# 001000-005.net
KiCad netlist of a schematic drawn in EAGLE
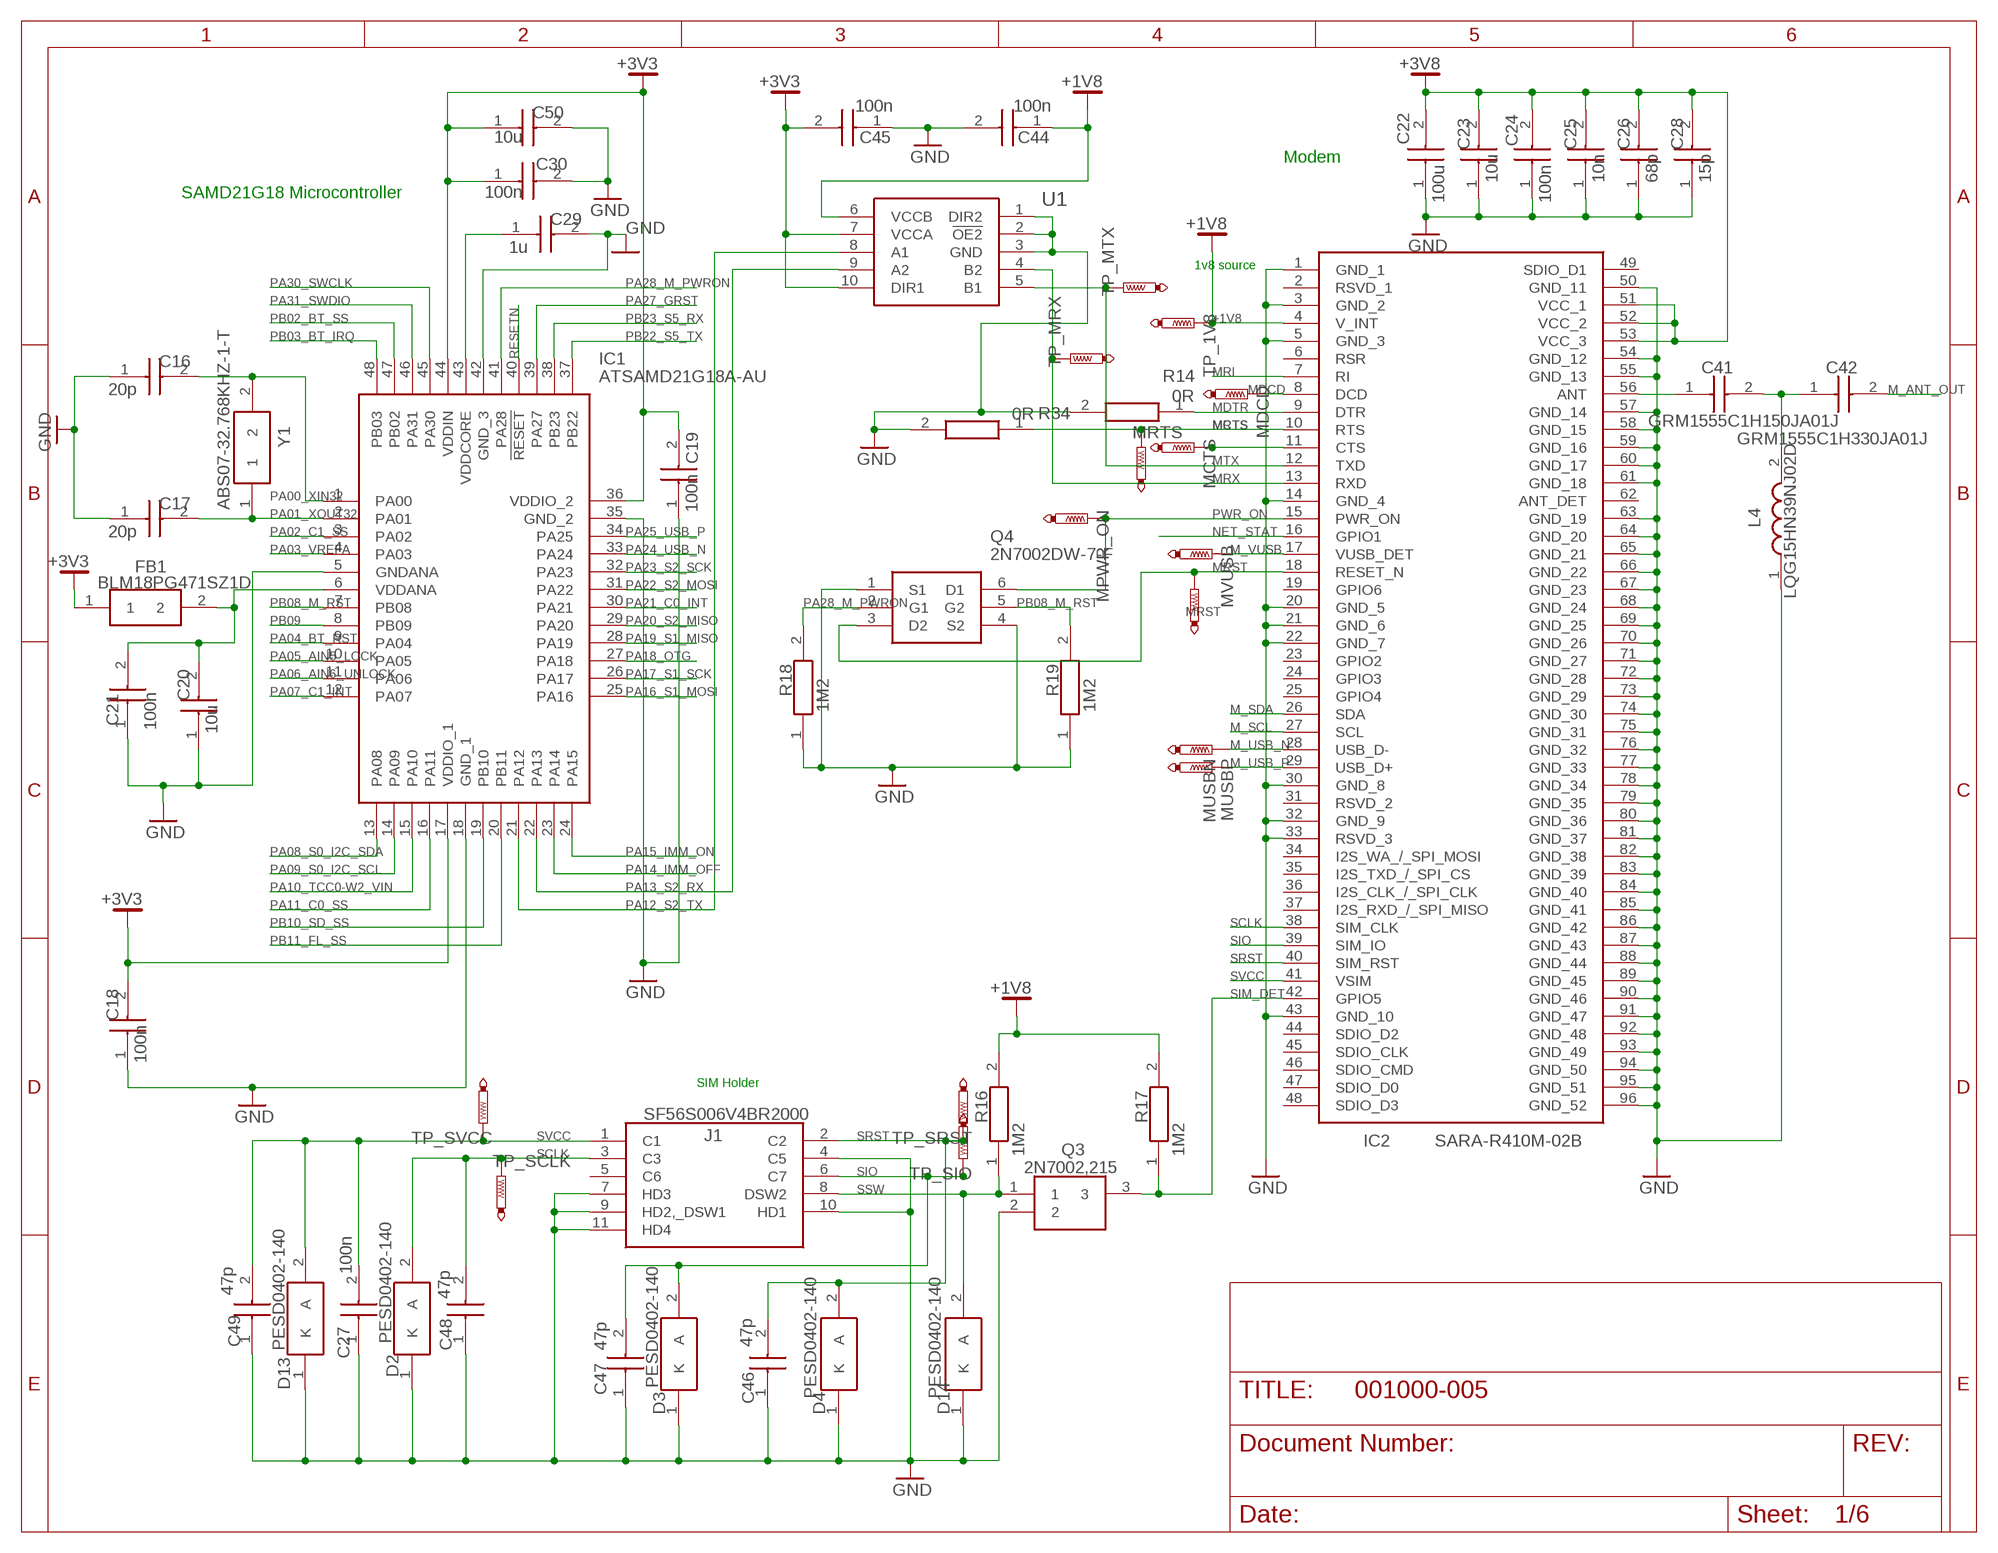
[diagram p0: schematic, sheet 1]
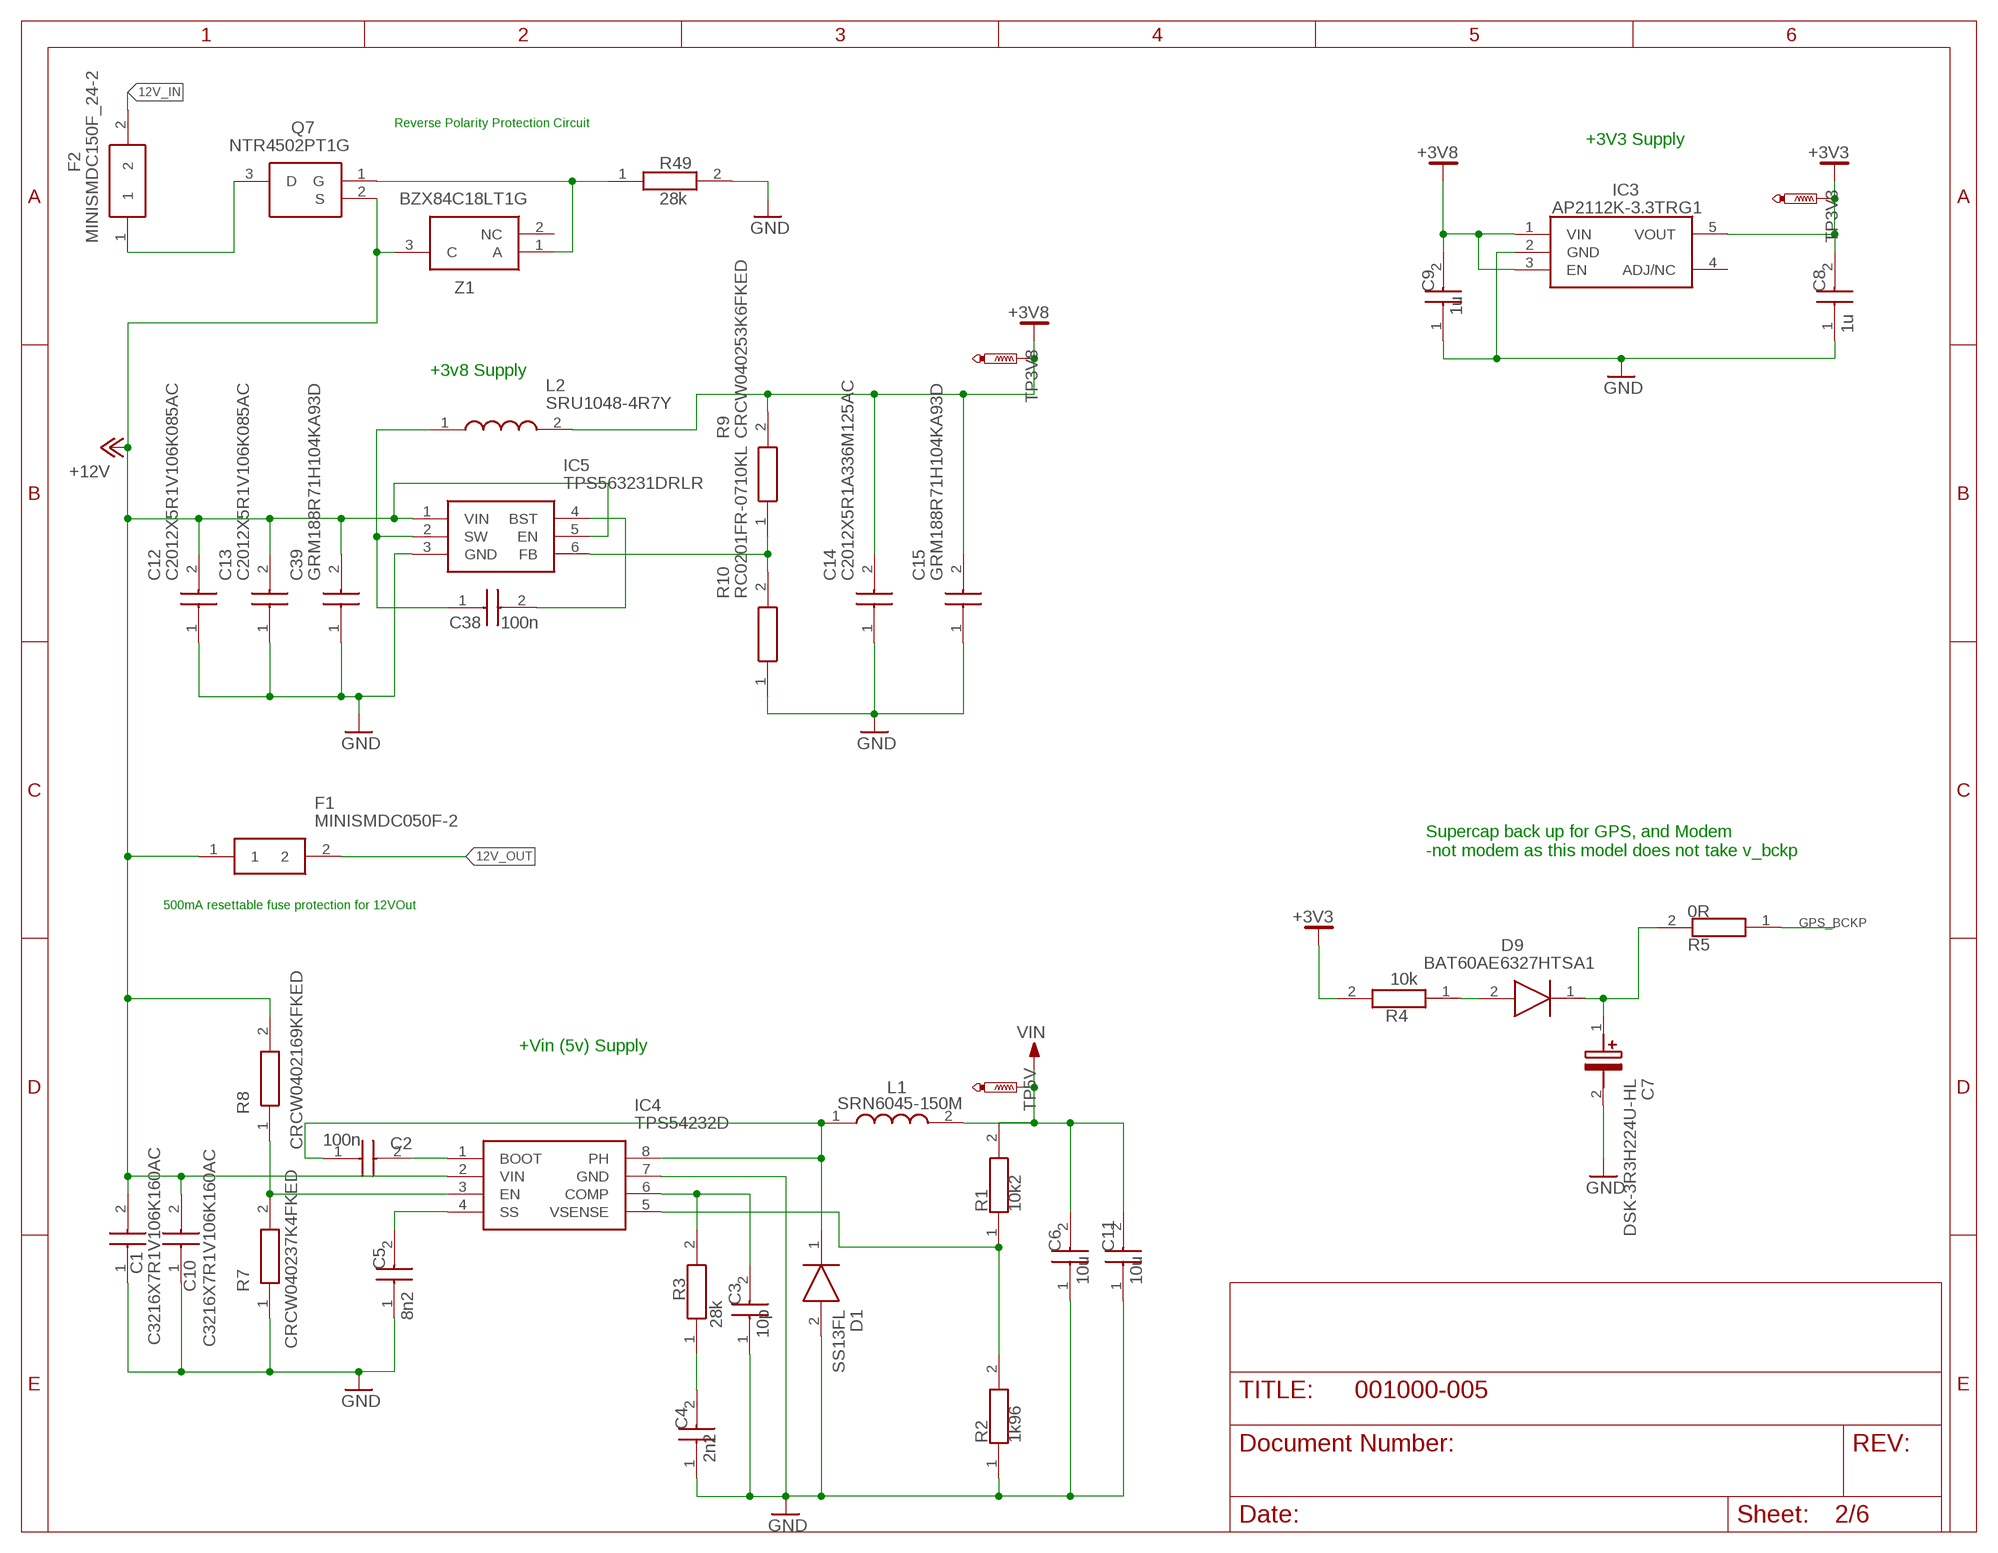
[diagram p1: schematic, sheet 2]
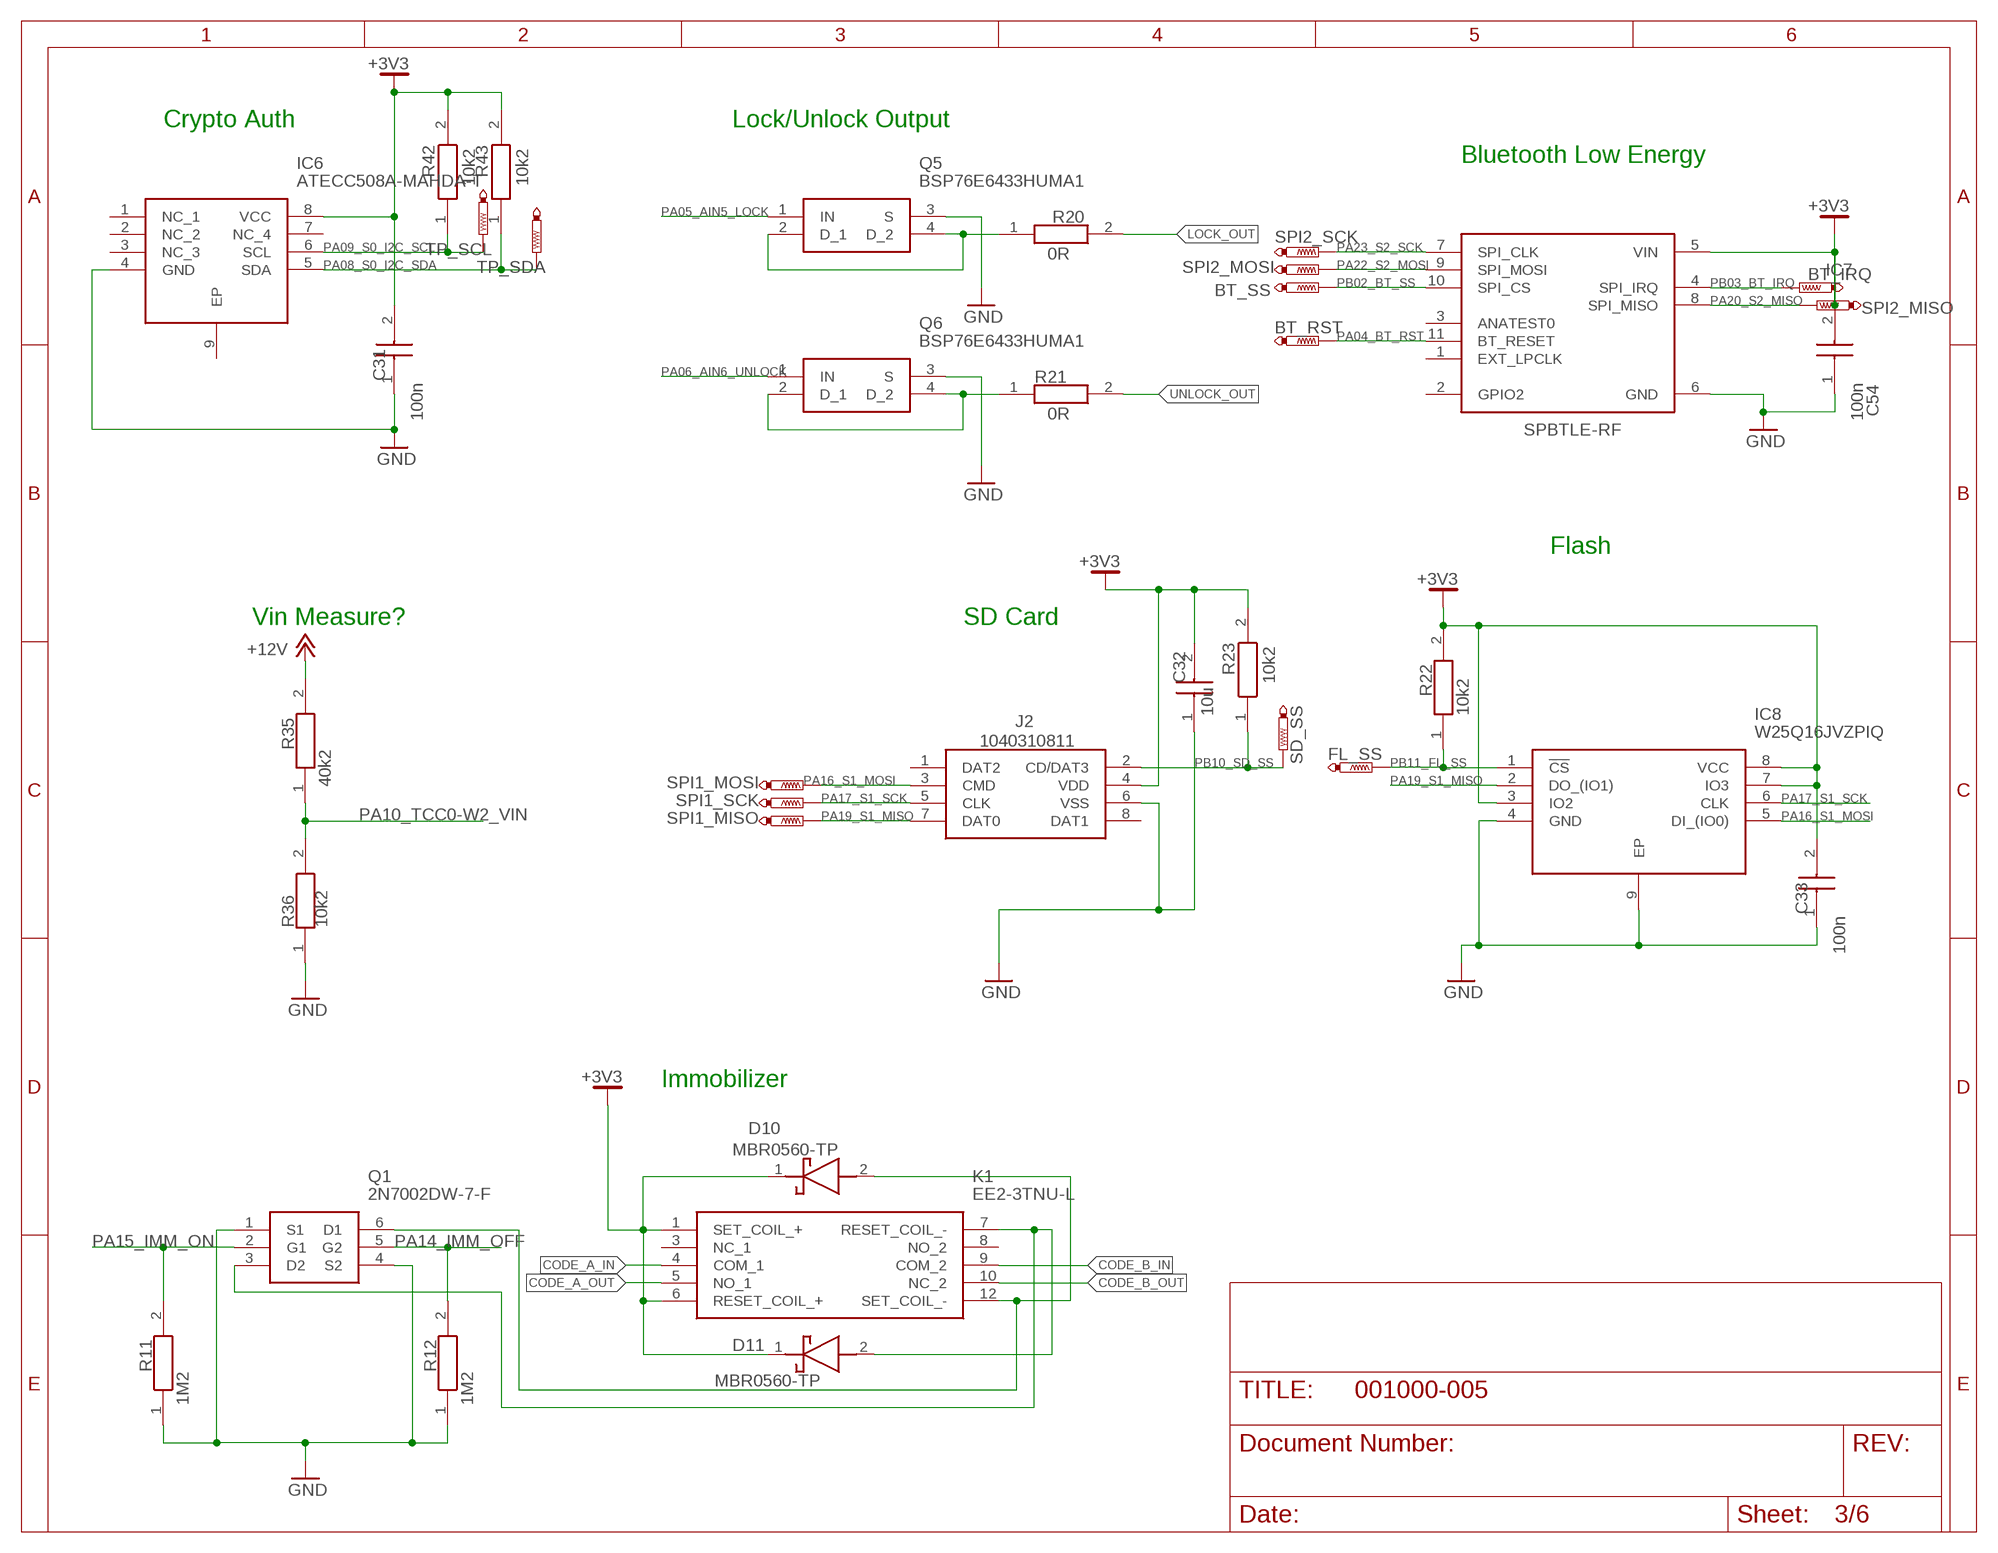
[diagram p2: schematic, sheet 3]
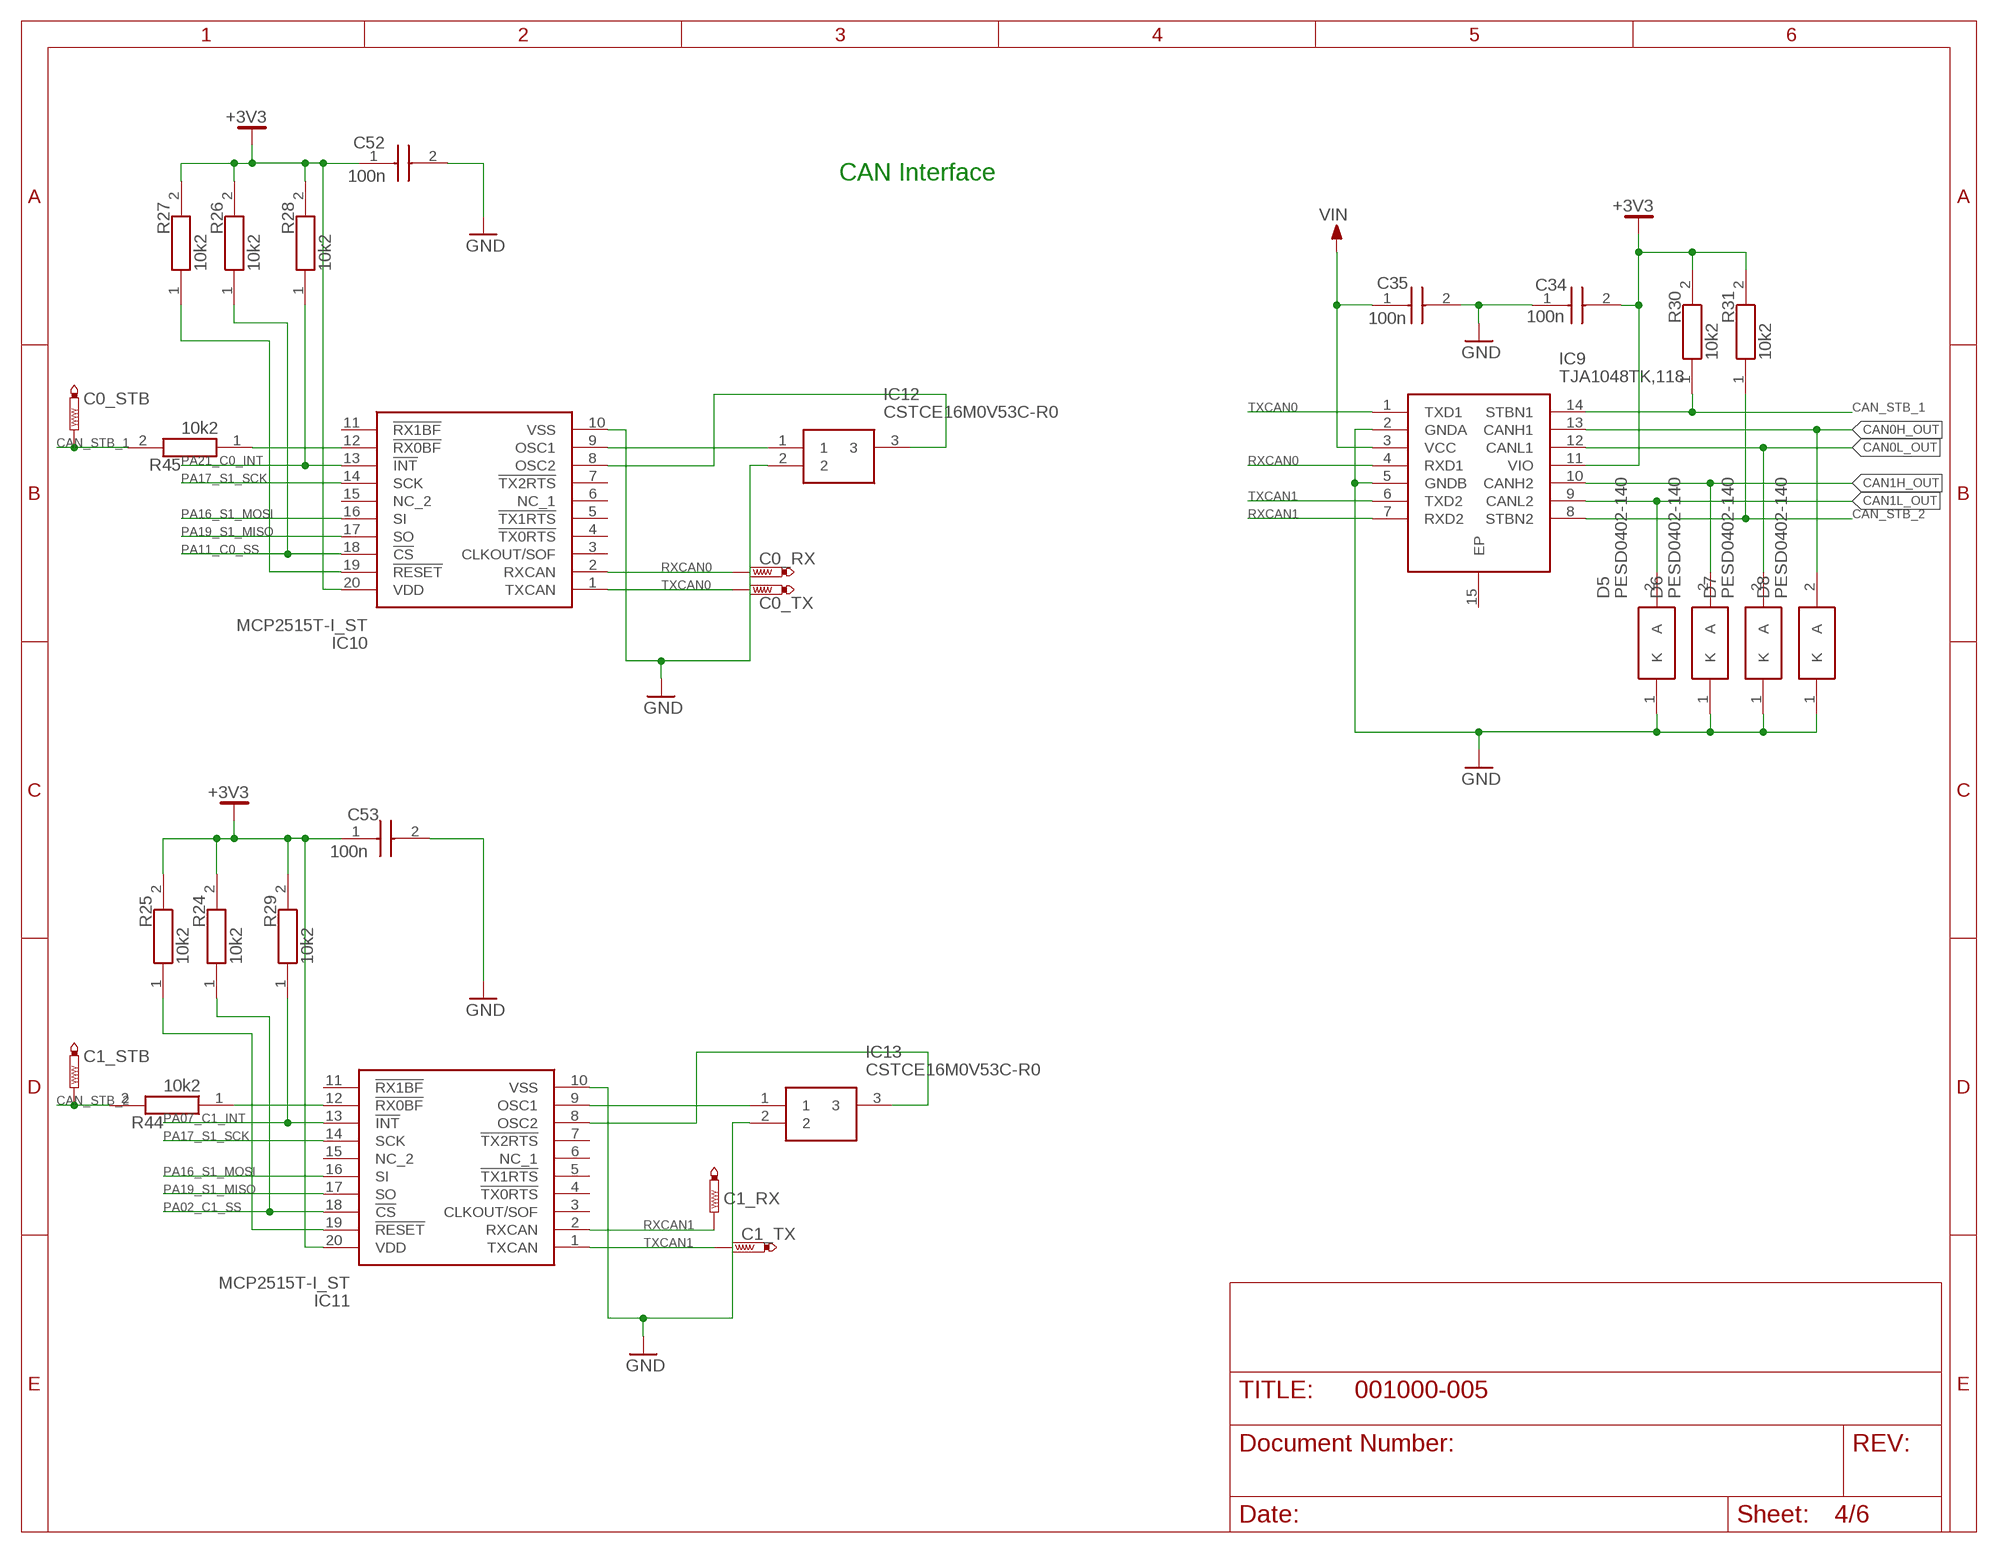
[diagram p3: schematic, sheet 4]
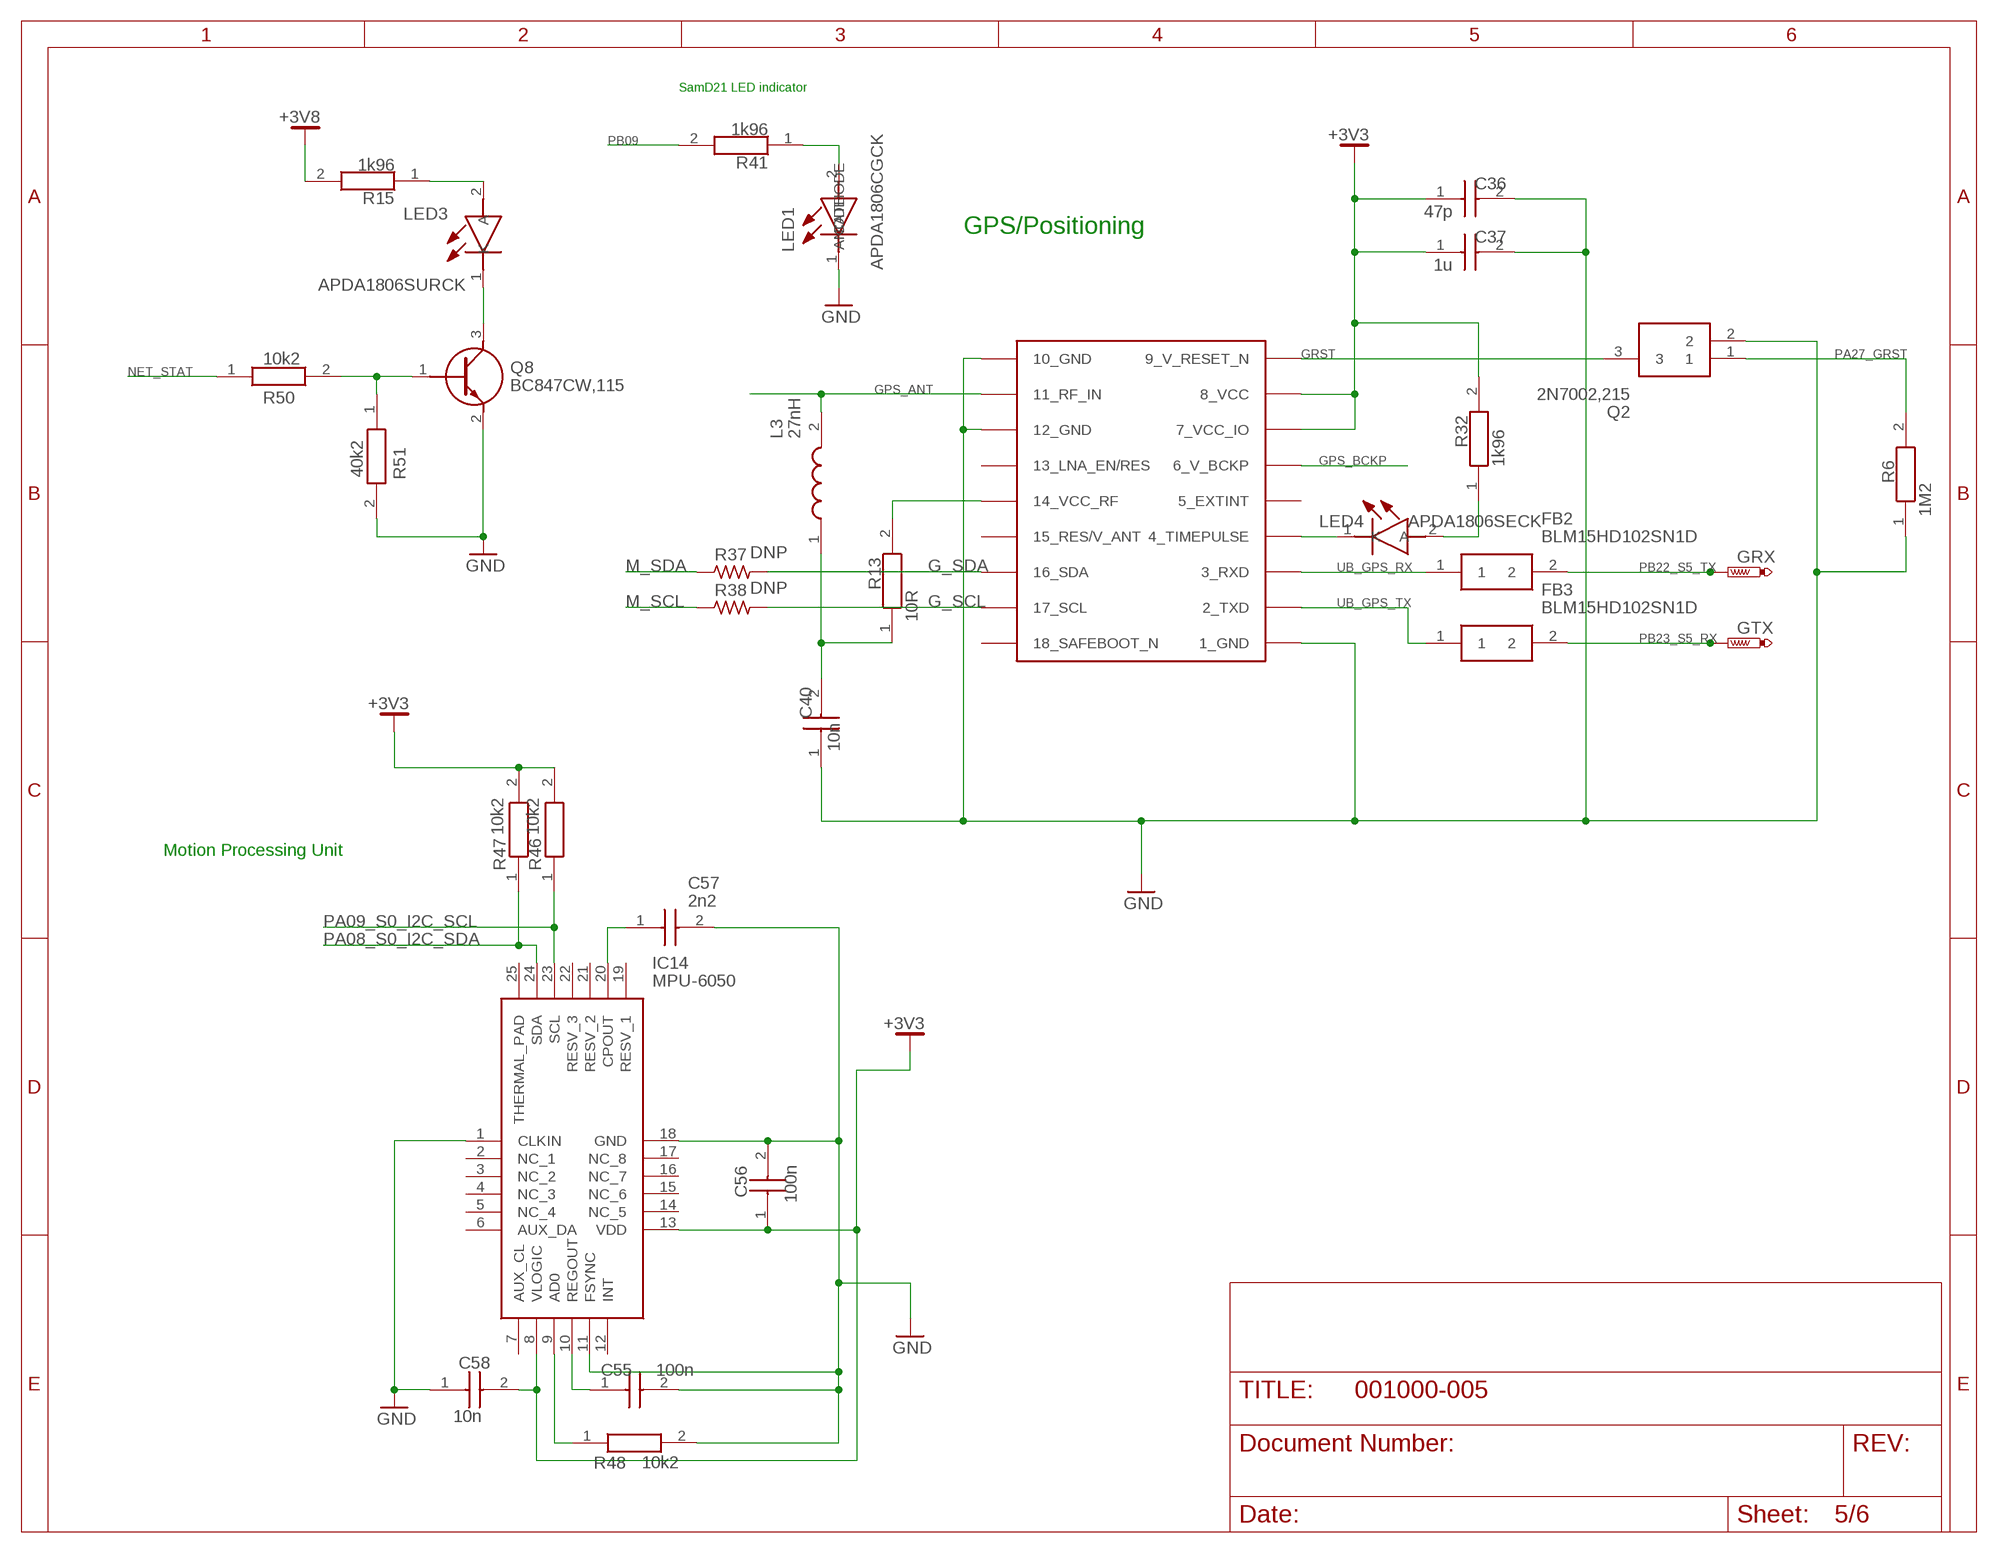
[diagram p4: schematic, sheet 5]
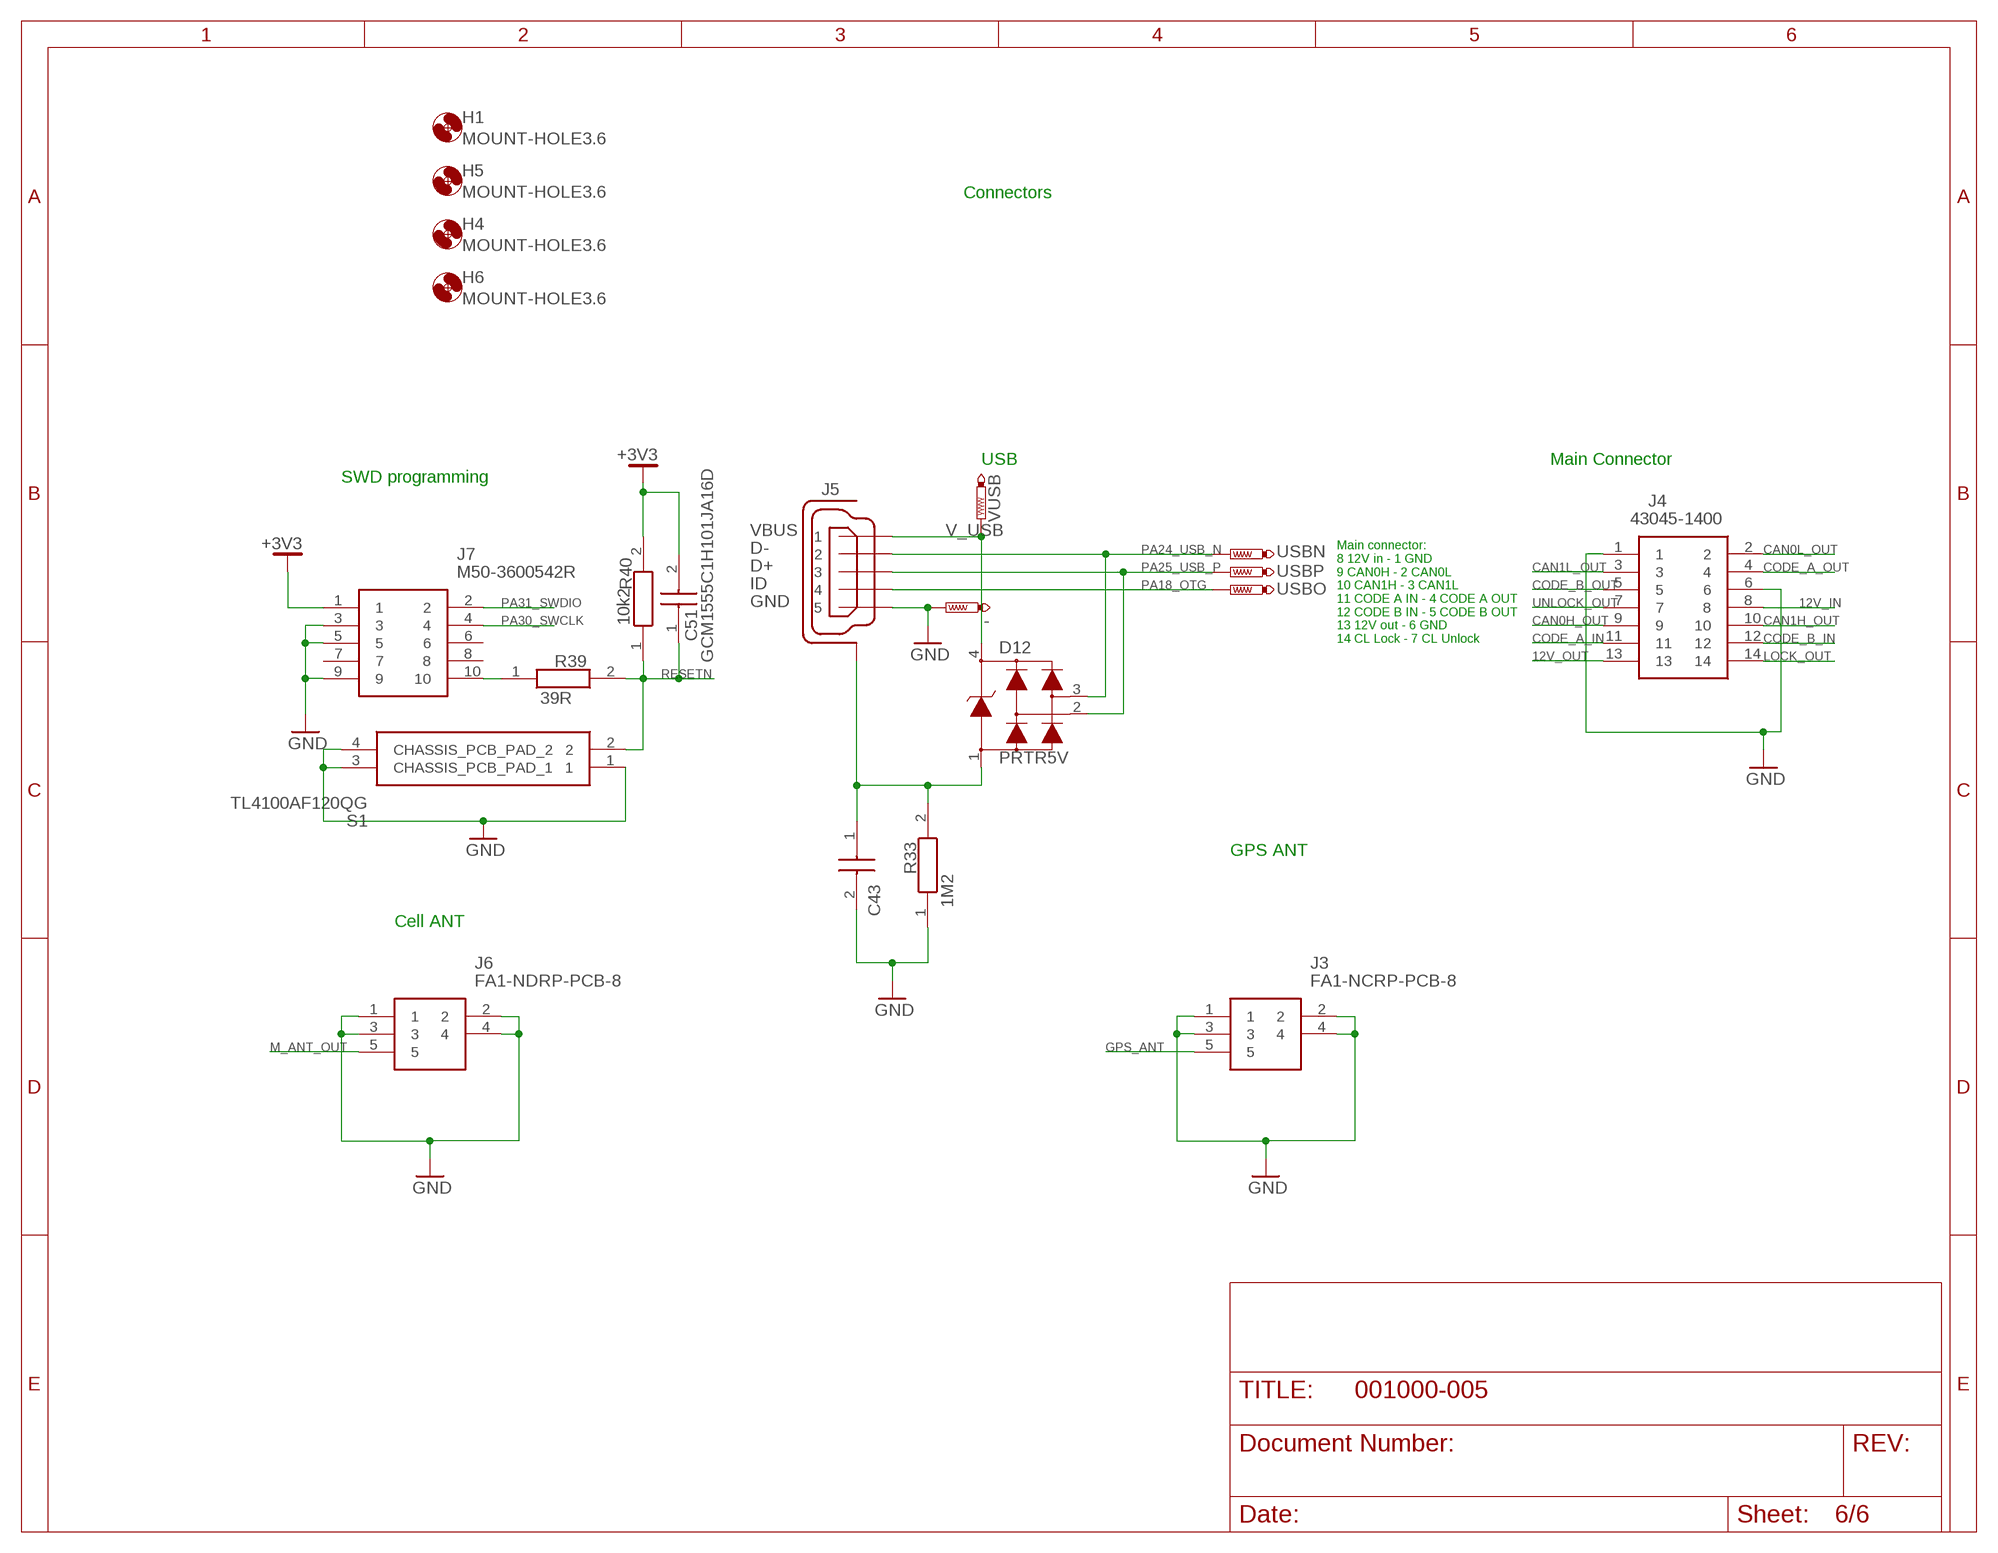
[diagram p5: schematic, sheet 6]

(export (version "E")
  (design (tool "Eeschema 10.0.6"))
  (components
    (comp (ref "-")
      (value "PTR1TP06R")
      (footprint "eagle-import:TP06R")
      (libsource (lib "eagle-import") (part "PTR1TP06R"))
    )
    (comp (ref "C43")
      (value "4n7")
      (footprint "eagle-import:CAPC1005X55N")
      (fields
        (field (name "MANUFACTURER_PART_NUMBER") "GRM155R71H472KA01J")
        (field (name "MOUSER_PART_NUMBER") "81-GRM155R71H472KA1J")
      )
      (libsource (lib "eagle-import") (part "GRM155R71H472KA01J"))
    )
    (comp (ref "C51")
      (value "GCM1555C1H101JA16D")
      (footprint "eagle-import:CAPC1005X55N")
      (libsource (lib "eagle-import") (part "GCM1555C1H101JA16D"))
    )
    (comp (ref "D12")
      (value "PRTR5V")
      (footprint "eagle-import:SOT190P230X110-4N")
      (fields (field (name "MANUFACTURER") "NXP"))
      (libsource (lib "eagle-import") (part "PRTR5V0U2X,215"))
    )
    (comp (ref "H1")
      (value "MOUNT-HOLE3.6")
      (footprint "eagle-import:3,6")
      (libsource (lib "eagle-import") (part "MOUNT-HOLE3.6"))
    )
    (comp (ref "H4")
      (value "MOUNT-HOLE3.6")
      (footprint "eagle-import:3,6")
      (libsource (lib "eagle-import") (part "MOUNT-HOLE3.6"))
    )
    (comp (ref "H5")
      (value "MOUNT-HOLE3.6")
      (footprint "eagle-import:3,6")
      (libsource (lib "eagle-import") (part "MOUNT-HOLE3.6"))
    )
    (comp (ref "H6")
      (value "MOUNT-HOLE3.6")
      (footprint "eagle-import:3,6")
      (libsource (lib "eagle-import") (part "MOUNT-HOLE3.6"))
    )
    (comp (ref "J3")
      (value "FA1-NCRP-PCB-8")
      (footprint "eagle-import:FA1NCRPPCB8")
      (fields (field (name "MOUSER_PART_NUMBER") "523-FA1-NCRP-PCB-8"))
      (libsource (lib "eagle-import") (part "FA1-NCRP-PCB-8"))
    )
    (comp (ref "J4")
      (value "43045-1400")
      (footprint "eagle-import:43045-1400")
      (fields (field (name "MOUSER_PART_NUMBER") "538-43045-1400"))
      (libsource (lib "eagle-import") (part "43045-1400"))
    )
    (comp (ref "J5")
      (value "-")
      (footprint "eagle-import:ZX62-AB-5PA")
      (fields (field (name "MANUFACTURER") "Hirose"))
      (libsource (lib "eagle-import") (part "USB-MICRO"))
    )
    (comp (ref "J6")
      (value "FA1-NDRP-PCB-8")
      (footprint "eagle-import:FA1NDRPPCB8")
      (fields (field (name "MOUSER_PART_NUMBER") "523-FA1-NDRP-PCB-8"))
      (libsource (lib "eagle-import") (part "FA1-NDRP-PCB-8"))
    )
    (comp (ref "J7")
      (value "M50-3600542R")
      (footprint "eagle-import:M503600542R")
      (fields (field (name "MOUSER_PART_NUMBER") "855-M50-3600542R"))
      (libsource (lib "eagle-import") (part "M50-3600542R"))
    )
    (comp (ref "R33")
      (value "1M2")
      (footprint "eagle-import:RESC1005X40N")
      (fields
        (field (name "MANUFACTURER_PART_NUMBER") "CRCW04021M20FKED")
        (field (name "MOUSER_PART_NUMBER") "71-CRCW04021M20FKED")
      )
      (libsource (lib "eagle-import") (part "CRCW04021M20FKED"))
    )
    (comp (ref "R39")
      (value "39R")
      (footprint "eagle-import:RESC1005X40N")
      (fields
        (field (name "MANUFACTURER_PART_NUMBER") "CRCW040239R0FKEDHP")
        (field (name "MOUSER_PART_NUMBER") "71-CRCW040239R0FKEDH")
      )
      (libsource (lib "eagle-import") (part "CRCW040239R0FKEDHP"))
    )
    (comp (ref "R40")
      (value "10k2")
      (footprint "eagle-import:RESC1005X40N")
      (fields
        (field (name "MANUFACTURER_PART_NUMBER") "CRCW040210K2FKED")
        (field (name "MOUSER_PART_NUMBER") "71-CRCW0402-10.2K-E3")
      )
      (libsource (lib "eagle-import") (part "CRCW040210K2FKED"))
    )
    (comp (ref "S1")
      (value "TL4100AF120QG")
      (footprint "eagle-import:TL4100AF120QG")
      (fields (field (name "MOUSER_PART_NUMBER") "612-TL4100AF120QG"))
      (libsource (lib "eagle-import") (part "TL4100AF120QG"))
    )
    (comp (ref "USBN")
      (value "PTR1TP06R")
      (footprint "eagle-import:TP06R")
      (libsource (lib "eagle-import") (part "PTR1TP06R"))
    )
    (comp (ref "USBO")
      (value "PTR1TP06R")
      (footprint "eagle-import:TP06R")
      (libsource (lib "eagle-import") (part "PTR1TP06R"))
    )
    (comp (ref "USBP")
      (value "PTR1TP06R")
      (footprint "eagle-import:TP06R")
      (libsource (lib "eagle-import") (part "PTR1TP06R"))
    )
    (comp (ref "VUSB")
      (value "PTR1TP06R")
      (footprint "eagle-import:TP06R")
      (libsource (lib "eagle-import") (part "PTR1TP06R"))
    )
    (comp (ref "C16")
      (value "20p")
      (footprint "eagle-import:CAPC1005X55N")
      (fields (field (name "MANUFACTURER_PART_NUMBER") "GJM1555C1H200GB01D"))
      (libsource (lib "eagle-import") (part "GJM1555C1H200GB01D"))
    )
    (comp (ref "C17")
      (value "20p")
      (footprint "eagle-import:CAPC1005X55N")
      (fields (field (name "MANUFACTURER_PART_NUMBER") "GJM1555C1H200GB01D"))
      (libsource (lib "eagle-import") (part "GJM1555C1H200GB01D"))
    )
    (comp (ref "C18")
      (value "100n")
      (footprint "eagle-import:CAPC1005X55N")
      (fields (field (name "MANUFACTURER_PART_NUMBER") "GCM155R71C104KA55J"))
      (libsource (lib "eagle-import") (part "GCM155R71C104KA55J"))
    )
    (comp (ref "C19")
      (value "100n")
      (footprint "eagle-import:CAPC1005X55N")
      (fields (field (name "MANUFACTURER_PART_NUMBER") "GCM155R71C104KA55J"))
      (libsource (lib "eagle-import") (part "GCM155R71C104KA55J"))
    )
    (comp (ref "C20")
      (value "10u")
      (footprint "eagle-import:CAPC1608X90N")
      (fields
        (field (name "MANUFACTURER_PART_NUMBER") "GRM188R60J106KE47D")
        (field (name "MOUSER_PART_NUMBER") "81-GRM188R60J106KE7D")
      )
      (libsource (lib "eagle-import") (part "GRM188R60J106KE47D"))
    )
    (comp (ref "C21")
      (value "100n")
      (footprint "eagle-import:CAPC1005X55N")
      (fields (field (name "MANUFACTURER_PART_NUMBER") "GCM155R71C104KA55J"))
      (libsource (lib "eagle-import") (part "GCM155R71C104KA55J"))
    )
    (comp (ref "C22")
      (value "100u")
      (footprint "eagle-import:CAPC3216X180N")
      (fields
        (field (name "MANUFACTURER_PART_NUMBER") "GRM31CD80J107ME39K")
        (field (name "MOUSER_PART_NUMBER") "81-GRM31CD80J107ME9K")
      )
      (libsource (lib "eagle-import") (part "GRM31CD80J107ME39K"))
    )
    (comp (ref "C23")
      (value "10u")
      (footprint "eagle-import:CAPC1608X90N")
      (fields
        (field (name "MANUFACTURER_PART_NUMBER") "GRM188R60J106KE47D")
        (field (name "MOUSER_PART_NUMBER") "81-GRM188R60J106KE7D")
      )
      (libsource (lib "eagle-import") (part "GRM188R60J106KE47D"))
    )
    (comp (ref "C24")
      (value "100n")
      (footprint "eagle-import:CAPC1005X55N")
      (fields (field (name "MANUFACTURER_PART_NUMBER") "GCM155R71C104KA55J"))
      (libsource (lib "eagle-import") (part "GCM155R71C104KA55J"))
    )
    (comp (ref "C25")
      (value "10n")
      (footprint "eagle-import:CAPC1005X55N")
      (fields
        (field (name "MANUFACTURER_PART_NUMBER") "GCM155R71H103KA55D")
        (field (name "MOUSER_PART_NUMBER") "81-GCM155R71H103KA5D")
      )
      (libsource (lib "eagle-import") (part "GCM155R71H103KA55D"))
    )
    (comp (ref "C26")
      (value "68p")
      (footprint "eagle-import:CAPC1005X55N")
      (fields (field (name "MANUFACTURER_PART_NUMBER") "GCM1555C1H680JA16D"))
      (libsource (lib "eagle-import") (part "GCM1555C1H680JA16D"))
    )
    (comp (ref "C27")
      (value "100n")
      (footprint "eagle-import:CAPC1005X55N")
      (fields (field (name "MANUFACTURER_PART_NUMBER") "GCM155R71C104KA55J"))
      (libsource (lib "eagle-import") (part "GCM155R71C104KA55J"))
    )
    (comp (ref "C28")
      (value "15p")
      (footprint "eagle-import:CAPC1005X55N")
      (fields (field (name "MANUFACTURER_PART_NUMBER") "GCM1555C1H150JA16D"))
      (libsource (lib "eagle-import") (part "GCM1555C1H150JA16D"))
    )
    (comp (ref "C29")
      (value "1u")
      (footprint "eagle-import:CAPC1005X55N")
      (fields
        (field (name "MANUFACTURER_PART_NUMBER") "GRM155R61C105MA12D")
        (field (name "MOUSER_PART_NUMBER") "81-GRM155R61C105MA2D")
      )
      (libsource (lib "eagle-import") (part "GRM155R61C105MA12D"))
    )
    (comp (ref "C30")
      (value "100n")
      (footprint "eagle-import:CAPC1005X55N")
      (fields (field (name "MANUFACTURER_PART_NUMBER") "GCM155R71C104KA55J"))
      (libsource (lib "eagle-import") (part "GCM155R71C104KA55J"))
    )
    (comp (ref "C41")
      (value "GRM1555C1H150JA01J")
      (footprint "eagle-import:CAPC1005X55N")
      (fields (field (name "MOUSER_PART_NUMBER") "81-GRM1555C1H150JA1J"))
      (libsource (lib "eagle-import") (part "GRM1555C1H150JA01J"))
    )
    (comp (ref "C42")
      (value "GRM1555C1H330JA01J")
      (footprint "eagle-import:CAPC1005X55N")
      (fields (field (name "MOUSER_PART_NUMBER") "81-GRM1555C1H330JA1J"))
      (libsource (lib "eagle-import") (part "GRM1555C1H330JA01J"))
    )
    (comp (ref "C44")
      (value "100n")
      (footprint "eagle-import:CAPC1005X55N")
      (fields (field (name "MANUFACTURER_PART_NUMBER") "GCM155R71C104KA55J"))
      (libsource (lib "eagle-import") (part "GCM155R71C104KA55J"))
    )
    (comp (ref "C45")
      (value "100n")
      (footprint "eagle-import:CAPC1005X55N")
      (fields (field (name "MANUFACTURER_PART_NUMBER") "GCM155R71C104KA55J"))
      (libsource (lib "eagle-import") (part "GCM155R71C104KA55J"))
    )
    (comp (ref "C46")
      (value "47p")
      (footprint "eagle-import:CAPC1005X55N")
      (fields
        (field (name "MANUFACTURER_PART_NUMBER") "GRM1555C1H470JA01D")
        (field (name "MOUSER_PART_NUMBER") "81-GRM1555C1H470JA1D")
      )
      (libsource (lib "eagle-import") (part "GRM1555C1H470JA01D"))
    )
    (comp (ref "C47")
      (value "47p")
      (footprint "eagle-import:CAPC1005X55N")
      (fields
        (field (name "MANUFACTURER_PART_NUMBER") "GRM1555C1H470JA01D")
        (field (name "MOUSER_PART_NUMBER") "81-GRM1555C1H470JA1D")
      )
      (libsource (lib "eagle-import") (part "GRM1555C1H470JA01D"))
    )
    (comp (ref "C48")
      (value "47p")
      (footprint "eagle-import:CAPC1005X55N")
      (fields
        (field (name "MANUFACTURER_PART_NUMBER") "GRM1555C1H470JA01D")
        (field (name "MOUSER_PART_NUMBER") "81-GRM1555C1H470JA1D")
      )
      (libsource (lib "eagle-import") (part "GRM1555C1H470JA01D"))
    )
    (comp (ref "C49")
      (value "47p")
      (footprint "eagle-import:CAPC1005X55N")
      (fields
        (field (name "MANUFACTURER_PART_NUMBER") "GRM1555C1H470JA01D")
        (field (name "MOUSER_PART_NUMBER") "81-GRM1555C1H470JA1D")
      )
      (libsource (lib "eagle-import") (part "GRM1555C1H470JA01D"))
    )
    (comp (ref "C50")
      (value "10u")
      (footprint "eagle-import:CAPC1608X90N")
      (fields
        (field (name "MANUFACTURER_PART_NUMBER") "GRM188R60J106KE47D")
        (field (name "MOUSER_PART_NUMBER") "81-GRM188R60J106KE7D")
      )
      (libsource (lib "eagle-import") (part "GRM188R60J106KE47D"))
    )
    (comp (ref "D2")
      (value "PESD0402-140")
      (footprint "eagle-import:DIONC1005X43N")
      (libsource (lib "eagle-import") (part "PESD0402-140"))
    )
    (comp (ref "D3")
      (value "PESD0402-140")
      (footprint "eagle-import:DIONC1005X43N")
      (libsource (lib "eagle-import") (part "PESD0402-140"))
    )
    (comp (ref "D4")
      (value "PESD0402-140")
      (footprint "eagle-import:DIONC1005X43N")
      (libsource (lib "eagle-import") (part "PESD0402-140"))
    )
    (comp (ref "D13")
      (value "PESD0402-140")
      (footprint "eagle-import:DIONC1005X43N")
      (libsource (lib "eagle-import") (part "PESD0402-140"))
    )
    (comp (ref "D14")
      (value "PESD0402-140")
      (footprint "eagle-import:DIONC1005X43N")
      (libsource (lib "eagle-import") (part "PESD0402-140"))
    )
    (comp (ref "FB1")
      (value "BLM18PG471SZ1D")
      (footprint "eagle-import:BEADC1608X95N")
      (fields (field (name "MOUSER_PART_NUMBER") "81-BLM18PG471SZ1D"))
      (libsource (lib "eagle-import") (part "BLM18PG471SZ1D"))
    )
    (comp (ref "IC1")
      (value "ATSAMD21G18A-AU")
      (footprint "eagle-import:QFP50P900X900X120-48N")
      (fields (field (name "MOUSER_PART_NUMBER") "556-ATSAMD21G18A-AU"))
      (libsource (lib "eagle-import") (part "ATSAMD21G18A-AU"))
    )
    (comp (ref "IC2")
      (value "SARA-R410M-02B")
      (footprint "eagle-import:SARA-U201-03B")
      (libsource (lib "eagle-import") (part "SARA-R410M-02B"))
    )
    (comp (ref "J1")
      (value "SF56S006V4BR2000")
      (footprint "eagle-import:SF56S006V4BR2000")
      (fields (field (name "MOUSER_PART_NUMBER") "656-SF56S006V4BR2000"))
      (libsource (lib "eagle-import") (part "SF56S006V4BR2000"))
    )
    (comp (ref "L4")
      (value "LQG15HN39NJ02D")
      (footprint "eagle-import:INDC1005X55N")
      (libsource (lib "eagle-import") (part "LQG15HN39NJ02D"))
    )
    (comp (ref "MCTS")
      (value "PTR1TP06R")
      (footprint "eagle-import:TP06R")
      (libsource (lib "eagle-import") (part "PTR1TP06R"))
    )
    (comp (ref "MDCD")
      (value "PTR1TP06R")
      (footprint "eagle-import:TP06R")
      (libsource (lib "eagle-import") (part "PTR1TP06R"))
    )
    (comp (ref "MPWR_ON")
      (value "PTR1TP06R")
      (footprint "eagle-import:TP06R")
      (libsource (lib "eagle-import") (part "PTR1TP06R"))
    )
    (comp (ref "MRST")
      (value "PTR1TP06R")
      (footprint "eagle-import:TP06R")
      (libsource (lib "eagle-import") (part "PTR1TP06R"))
    )
    (comp (ref "MRTS")
      (value "PTR1TP06R")
      (footprint "eagle-import:TP06R")
      (libsource (lib "eagle-import") (part "PTR1TP06R"))
    )
    (comp (ref "MUSBN")
      (value "PTR1TP06R")
      (footprint "eagle-import:TP06R")
      (libsource (lib "eagle-import") (part "PTR1TP06R"))
    )
    (comp (ref "MUSBP")
      (value "PTR1TP06R")
      (footprint "eagle-import:TP06R")
      (libsource (lib "eagle-import") (part "PTR1TP06R"))
    )
    (comp (ref "MVUSB")
      (value "PTR1TP06R")
      (footprint "eagle-import:TP06R")
      (libsource (lib "eagle-import") (part "PTR1TP06R"))
    )
    (comp (ref "Q3")
      (value "2N7002,215")
      (footprint "eagle-import:SOT95P230X110-3N")
      (fields (field (name "MOUSER_PART_NUMBER") "771-2N7002-T/R"))
      (libsource (lib "eagle-import") (part "2N7002,215"))
    )
    (comp (ref "Q4")
      (value "2N7002DW-7-F")
      (footprint "eagle-import:SOT65P210X100-6N")
      (fields (field (name "MOUSER_PART_NUMBER") "621-2N7002DW-F"))
      (libsource (lib "eagle-import") (part "2N7002DW-7-F"))
    )
    (comp (ref "R14")
      (value "0R")
      (footprint "eagle-import:RESC1005X40N")
      (fields (field (name "MANUFACTURER_PART_NUMBER") "RMCF0402ZT0R00"))
      (libsource (lib "eagle-import") (part "RMCF0402ZT0R00"))
    )
    (comp (ref "R16")
      (value "1M2")
      (footprint "eagle-import:RESC1005X40N")
      (fields
        (field (name "MANUFACTURER_PART_NUMBER") "CRCW04021M20FKED")
        (field (name "MOUSER_PART_NUMBER") "71-CRCW04021M20FKED")
      )
      (libsource (lib "eagle-import") (part "CRCW04021M20FKED"))
    )
    (comp (ref "R17")
      (value "1M2")
      (footprint "eagle-import:RESC1005X40N")
      (fields
        (field (name "MANUFACTURER_PART_NUMBER") "CRCW04021M20FKED")
        (field (name "MOUSER_PART_NUMBER") "71-CRCW04021M20FKED")
      )
      (libsource (lib "eagle-import") (part "CRCW04021M20FKED"))
    )
    (comp (ref "R18")
      (value "1M2")
      (footprint "eagle-import:RESC1005X40N")
      (fields
        (field (name "MANUFACTURER_PART_NUMBER") "CRCW04021M20FKED")
        (field (name "MOUSER_PART_NUMBER") "71-CRCW04021M20FKED")
      )
      (libsource (lib "eagle-import") (part "CRCW04021M20FKED"))
    )
    (comp (ref "R19")
      (value "1M2")
      (footprint "eagle-import:RESC1005X40N")
      (fields
        (field (name "MANUFACTURER_PART_NUMBER") "CRCW04021M20FKED")
        (field (name "MOUSER_PART_NUMBER") "71-CRCW04021M20FKED")
      )
      (libsource (lib "eagle-import") (part "CRCW04021M20FKED"))
    )
    (comp (ref "R34")
      (value "0R")
      (footprint "eagle-import:RESC1005X40N")
      (fields (field (name "MANUFACTURER_PART_NUMBER") "RMCF0402ZT0R00"))
      (libsource (lib "eagle-import") (part "RMCF0402ZT0R00"))
    )
    (comp (ref "TP_1V8")
      (value "PTR1TP06R")
      (footprint "eagle-import:TP06R")
      (libsource (lib "eagle-import") (part "PTR1TP06R"))
    )
    (comp (ref "TP_MRX")
      (value "PTR1TP06R")
      (footprint "eagle-import:TP06R")
      (libsource (lib "eagle-import") (part "PTR1TP06R"))
    )
    (comp (ref "TP_MTX")
      (value "PTR1TP06R")
      (footprint "eagle-import:TP06R")
      (libsource (lib "eagle-import") (part "PTR1TP06R"))
    )
    (comp (ref "TP_SCLK")
      (value "PTR1TP06R")
      (footprint "eagle-import:TP06R")
      (libsource (lib "eagle-import") (part "PTR1TP06R"))
    )
    (comp (ref "TP_SIO")
      (value "PTR1TP06R")
      (footprint "eagle-import:TP06R")
      (libsource (lib "eagle-import") (part "PTR1TP06R"))
    )
    (comp (ref "TP_SRST")
      (value "PTR1TP06R")
      (footprint "eagle-import:TP06R")
      (libsource (lib "eagle-import") (part "PTR1TP06R"))
    )
    (comp (ref "TP_SVCC")
      (value "PTR1TP06R")
      (footprint "eagle-import:TP06R")
      (libsource (lib "eagle-import") (part "PTR1TP06R"))
    )
    (comp (ref "U1")
      (value "SN74AVC2T245RSWR")
      (footprint "eagle-import:RSW(RPUQFNN10)")
      (fields (field (name "MOUSER_PART_NUMBER") "595-SN74AVC2T245RSWR"))
      (libsource (lib "eagle-import") (part "SN74AVC2T245RSWR"))
    )
    (comp (ref "Y1")
      (value "ABS07-32.768KHZ-1-T")
      (footprint "eagle-import:ABS0716632768KHZT")
      (fields
        (field (name "MANUFACTURER_PART_NUMBER") "ABS07-32.768KHz-1-T")
        (field (name "MOUSER_PART_NUMBER") "815-ABS07-32.7K-1-T")
      )
      (libsource (lib "eagle-import") (part "ABS07-32.768KHZ-1-T"))
    )
    (comp (ref "C36")
      (value "47p")
      (footprint "eagle-import:CAPC1005X55N")
      (fields
        (field (name "MANUFACTURER_PART_NUMBER") "GRM1555C1H470JA01D")
        (field (name "MOUSER_PART_NUMBER") "81-GRM1555C1H470JA1D")
      )
      (libsource (lib "eagle-import") (part "GRM1555C1H470JA01D"))
    )
    (comp (ref "C37")
      (value "1u")
      (footprint "eagle-import:CAPC1608X90N")
      (fields
        (field (name "MANUFACTURER_PART_NUMBER") "GRT188C8YA105KE13D")
        (field (name "MOUSER_PART_NUMBER") "81-GRT188C8YA105KE3D")
      )
      (libsource (lib "eagle-import") (part "GRT188C8YA105KE13D"))
    )
    (comp (ref "C40")
      (value "10n")
      (footprint "eagle-import:CAPC1005X55N")
      (fields
        (field (name "MANUFACTURER_PART_NUMBER") "GCM155R71H103KA55D")
        (field (name "MOUSER_PART_NUMBER") "81-GCM155R71H103KA5D")
      )
      (libsource (lib "eagle-import") (part "GCM155R71H103KA55D"))
    )
    (comp (ref "C55")
      (value "100n")
      (footprint "eagle-import:CAPC1005X55N")
      (fields (field (name "MANUFACTURER_PART_NUMBER") "GCM155R71C104KA55J"))
      (libsource (lib "eagle-import") (part "GCM155R71C104KA55J"))
    )
    (comp (ref "C56")
      (value "100n")
      (footprint "eagle-import:CAPC1005X55N")
      (fields (field (name "MANUFACTURER_PART_NUMBER") "GCM155R71C104KA55J"))
      (libsource (lib "eagle-import") (part "GCM155R71C104KA55J"))
    )
    (comp (ref "C57")
      (value "2n2")
      (footprint "eagle-import:CAPC1005X55N")
      (fields
        (field (name "MANUFACTURER_PART_NUMBER") "GRM155R71H222KA01D")
        (field (name "MOUSER_PART_NUMBER") "81-GRM36X222K50")
      )
      (libsource (lib "eagle-import") (part "GRM155R71H222KA01D"))
    )
    (comp (ref "C58")
      (value "10n")
      (footprint "eagle-import:CAPC1005X55N")
      (fields
        (field (name "MANUFACTURER_PART_NUMBER") "GCM155R71H103KA55D")
        (field (name "MOUSER_PART_NUMBER") "81-GCM155R71H103KA5D")
      )
      (libsource (lib "eagle-import") (part "GCM155R71H103KA55D"))
    )
    (comp (ref "FB2")
      (value "BLM15HD102SN1D")
      (footprint "eagle-import:BEADC1005X55N")
      (fields (field (name "MOUSER_PART_NUMBER") "81-BLM15HD102SN1D"))
      (libsource (lib "eagle-import") (part "BLM15HD102SN1D"))
    )
    (comp (ref "FB3")
      (value "BLM15HD102SN1D")
      (footprint "eagle-import:BEADC1005X55N")
      (fields (field (name "MOUSER_PART_NUMBER") "81-BLM15HD102SN1D"))
      (libsource (lib "eagle-import") (part "BLM15HD102SN1D"))
    )
    (comp (ref "GRX")
      (value "PTR1TP06R")
      (footprint "eagle-import:TP06R")
      (libsource (lib "eagle-import") (part "PTR1TP06R"))
    )
    (comp (ref "GTX")
      (value "PTR1TP06R")
      (footprint "eagle-import:TP06R")
      (libsource (lib "eagle-import") (part "PTR1TP06R"))
    )
    (comp (ref "IC14")
      (value "MPU-6050")
      (footprint "eagle-import:QFN50P400X400X95-25N")
      (libsource (lib "eagle-import") (part "MPU-6050"))
    )
    (comp (ref "L3")
      (value "27nH")
      (footprint "eagle-import:INDC1608X95N")
      (fields (field (name "MANUFACTURER_PART_NUMBER") "L-14C27NJV4T"))
      (libsource (lib "eagle-import") (part "L-14C27NJV4T"))
    )
    (comp (ref "LED1")
      (value "APDA1806CGCK")
      (footprint "eagle-import:APDA1806CGCK")
      (fields (field (name "MOUSER_PART_NUMBER") "604-APDA1806CGCK"))
      (libsource (lib "eagle-import") (part "APDA1806CGCK"))
    )
    (comp (ref "LED3")
      (value "APDA1806SURCK")
      (footprint "eagle-import:APDA1806SURCK")
      (fields (field (name "MOUSER_PART_NUMBER") "604-APDA1806SURCK"))
      (libsource (lib "eagle-import") (part "APDA1806SURCK"))
    )
    (comp (ref "LED4")
      (value "APDA1806SECK")
      (footprint "eagle-import:APDA1806SECK")
      (fields (field (name "MOUSER_PART_NUMBER") "604-APDA1806SECK"))
      (libsource (lib "eagle-import") (part "APDA1806SECK"))
    )
    (comp (ref "Q2")
      (value "2N7002,215")
      (footprint "eagle-import:SOT95P230X110-3N")
      (fields (field (name "MOUSER_PART_NUMBER") "771-2N7002-T/R"))
      (libsource (lib "eagle-import") (part "2N7002,215"))
    )
    (comp (ref "Q8")
      (value "BC847CW,115")
      (footprint "eagle-import:SOT65P210X110-3N")
      (fields (field (name "MOUSER_PART_NUMBER") "771-BC847CW-T/R"))
      (libsource (lib "eagle-import") (part "BC847CW,115"))
    )
    (comp (ref "R6")
      (value "1M2")
      (footprint "eagle-import:RESC1005X40N")
      (fields
        (field (name "MANUFACTURER_PART_NUMBER") "CRCW04021M20FKED")
        (field (name "MOUSER_PART_NUMBER") "71-CRCW04021M20FKED")
      )
      (libsource (lib "eagle-import") (part "CRCW04021M20FKED"))
    )
    (comp (ref "R13")
      (value "10R")
      (footprint "eagle-import:RESC1005X35N")
      (fields (field (name "MANUFACTURER_PART_NUMBER") "CRGCQ0402F10R"))
      (libsource (lib "eagle-import") (part "CRGCQ0402F10R"))
    )
    (comp (ref "R15")
      (value "1k96")
      (footprint "eagle-import:RESC1005X40N")
      (fields
        (field (name "MANUFACTURER_PART_NUMBER") "CRCW04021K96FKED")
        (field (name "MOUSER_PART_NUMBER") "71-CRCW0402-1.96K-E3")
      )
      (libsource (lib "eagle-import") (part "CRCW04021K96FKED"))
    )
    (comp (ref "R32")
      (value "1k96")
      (footprint "eagle-import:RESC1005X40N")
      (fields
        (field (name "MANUFACTURER_PART_NUMBER") "CRCW04021K96FKED")
        (field (name "MOUSER_PART_NUMBER") "71-CRCW0402-1.96K-E3")
      )
      (libsource (lib "eagle-import") (part "CRCW04021K96FKED"))
    )
    (comp (ref "R37")
      (value "DNP")
      (footprint "eagle-import:R0402")
      (libsource (lib "eagle-import") (part "R_0402"))
    )
    (comp (ref "R38")
      (value "DNP")
      (footprint "eagle-import:R0402")
      (libsource (lib "eagle-import") (part "R_0402"))
    )
    (comp (ref "R41")
      (value "1k96")
      (footprint "eagle-import:RESC1005X40N")
      (fields
        (field (name "MANUFACTURER_PART_NUMBER") "CRCW04021K96FKED")
        (field (name "MOUSER_PART_NUMBER") "71-CRCW0402-1.96K-E3")
      )
      (libsource (lib "eagle-import") (part "CRCW04021K96FKED"))
    )
    (comp (ref "R46")
      (value "10k2")
      (footprint "eagle-import:RESC1005X40N")
      (fields
        (field (name "MANUFACTURER_PART_NUMBER") "CRCW040210K2FKED")
        (field (name "MOUSER_PART_NUMBER") "71-CRCW0402-10.2K-E3")
      )
      (libsource (lib "eagle-import") (part "CRCW040210K2FKED"))
    )
    (comp (ref "R47")
      (value "10k2")
      (footprint "eagle-import:RESC1005X40N")
      (fields
        (field (name "MANUFACTURER_PART_NUMBER") "CRCW040210K2FKED")
        (field (name "MOUSER_PART_NUMBER") "71-CRCW0402-10.2K-E3")
      )
      (libsource (lib "eagle-import") (part "CRCW040210K2FKED"))
    )
    (comp (ref "R48")
      (value "10k2")
      (footprint "eagle-import:RESC1005X40N")
      (fields
        (field (name "MANUFACTURER_PART_NUMBER") "CRCW040210K2FKED")
        (field (name "MOUSER_PART_NUMBER") "71-CRCW0402-10.2K-E3")
      )
      (libsource (lib "eagle-import") (part "CRCW040210K2FKED"))
    )
    (comp (ref "R50")
      (value "10k2")
      (footprint "eagle-import:RESC1005X40N")
      (fields
        (field (name "MANUFACTURER_PART_NUMBER") "CRCW040210K2FKED")
        (field (name "MOUSER_PART_NUMBER") "71-CRCW0402-10.2K-E3")
      )
      (libsource (lib "eagle-import") (part "CRCW040210K2FKED"))
    )
    (comp (ref "R51")
      (value "40k2")
      (footprint "eagle-import:RESC1005X40N")
      (fields
        (field (name "MANUFACTURER_PART_NUMBER") "CRCW040240K2FKED")
        (field (name "MOUSER_PART_NUMBER") "71-CRCW0402-40.2K-E3")
      )
      (libsource (lib "eagle-import") (part "CRCW040240K2FKED"))
    )
    (comp (ref "U$1")
      (value "MAX-M8")
      (footprint "eagle-import:MAX-M8")
      (libsource (lib "eagle-import") (part "MAX-M8"))
    )
    (comp (ref "C1")
      (value "C3216X7R1V106K160AC")
      (footprint "eagle-import:CAPC3216X180N")
      (fields (field (name "MOUSER_PART_NUMBER") "810-C3216X7R1V106KAC"))
      (libsource (lib "eagle-import") (part "C3216X7R1V106K160AC"))
    )
    (comp (ref "C2")
      (value "100n")
      (footprint "eagle-import:CAPC1005X55N")
      (fields (field (name "MANUFACTURER_PART_NUMBER") "GCM155R71C104KA55J"))
      (libsource (lib "eagle-import") (part "GCM155R71C104KA55J"))
    )
    (comp (ref "C3")
      (value "10p")
      (footprint "eagle-import:CAPC1005X55N")
      (fields (field (name "MANUFACTURER_PART_NUMBER") "GCM1555C1H100JA16D"))
      (libsource (lib "eagle-import") (part "GCM1555C1H100JA16D"))
    )
    (comp (ref "C4")
      (value "2n2")
      (footprint "eagle-import:CAPC1005X55N")
      (fields
        (field (name "MANUFACTURER_PART_NUMBER") "GRM155R71H222KA01D")
        (field (name "MOUSER_PART_NUMBER") "81-GRM36X222K50")
      )
      (libsource (lib "eagle-import") (part "GRM155R71H222KA01D"))
    )
    (comp (ref "C5")
      (value "8n2")
      (footprint "eagle-import:CAPC1005X55N")
      (fields
        (field (name "MANUFACTURER_PART_NUMBER") "GRM155R71C822KA01D")
        (field (name "MOUSER_PART_NUMBER") "81-GRM155R71C822KA1D")
      )
      (libsource (lib "eagle-import") (part "GRM155R71C822KA01D"))
    )
    (comp (ref "C6")
      (value "10u")
      (footprint "eagle-import:CAPC2012X145N")
      (fields
        (field (name "MANUFACTURER_PART_NUMBER") "GRM21BC81C106KE15L")
        (field (name "MOUSER_PART_NUMBER") "81-GRM21BC81C106KE5L")
      )
      (libsource (lib "eagle-import") (part "GRM21BC81C106KE15L"))
    )
    (comp (ref "C7")
      (value "DSK-3R3H224U-HL")
      (footprint "eagle-import:DSK-414_HL")
      (fields (field (name "MOUSER_PART_NUMBER") "555-DSK3R3H224U-HL"))
      (libsource (lib "eagle-import") (part "DSK-3R3H224U-HL"))
    )
    (comp (ref "C8")
      (value "1u")
      (footprint "eagle-import:CAPC1005X55N")
      (fields
        (field (name "MANUFACTURER_PART_NUMBER") "GRM155R61C105MA12D")
        (field (name "MOUSER_PART_NUMBER") "81-GRM155R61C105MA2D")
      )
      (libsource (lib "eagle-import") (part "GRM155R61C105MA12D"))
    )
    (comp (ref "C9")
      (value "1u")
      (footprint "eagle-import:CAPC1005X55N")
      (fields
        (field (name "MANUFACTURER_PART_NUMBER") "GRM155R61C105MA12D")
        (field (name "MOUSER_PART_NUMBER") "81-GRM155R61C105MA2D")
      )
      (libsource (lib "eagle-import") (part "GRM155R61C105MA12D"))
    )
    (comp (ref "C10")
      (value "C3216X7R1V106K160AC")
      (footprint "eagle-import:CAPC3216X180N")
      (fields (field (name "MOUSER_PART_NUMBER") "810-C3216X7R1V106KAC"))
      (libsource (lib "eagle-import") (part "C3216X7R1V106K160AC"))
    )
    (comp (ref "C11")
      (value "10u")
      (footprint "eagle-import:CAPC2012X145N")
      (fields
        (field (name "MANUFACTURER_PART_NUMBER") "GRM21BC81C106KE15L")
        (field (name "MOUSER_PART_NUMBER") "81-GRM21BC81C106KE5L")
      )
      (libsource (lib "eagle-import") (part "GRM21BC81C106KE15L"))
    )
    (comp (ref "C12")
      (value "C2012X5R1V106K085AC")
      (footprint "eagle-import:CAPC2012X100N")
      (fields (field (name "MOUSER_PART_NUMBER") "810-C2012X5R1V106K0C"))
      (libsource (lib "eagle-import") (part "C2012X5R1V106K085AC"))
    )
    (comp (ref "C13")
      (value "C2012X5R1V106K085AC")
      (footprint "eagle-import:CAPC2012X100N")
      (fields (field (name "MOUSER_PART_NUMBER") "810-C2012X5R1V106K0C"))
      (libsource (lib "eagle-import") (part "C2012X5R1V106K085AC"))
    )
    (comp (ref "C14")
      (value "C2012X5R1A336M125AC")
      (footprint "eagle-import:CAPC2012X145N")
      (fields (field (name "MOUSER_PART_NUMBER") "810-C2012X5R1A336M"))
      (libsource (lib "eagle-import") (part "C2012X5R1A336M125AC"))
    )
    (comp (ref "C15")
      (value "GRM188R71H104KA93D")
      (footprint "eagle-import:CAPC1608X90N")
      (fields (field (name "MOUSER_PART_NUMBER") "81-GRM39X104K50D"))
      (libsource (lib "eagle-import") (part "GRM188R71H104KA93D"))
    )
    (comp (ref "C38")
      (value "100n")
      (footprint "eagle-import:CAPC1005X55N")
      (fields (field (name "MANUFACTURER_PART_NUMBER") "GCM155R71C104KA55J"))
      (libsource (lib "eagle-import") (part "GCM155R71C104KA55J"))
    )
    (comp (ref "C39")
      (value "GRM188R71H104KA93D")
      (footprint "eagle-import:CAPC1608X90N")
      (fields (field (name "MOUSER_PART_NUMBER") "81-GRM39X104K50D"))
      (libsource (lib "eagle-import") (part "GRM188R71H104KA93D"))
    )
    (comp (ref "D1")
      (value "SS13FL")
      (footprint "eagle-import:SODFL3617X108N")
      (fields (field (name "MOUSER_PART_NUMBER") "512-SS13FL"))
      (libsource (lib "eagle-import") (part "SS13FL"))
    )
    (comp (ref "D9")
      (value "BAT60AE6327HTSA1")
      (footprint "eagle-import:SOD2513X110N")
      (fields (field (name "MOUSER_PART_NUMBER") "726-BAT60AE6327HTSA1"))
      (libsource (lib "eagle-import") (part "BAT60AE6327HTSA1"))
    )
    (comp (ref "F1")
      (value "MINISMDC050F-2")
      (footprint "eagle-import:FUSC4632X62N")
      (fields (field (name "MOUSER_PART_NUMBER") "650-MINISMDC050F-2"))
      (libsource (lib "eagle-import") (part "MINISMDC050F-2"))
    )
    (comp (ref "F2")
      (value "MINISMDC150F_24-2")
      (footprint "eagle-import:FUSC4632X194N")
      (fields
        (field (name "MANUFACTURER_PART_NUMBER") "MINISMDC150F/24-2")
        (field (name "MOUSER_PART_NUMBER") "650-MINISMDC150F/24")
      )
      (libsource (lib "eagle-import") (part "MINISMDC150F_24-2"))
    )
    (comp (ref "IC3")
      (value "AP2112K-3.3TRG1")
      (footprint "eagle-import:SOT95P282X130-5N")
      (fields (field (name "MOUSER_PART_NUMBER") "621-AP2112K-3.3TRG1"))
      (libsource (lib "eagle-import") (part "AP2112K-3.3TRG1"))
    )
    (comp (ref "IC4")
      (value "TPS54232D")
      (footprint "eagle-import:SOIC127P600X175-8N")
      (fields (field (name "MOUSER_PART_NUMBER") "595-TPS54232D"))
      (libsource (lib "eagle-import") (part "TPS54232D"))
    )
    (comp (ref "IC5")
      (value "TPS563231DRLR")
      (footprint "eagle-import:SOTFL50P160X60-6N")
      (fields (field (name "MOUSER_PART_NUMBER") "595-TPS563231DRLR"))
      (libsource (lib "eagle-import") (part "TPS563231DRLR"))
    )
    (comp (ref "L1")
      (value "SRN6045-150M")
      (footprint "eagle-import:SRN6045_1")
      (fields (field (name "MOUSER_PART_NUMBER") "652-SRN6045-150M"))
      (libsource (lib "eagle-import") (part "SRN6045-150M"))
    )
    (comp (ref "L2")
      (value "SRU1048-4R7Y")
      (footprint "eagle-import:SRU10484R7Y")
      (fields (field (name "MOUSER_PART_NUMBER") "652-SRU1048-4R7Y"))
      (libsource (lib "eagle-import") (part "SRU1048-4R7Y"))
    )
    (comp (ref "Q7")
      (value "NTR4502PT1G")
      (footprint "eagle-import:SOT96P237X111-3N")
      (fields (field (name "MOUSER_PART_NUMBER") "863-NTR4502PT1G"))
      (libsource (lib "eagle-import") (part "NTR4502PT1G"))
    )
    (comp (ref "R1")
      (value "10k2")
      (footprint "eagle-import:RESC1005X40N")
      (fields
        (field (name "MANUFACTURER_PART_NUMBER") "CRCW040210K2FKED")
        (field (name "MOUSER_PART_NUMBER") "71-CRCW0402-10.2K-E3")
      )
      (libsource (lib "eagle-import") (part "CRCW040210K2FKED"))
    )
    (comp (ref "R2")
      (value "1k96")
      (footprint "eagle-import:RESC1005X40N")
      (fields
        (field (name "MANUFACTURER_PART_NUMBER") "CRCW04021K96FKED")
        (field (name "MOUSER_PART_NUMBER") "71-CRCW0402-1.96K-E3")
      )
      (libsource (lib "eagle-import") (part "CRCW04021K96FKED"))
    )
    (comp (ref "R3")
      (value "28k")
      (footprint "eagle-import:RESC1005X40N")
      (fields
        (field (name "MANUFACTURER_PART_NUMBER") "CRCW040228K0FKED")
        (field (name "MOUSER_PART_NUMBER") "71-CRCW0402-28K-E3")
      )
      (libsource (lib "eagle-import") (part "CRCW040228K0FKED"))
    )
    (comp (ref "R4")
      (value "10k")
      (footprint "eagle-import:RESC1508X50N")
      (fields (field (name "MANUFACTURER_PART_NUMBER") "RNCP0603FTD10K0"))
      (libsource (lib "eagle-import") (part "RNCP0603FTD10K0"))
    )
    (comp (ref "R5")
      (value "0R")
      (footprint "eagle-import:RESC1005X40N")
      (fields (field (name "MANUFACTURER_PART_NUMBER") "RMCF0402ZT0R00"))
      (libsource (lib "eagle-import") (part "RMCF0402ZT0R00"))
    )
    (comp (ref "R7")
      (value "CRCW040237K4FKED")
      (footprint "eagle-import:RESC1005X40N")
      (fields (field (name "MOUSER_PART_NUMBER") "71-CRCW0402-37.4K-E3"))
      (libsource (lib "eagle-import") (part "CRCW040237K4FKED"))
    )
    (comp (ref "R8")
      (value "CRCW0402169KFKED")
      (footprint "eagle-import:RESC1005X40N")
      (fields (field (name "MOUSER_PART_NUMBER") "71-CRCW0402-169K-E3"))
      (libsource (lib "eagle-import") (part "CRCW0402169KFKED"))
    )
    (comp (ref "R9")
      (value "CRCW040253K6FKED")
      (footprint "eagle-import:RESC1005X40N")
      (fields (field (name "MOUSER_PART_NUMBER") "71-CRCW0402-53.6K-E3"))
      (libsource (lib "eagle-import") (part "CRCW040253K6FKED"))
    )
    (comp (ref "R10")
      (value "RC0201FR-0710KL")
      (footprint "eagle-import:RESC0603X26N")
      (fields (field (name "MOUSER_PART_NUMBER") "603-RC0201FR-0710KL"))
      (libsource (lib "eagle-import") (part "RC0201FR-0710KL"))
    )
    (comp (ref "R49")
      (value "28k")
      (footprint "eagle-import:RESC1005X40N")
      (fields
        (field (name "MANUFACTURER_PART_NUMBER") "CRCW040228K0FKED")
        (field (name "MOUSER_PART_NUMBER") "71-CRCW0402-28K-E3")
      )
      (libsource (lib "eagle-import") (part "CRCW040228K0FKED"))
    )
    (comp (ref "TP3V3")
      (value "PTR1TP06R")
      (footprint "eagle-import:TP06R")
      (libsource (lib "eagle-import") (part "PTR1TP06R"))
    )
    (comp (ref "TP3V8")
      (value "PTR1TP06R")
      (footprint "eagle-import:TP06R")
      (libsource (lib "eagle-import") (part "PTR1TP06R"))
    )
    (comp (ref "TP5V")
      (value "PTR1TP06R")
      (footprint "eagle-import:TP06R")
      (libsource (lib "eagle-import") (part "PTR1TP06R"))
    )
    (comp (ref "Z1")
      (value "BZX84C18LT1G")
      (footprint "eagle-import:SOT95P237X111-3N")
      (fields (field (name "MOUSER_PART_NUMBER") "863-BZX84C18LT1G"))
      (libsource (lib "eagle-import") (part "BZX84C18LT1G"))
    )
    (comp (ref "BT_IRQ")
      (value "PTR1TP06R")
      (footprint "eagle-import:TP06R")
      (libsource (lib "eagle-import") (part "PTR1TP06R"))
    )
    (comp (ref "BT_RST")
      (value "PTR1TP06R")
      (footprint "eagle-import:TP06R")
      (libsource (lib "eagle-import") (part "PTR1TP06R"))
    )
    (comp (ref "BT_SS")
      (value "PTR1TP06R")
      (footprint "eagle-import:TP06R")
      (libsource (lib "eagle-import") (part "PTR1TP06R"))
    )
    (comp (ref "C31")
      (value "100n")
      (footprint "eagle-import:CAPC1005X55N")
      (fields (field (name "MANUFACTURER_PART_NUMBER") "GCM155R71C104KA55J"))
      (libsource (lib "eagle-import") (part "GCM155R71C104KA55J"))
    )
    (comp (ref "C32")
      (value "10u")
      (footprint "eagle-import:CAPC1005X55N")
      (fields
        (field (name "MANUFACTURER_PART_NUMBER") "GRM155C80J106ME11D")
        (field (name "MOUSER_PART_NUMBER") "81-GRM155C80J106ME1D")
      )
      (libsource (lib "eagle-import") (part "GRM155C80J106ME11D"))
    )
    (comp (ref "C33")
      (value "100n")
      (footprint "eagle-import:CAPC1005X55N")
      (fields (field (name "MANUFACTURER_PART_NUMBER") "GCM155R71C104KA55J"))
      (libsource (lib "eagle-import") (part "GCM155R71C104KA55J"))
    )
    (comp (ref "C54")
      (value "100n")
      (footprint "eagle-import:CAPC1005X55N")
      (fields (field (name "MANUFACTURER_PART_NUMBER") "GCM155R71C104KA55J"))
      (libsource (lib "eagle-import") (part "GCM155R71C104KA55J"))
    )
    (comp (ref "D10")
      (value "MBR0560-TP")
      (footprint "eagle-import:SOD3716X135N")
      (fields (field (name "MOUSER_PART_NUMBER") "833-MBR0560-TP"))
      (libsource (lib "eagle-import") (part "MBR0560-TP"))
    )
    (comp (ref "D11")
      (value "MBR0560-TP")
      (footprint "eagle-import:SOD3716X135N")
      (fields (field (name "MOUSER_PART_NUMBER") "833-MBR0560-TP"))
      (libsource (lib "eagle-import") (part "MBR0560-TP"))
    )
    (comp (ref "FL_SS")
      (value "PTR1TP06R")
      (footprint "eagle-import:TP06R")
      (libsource (lib "eagle-import") (part "PTR1TP06R"))
    )
    (comp (ref "IC6")
      (value "ATECC508A-MAHDA-T")
      (footprint "eagle-import:SON50P300X200X60-9N")
      (fields (field (name "MOUSER_PART_NUMBER") "556-ATECC508A-MAHDAT"))
      (libsource (lib "eagle-import") (part "ATECC508A-MAHDA-T"))
    )
    (comp (ref "IC7")
      (value "SPBTLE-RF")
      (footprint "eagle-import:XCVR_SPBTLE-RF")
      (fields (field (name "MF") "STMicroelectronics"))
      (libsource (lib "eagle-import") (part "SPBTLE-RF"))
    )
    (comp (ref "IC8")
      (value "W25Q16JVZPIQ")
      (footprint "eagle-import:SON127P600X500X80-9N")
      (fields (field (name "MOUSER_PART_NUMBER") "454-W25Q16JVZPIQ"))
      (libsource (lib "eagle-import") (part "W25Q16JVZPIQ"))
    )
    (comp (ref "J2")
      (value "1040310811")
      (footprint "eagle-import:1040310811")
      (libsource (lib "eagle-import") (part "1040310811"))
    )
    (comp (ref "K1")
      (value "EE2-3TNU-L")
      (footprint "eagle-import:EE25TNU")
      (fields (field (name "MOUSER_PART_NUMBER") "80-EE2-3TNU-L"))
      (libsource (lib "eagle-import") (part "EE2-3TNU-L"))
    )
    (comp (ref "Q1")
      (value "2N7002DW-7-F")
      (footprint "eagle-import:SOT65P210X100-6N")
      (fields (field (name "MOUSER_PART_NUMBER") "621-2N7002DW-F"))
      (libsource (lib "eagle-import") (part "2N7002DW-7-F"))
    )
    (comp (ref "Q5")
      (value "BSP76E6433HUMA1")
      (footprint "eagle-import:SOT230P700X170-4N")
      (libsource (lib "eagle-import") (part "BSP76E6433HUMA1"))
    )
    (comp (ref "Q6")
      (value "BSP76E6433HUMA1")
      (footprint "eagle-import:SOT230P700X170-4N")
      (libsource (lib "eagle-import") (part "BSP76E6433HUMA1"))
    )
    (comp (ref "R11")
      (value "1M2")
      (footprint "eagle-import:RESC1005X40N")
      (fields
        (field (name "MANUFACTURER_PART_NUMBER") "CRCW04021M20FKED")
        (field (name "MOUSER_PART_NUMBER") "71-CRCW04021M20FKED")
      )
      (libsource (lib "eagle-import") (part "CRCW04021M20FKED"))
    )
    (comp (ref "R12")
      (value "1M2")
      (footprint "eagle-import:RESC1005X40N")
      (fields
        (field (name "MANUFACTURER_PART_NUMBER") "CRCW04021M20FKED")
        (field (name "MOUSER_PART_NUMBER") "71-CRCW04021M20FKED")
      )
      (libsource (lib "eagle-import") (part "CRCW04021M20FKED"))
    )
    (comp (ref "R20")
      (value "0R")
      (footprint "eagle-import:RESC3116X65N")
      (fields
        (field (name "MANUFACTURER_PART_NUMBER") "CRG1206ZR")
        (field (name "MOUSER_PART_NUMBER") "279-CRG1206ZR")
      )
      (libsource (lib "eagle-import") (part "CRG1206ZR"))
    )
    (comp (ref "R21")
      (value "0R")
      (footprint "eagle-import:RESC3116X65N")
      (fields
        (field (name "MANUFACTURER_PART_NUMBER") "CRG1206ZR")
        (field (name "MOUSER_PART_NUMBER") "279-CRG1206ZR")
      )
      (libsource (lib "eagle-import") (part "CRG1206ZR"))
    )
    (comp (ref "R22")
      (value "10k2")
      (footprint "eagle-import:RESC1005X40N")
      (fields
        (field (name "MANUFACTURER_PART_NUMBER") "CRCW040210K2FKED")
        (field (name "MOUSER_PART_NUMBER") "71-CRCW0402-10.2K-E3")
      )
      (libsource (lib "eagle-import") (part "CRCW040210K2FKED"))
    )
    (comp (ref "R23")
      (value "10k2")
      (footprint "eagle-import:RESC1005X40N")
      (fields
        (field (name "MANUFACTURER_PART_NUMBER") "CRCW040210K2FKED")
        (field (name "MOUSER_PART_NUMBER") "71-CRCW0402-10.2K-E3")
      )
      (libsource (lib "eagle-import") (part "CRCW040210K2FKED"))
    )
    (comp (ref "R35")
      (value "40k2")
      (footprint "eagle-import:RESC1005X40N")
      (fields
        (field (name "MANUFACTURER_PART_NUMBER") "CRCW040240K2FKED")
        (field (name "MOUSER_PART_NUMBER") "71-CRCW0402-40.2K-E3")
      )
      (libsource (lib "eagle-import") (part "CRCW040240K2FKED"))
    )
    (comp (ref "R36")
      (value "10k2")
      (footprint "eagle-import:RESC1005X40N")
      (fields
        (field (name "MANUFACTURER_PART_NUMBER") "CRCW040210K2FKED")
        (field (name "MOUSER_PART_NUMBER") "71-CRCW0402-10.2K-E3")
      )
      (libsource (lib "eagle-import") (part "CRCW040210K2FKED"))
    )
    (comp (ref "R42")
      (value "10k2")
      (footprint "eagle-import:RESC1005X40N")
      (fields
        (field (name "MANUFACTURER_PART_NUMBER") "CRCW040210K2FKED")
        (field (name "MOUSER_PART_NUMBER") "71-CRCW0402-10.2K-E3")
      )
      (libsource (lib "eagle-import") (part "CRCW040210K2FKED"))
    )
    (comp (ref "R43")
      (value "10k2")
      (footprint "eagle-import:RESC1005X40N")
      (fields
        (field (name "MANUFACTURER_PART_NUMBER") "CRCW040210K2FKED")
        (field (name "MOUSER_PART_NUMBER") "71-CRCW0402-10.2K-E3")
      )
      (libsource (lib "eagle-import") (part "CRCW040210K2FKED"))
    )
    (comp (ref "SD_SS")
      (value "PTR1TP06R")
      (footprint "eagle-import:TP06R")
      (libsource (lib "eagle-import") (part "PTR1TP06R"))
    )
    (comp (ref "SPI1_MISO")
      (value "PTR1TP06R")
      (footprint "eagle-import:TP06R")
      (libsource (lib "eagle-import") (part "PTR1TP06R"))
    )
    (comp (ref "SPI1_MOSI")
      (value "PTR1TP06R")
      (footprint "eagle-import:TP06R")
      (libsource (lib "eagle-import") (part "PTR1TP06R"))
    )
    (comp (ref "SPI1_SCK")
      (value "PTR1TP06R")
      (footprint "eagle-import:TP06R")
      (libsource (lib "eagle-import") (part "PTR1TP06R"))
    )
    (comp (ref "SPI2_MISO")
      (value "PTR1TP06R")
      (footprint "eagle-import:TP06R")
      (libsource (lib "eagle-import") (part "PTR1TP06R"))
    )
    (comp (ref "SPI2_MOSI")
      (value "PTR1TP06R")
      (footprint "eagle-import:TP06R")
      (libsource (lib "eagle-import") (part "PTR1TP06R"))
    )
    (comp (ref "SPI2_SCK")
      (value "PTR1TP06R")
      (footprint "eagle-import:TP06R")
      (libsource (lib "eagle-import") (part "PTR1TP06R"))
    )
    (comp (ref "TP_SCL")
      (value "PTR1TP06R")
      (footprint "eagle-import:TP06R")
      (libsource (lib "eagle-import") (part "PTR1TP06R"))
    )
    (comp (ref "TP_SDA")
      (value "PTR1TP06R")
      (footprint "eagle-import:TP06R")
      (libsource (lib "eagle-import") (part "PTR1TP06R"))
    )
    (comp (ref "C0_RX")
      (value "PTR1TP06R")
      (footprint "eagle-import:TP06R")
      (libsource (lib "eagle-import") (part "PTR1TP06R"))
    )
    (comp (ref "C0_STB")
      (value "PTR1TP06R")
      (footprint "eagle-import:TP06R")
      (libsource (lib "eagle-import") (part "PTR1TP06R"))
    )
    (comp (ref "C0_TX")
      (value "PTR1TP06R")
      (footprint "eagle-import:TP06R")
      (libsource (lib "eagle-import") (part "PTR1TP06R"))
    )
    (comp (ref "C1_RX")
      (value "PTR1TP06R")
      (footprint "eagle-import:TP06R")
      (libsource (lib "eagle-import") (part "PTR1TP06R"))
    )
    (comp (ref "C1_STB")
      (value "PTR1TP06R")
      (footprint "eagle-import:TP06R")
      (libsource (lib "eagle-import") (part "PTR1TP06R"))
    )
    (comp (ref "C1_TX")
      (value "PTR1TP06R")
      (footprint "eagle-import:TP06R")
      (libsource (lib "eagle-import") (part "PTR1TP06R"))
    )
    (comp (ref "C34")
      (value "100n")
      (footprint "eagle-import:CAPC1005X55N")
      (fields (field (name "MANUFACTURER_PART_NUMBER") "GCM155R71C104KA55J"))
      (libsource (lib "eagle-import") (part "GCM155R71C104KA55J"))
    )
    (comp (ref "C35")
      (value "100n")
      (footprint "eagle-import:CAPC1005X55N")
      (fields (field (name "MANUFACTURER_PART_NUMBER") "GCM155R71C104KA55J"))
      (libsource (lib "eagle-import") (part "GCM155R71C104KA55J"))
    )
    (comp (ref "C52")
      (value "100n")
      (footprint "eagle-import:CAPC1005X55N")
      (fields (field (name "MANUFACTURER_PART_NUMBER") "GCM155R71C104KA55J"))
      (libsource (lib "eagle-import") (part "GCM155R71C104KA55J"))
    )
    (comp (ref "C53")
      (value "100n")
      (footprint "eagle-import:CAPC1005X55N")
      (fields (field (name "MANUFACTURER_PART_NUMBER") "GCM155R71C104KA55J"))
      (libsource (lib "eagle-import") (part "GCM155R71C104KA55J"))
    )
    (comp (ref "D5")
      (value "PESD0402-140")
      (footprint "eagle-import:DIONC1005X43N")
      (libsource (lib "eagle-import") (part "PESD0402-140"))
    )
    (comp (ref "D6")
      (value "PESD0402-140")
      (footprint "eagle-import:DIONC1005X43N")
      (libsource (lib "eagle-import") (part "PESD0402-140"))
    )
    (comp (ref "D7")
      (value "PESD0402-140")
      (footprint "eagle-import:DIONC1005X43N")
      (libsource (lib "eagle-import") (part "PESD0402-140"))
    )
    (comp (ref "D8")
      (value "PESD0402-140")
      (footprint "eagle-import:DIONC1005X43N")
      (libsource (lib "eagle-import") (part "PESD0402-140"))
    )
    (comp (ref "IC9")
      (value "TJA1048TK,118")
      (footprint "eagle-import:SON65P300X450X100-15N")
      (fields (field (name "MOUSER_PART_NUMBER") "771-TJA1048TK118"))
      (libsource (lib "eagle-import") (part "TJA1048TK,118"))
    )
    (comp (ref "IC10")
      (value "MCP2515T-I_ST")
      (footprint "eagle-import:SOP65P640X120-20N")
      (fields
        (field (name "MANUFACTURER_PART_NUMBER") "MCP2515T-I/ST")
        (field (name "MOUSER_PART_NUMBER") "579-MCP2515T-I/ST")
      )
      (libsource (lib "eagle-import") (part "MCP2515T-I_ST"))
    )
    (comp (ref "IC11")
      (value "MCP2515T-I_ST")
      (footprint "eagle-import:SOP65P640X120-20N")
      (fields
        (field (name "MANUFACTURER_PART_NUMBER") "MCP2515T-I/ST")
        (field (name "MOUSER_PART_NUMBER") "579-MCP2515T-I/ST")
      )
      (libsource (lib "eagle-import") (part "MCP2515T-I_ST"))
    )
    (comp (ref "IC12")
      (value "CSTCE16M0V53C-R0")
      (footprint "eagle-import:CSTCE16M0V53CR0")
      (fields (field (name "MOUSER_PART_NUMBER") "81-CSTCE16M0V53C-R0"))
      (libsource (lib "eagle-import") (part "CSTCE16M0V53C-R0"))
    )
    (comp (ref "IC13")
      (value "CSTCE16M0V53C-R0")
      (footprint "eagle-import:CSTCE16M0V53CR0")
      (fields (field (name "MOUSER_PART_NUMBER") "81-CSTCE16M0V53C-R0"))
      (libsource (lib "eagle-import") (part "CSTCE16M0V53C-R0"))
    )
    (comp (ref "R24")
      (value "10k2")
      (footprint "eagle-import:RESC1005X40N")
      (fields
        (field (name "MANUFACTURER_PART_NUMBER") "CRCW040210K2FKED")
        (field (name "MOUSER_PART_NUMBER") "71-CRCW0402-10.2K-E3")
      )
      (libsource (lib "eagle-import") (part "CRCW040210K2FKED"))
    )
    (comp (ref "R25")
      (value "10k2")
      (footprint "eagle-import:RESC1005X40N")
      (fields
        (field (name "MANUFACTURER_PART_NUMBER") "CRCW040210K2FKED")
        (field (name "MOUSER_PART_NUMBER") "71-CRCW0402-10.2K-E3")
      )
      (libsource (lib "eagle-import") (part "CRCW040210K2FKED"))
    )
    (comp (ref "R26")
      (value "10k2")
      (footprint "eagle-import:RESC1005X40N")
      (fields
        (field (name "MANUFACTURER_PART_NUMBER") "CRCW040210K2FKED")
        (field (name "MOUSER_PART_NUMBER") "71-CRCW0402-10.2K-E3")
      )
      (libsource (lib "eagle-import") (part "CRCW040210K2FKED"))
    )
    (comp (ref "R27")
      (value "10k2")
      (footprint "eagle-import:RESC1005X40N")
      (fields
        (field (name "MANUFACTURER_PART_NUMBER") "CRCW040210K2FKED")
        (field (name "MOUSER_PART_NUMBER") "71-CRCW0402-10.2K-E3")
      )
      (libsource (lib "eagle-import") (part "CRCW040210K2FKED"))
    )
    (comp (ref "R28")
      (value "10k2")
      (footprint "eagle-import:RESC1005X40N")
      (fields
        (field (name "MANUFACTURER_PART_NUMBER") "CRCW040210K2FKED")
        (field (name "MOUSER_PART_NUMBER") "71-CRCW0402-10.2K-E3")
      )
      (libsource (lib "eagle-import") (part "CRCW040210K2FKED"))
    )
    (comp (ref "R29")
      (value "10k2")
      (footprint "eagle-import:RESC1005X40N")
      (fields
        (field (name "MANUFACTURER_PART_NUMBER") "CRCW040210K2FKED")
        (field (name "MOUSER_PART_NUMBER") "71-CRCW0402-10.2K-E3")
      )
      (libsource (lib "eagle-import") (part "CRCW040210K2FKED"))
    )
    (comp (ref "R30")
      (value "10k2")
      (footprint "eagle-import:RESC1005X40N")
      (fields
        (field (name "MANUFACTURER_PART_NUMBER") "CRCW040210K2FKED")
        (field (name "MOUSER_PART_NUMBER") "71-CRCW0402-10.2K-E3")
      )
      (libsource (lib "eagle-import") (part "CRCW040210K2FKED"))
    )
    (comp (ref "R31")
      (value "10k2")
      (footprint "eagle-import:RESC1005X40N")
      (fields
        (field (name "MANUFACTURER_PART_NUMBER") "CRCW040210K2FKED")
        (field (name "MOUSER_PART_NUMBER") "71-CRCW0402-10.2K-E3")
      )
      (libsource (lib "eagle-import") (part "CRCW040210K2FKED"))
    )
    (comp (ref "R44")
      (value "10k2")
      (footprint "eagle-import:RESC1005X40N")
      (fields
        (field (name "MANUFACTURER_PART_NUMBER") "CRCW040210K2FKED")
        (field (name "MOUSER_PART_NUMBER") "71-CRCW0402-10.2K-E3")
      )
      (libsource (lib "eagle-import") (part "CRCW040210K2FKED"))
    )
    (comp (ref "R45")
      (value "10k2")
      (footprint "eagle-import:RESC1005X40N")
      (fields
        (field (name "MANUFACTURER_PART_NUMBER") "CRCW040210K2FKED")
        (field (name "MOUSER_PART_NUMBER") "71-CRCW0402-10.2K-E3")
      )
      (libsource (lib "eagle-import") (part "CRCW040210K2FKED"))
    )
  )
  (nets
    (net (code "1") (name "+1V8") (class "Default")
      (node (ref "C44") (pin "1") (pinfunction "1_1") (pintype "bidirectional"))
      (node (ref "IC2") (pin "4") (pinfunction "V_INT_4") (pintype "bidirectional"))
      (node (ref "R16") (pin "2") (pinfunction "2_2") (pintype "bidirectional"))
      (node (ref "R17") (pin "2") (pinfunction "2_2") (pintype "bidirectional"))
      (node (ref "TP_1V8") (pin "TP") (pinfunction "TP_TP") (pintype "input"))
      (node (ref "U1") (pin "6") (pinfunction "VCCB_6") (pintype "power_in"))
    )
    (net (code "2") (name "+3V3") (class "Default")
      (node (ref "C18") (pin "2") (pinfunction "2_2") (pintype "bidirectional"))
      (node (ref "C19") (pin "2") (pinfunction "2_2") (pintype "bidirectional"))
      (node (ref "C30") (pin "1") (pinfunction "1_1") (pintype "bidirectional"))
      (node (ref "C31") (pin "2") (pinfunction "2_2") (pintype "bidirectional"))
      (node (ref "C32") (pin "2") (pinfunction "2_2") (pintype "bidirectional"))
      (node (ref "C33") (pin "2") (pinfunction "2_2") (pintype "bidirectional"))
      (node (ref "C34") (pin "2") (pinfunction "2_2") (pintype "bidirectional"))
      (node (ref "C36") (pin "1") (pinfunction "1_1") (pintype "bidirectional"))
      (node (ref "C37") (pin "1") (pinfunction "1_1") (pintype "bidirectional"))
      (node (ref "C45") (pin "2") (pinfunction "2_2") (pintype "bidirectional"))
      (node (ref "C50") (pin "1") (pinfunction "1_1") (pintype "bidirectional"))
      (node (ref "C51") (pin "2") (pinfunction "2_2") (pintype "bidirectional"))
      (node (ref "C52") (pin "1") (pinfunction "1_1") (pintype "bidirectional"))
      (node (ref "C53") (pin "1") (pinfunction "1_1") (pintype "bidirectional"))
      (node (ref "C54") (pin "2") (pinfunction "2_2") (pintype "bidirectional"))
      (node (ref "C56") (pin "1") (pinfunction "1_1") (pintype "bidirectional"))
      (node (ref "C58") (pin "2") (pinfunction "2_2") (pintype "bidirectional"))
      (node (ref "C8") (pin "2") (pinfunction "2_2") (pintype "bidirectional"))
      (node (ref "D10") (pin "1") (pinfunction "K_1") (pintype "bidirectional"))
      (node (ref "D11") (pin "1") (pinfunction "K_1") (pintype "bidirectional"))
      (node (ref "FB1") (pin "1") (pinfunction "1_1") (pintype "bidirectional"))
      (node (ref "IC1") (pin "17") (pinfunction "VDDIO_1_17") (pintype "bidirectional"))
      (node (ref "IC1") (pin "36") (pinfunction "VDDIO_2_36") (pintype "bidirectional"))
      (node (ref "IC1") (pin "44") (pinfunction "VDDIN_44") (pintype "bidirectional"))
      (node (ref "IC10") (pin "20") (pinfunction "VDD_20") (pintype "bidirectional"))
      (node (ref "IC11") (pin "20") (pinfunction "VDD_20") (pintype "bidirectional"))
      (node (ref "IC14") (pin "13") (pinfunction "VDD_13") (pintype "bidirectional"))
      (node (ref "IC14") (pin "8") (pinfunction "VLOGIC_8") (pintype "bidirectional"))
      (node (ref "IC3") (pin "5") (pinfunction "VOUT_5") (pintype "bidirectional"))
      (node (ref "IC6") (pin "8") (pinfunction "VCC_8") (pintype "bidirectional"))
      (node (ref "IC7") (pin "5") (pinfunction "VIN_5") (pintype "power_in"))
      (node (ref "IC8") (pin "3") (pinfunction "IO2_3") (pintype "bidirectional"))
      (node (ref "IC8") (pin "7") (pinfunction "IO3_7") (pintype "bidirectional"))
      (node (ref "IC8") (pin "8") (pinfunction "VCC_8") (pintype "bidirectional"))
      (node (ref "IC9") (pin "11") (pinfunction "VIO_11") (pintype "bidirectional"))
      (node (ref "J2") (pin "4") (pinfunction "VDD_4") (pintype "bidirectional"))
      (node (ref "J7") (pin "1") (pinfunction "1_1") (pintype "bidirectional"))
      (node (ref "K1") (pin "1") (pinfunction "SET_COIL_+_1") (pintype "bidirectional"))
      (node (ref "K1") (pin "6") (pinfunction "RESET_COIL_+_6") (pintype "bidirectional"))
      (node (ref "R22") (pin "2") (pinfunction "2_2") (pintype "bidirectional"))
      (node (ref "R23") (pin "2") (pinfunction "2_2") (pintype "bidirectional"))
      (node (ref "R24") (pin "2") (pinfunction "2_2") (pintype "bidirectional"))
      (node (ref "R25") (pin "2") (pinfunction "2_2") (pintype "bidirectional"))
      (node (ref "R26") (pin "2") (pinfunction "2_2") (pintype "bidirectional"))
      (node (ref "R27") (pin "2") (pinfunction "2_2") (pintype "bidirectional"))
      (node (ref "R28") (pin "2") (pinfunction "2_2") (pintype "bidirectional"))
      (node (ref "R29") (pin "2") (pinfunction "2_2") (pintype "bidirectional"))
      (node (ref "R30") (pin "2") (pinfunction "2_2") (pintype "bidirectional"))
      (node (ref "R31") (pin "2") (pinfunction "2_2") (pintype "bidirectional"))
      (node (ref "R32") (pin "2") (pinfunction "2_2") (pintype "bidirectional"))
      (node (ref "R4") (pin "2") (pinfunction "2_2") (pintype "bidirectional"))
      (node (ref "R40") (pin "2") (pinfunction "2_2") (pintype "bidirectional"))
      (node (ref "R42") (pin "2") (pinfunction "2_2") (pintype "bidirectional"))
      (node (ref "R43") (pin "2") (pinfunction "2_2") (pintype "bidirectional"))
      (node (ref "R46") (pin "2") (pinfunction "2_2") (pintype "bidirectional"))
      (node (ref "R47") (pin "2") (pinfunction "2_2") (pintype "bidirectional"))
      (node (ref "TP3V3") (pin "TP") (pinfunction "TP_TP") (pintype "input"))
      (node (ref "U$1") (pin "7_VCC_IO") (pinfunction "7_VCC_IO_7_VCC_IO") (pintype "power_in"))
      (node (ref "U$1") (pin "8_VCC") (pinfunction "8_VCC_8_VCC") (pintype "power_in"))
      (node (ref "U1") (pin "10") (pinfunction "DIR1_10") (pintype "bidirectional"))
      (node (ref "U1") (pin "7") (pinfunction "VCCA_7") (pintype "power_in"))
    )
    (net (code "3") (name "+3V8") (class "Default")
      (node (ref "C14") (pin "2") (pinfunction "2_2") (pintype "bidirectional"))
      (node (ref "C15") (pin "2") (pinfunction "2_2") (pintype "bidirectional"))
      (node (ref "C22") (pin "2") (pinfunction "2_2") (pintype "bidirectional"))
      (node (ref "C23") (pin "2") (pinfunction "2_2") (pintype "bidirectional"))
      (node (ref "C24") (pin "2") (pinfunction "2_2") (pintype "bidirectional"))
      (node (ref "C25") (pin "2") (pinfunction "2_2") (pintype "bidirectional"))
      (node (ref "C26") (pin "2") (pinfunction "2_2") (pintype "bidirectional"))
      (node (ref "C28") (pin "2") (pinfunction "2_2") (pintype "bidirectional"))
      (node (ref "C9") (pin "2") (pinfunction "2_2") (pintype "bidirectional"))
      (node (ref "IC2") (pin "51") (pinfunction "VCC_1_51") (pintype "bidirectional"))
      (node (ref "IC2") (pin "52") (pinfunction "VCC_2_52") (pintype "bidirectional"))
      (node (ref "IC2") (pin "53") (pinfunction "VCC_3_53") (pintype "bidirectional"))
      (node (ref "IC3") (pin "1") (pinfunction "VIN_1") (pintype "bidirectional"))
      (node (ref "IC3") (pin "3") (pinfunction "EN_3") (pintype "bidirectional"))
      (node (ref "L2") (pin "2") (pinfunction "2_2") (pintype "bidirectional"))
      (node (ref "R15") (pin "2") (pinfunction "2_2") (pintype "bidirectional"))
      (node (ref "R9") (pin "2") (pinfunction "2_2") (pintype "bidirectional"))
      (node (ref "TP3V8") (pin "TP") (pinfunction "TP_TP") (pintype "input"))
    )
    (net (code "4") (name "+12V") (class "Default")
      (node (ref "C1") (pin "2") (pinfunction "2_2") (pintype "bidirectional"))
      (node (ref "C10") (pin "2") (pinfunction "2_2") (pintype "bidirectional"))
      (node (ref "C12") (pin "2") (pinfunction "2_2") (pintype "bidirectional"))
      (node (ref "C13") (pin "2") (pinfunction "2_2") (pintype "bidirectional"))
      (node (ref "C39") (pin "2") (pinfunction "2_2") (pintype "bidirectional"))
      (node (ref "F1") (pin "1") (pinfunction "1_1") (pintype "bidirectional"))
      (node (ref "IC4") (pin "2") (pinfunction "VIN_2") (pintype "input"))
      (node (ref "IC5") (pin "1") (pinfunction "VIN_1") (pintype "bidirectional"))
      (node (ref "IC5") (pin "5") (pinfunction "EN_5") (pintype "bidirectional"))
      (node (ref "Q7") (pin "2") (pinfunction "S_2") (pintype "bidirectional"))
      (node (ref "R35") (pin "2") (pinfunction "2_2") (pintype "bidirectional"))
      (node (ref "R8") (pin "2") (pinfunction "2_2") (pintype "bidirectional"))
      (node (ref "Z1") (pin "3") (pinfunction "C_3") (pintype "bidirectional"))
    )
    (net (code "5") (name "12V_IN") (class "Default")
      (node (ref "F2") (pin "2") (pinfunction "2_2") (pintype "bidirectional"))
      (node (ref "J4") (pin "8") (pinfunction "8_8") (pintype "bidirectional"))
    )
    (net (code "6") (name "12V_OUT") (class "Default")
      (node (ref "F1") (pin "2") (pinfunction "2_2") (pintype "bidirectional"))
      (node (ref "J4") (pin "13") (pinfunction "13_13") (pintype "bidirectional"))
    )
    (net (code "7") (name "CAN0H_OUT") (class "Default")
      (node (ref "D8") (pin "2") (pinfunction "A_2") (pintype "bidirectional"))
      (node (ref "IC9") (pin "13") (pinfunction "CANH1_13") (pintype "bidirectional"))
      (node (ref "J4") (pin "9") (pinfunction "9_9") (pintype "bidirectional"))
    )
    (net (code "8") (name "CAN0L_OUT") (class "Default")
      (node (ref "D7") (pin "2") (pinfunction "A_2") (pintype "bidirectional"))
      (node (ref "IC9") (pin "12") (pinfunction "CANL1_12") (pintype "bidirectional"))
      (node (ref "J4") (pin "2") (pinfunction "2_2") (pintype "bidirectional"))
    )
    (net (code "9") (name "CAN1H_OUT") (class "Default")
      (node (ref "D6") (pin "2") (pinfunction "A_2") (pintype "bidirectional"))
      (node (ref "IC9") (pin "10") (pinfunction "CANH2_10") (pintype "bidirectional"))
      (node (ref "J4") (pin "10") (pinfunction "10_10") (pintype "bidirectional"))
    )
    (net (code "10") (name "CAN1L_OUT") (class "Default")
      (node (ref "D5") (pin "2") (pinfunction "A_2") (pintype "bidirectional"))
      (node (ref "IC9") (pin "9") (pinfunction "CANL2_9") (pintype "bidirectional"))
      (node (ref "J4") (pin "3") (pinfunction "3_3") (pintype "bidirectional"))
    )
    (net (code "11") (name "CAN_STB_1") (class "Default")
      (node (ref "C0_STB") (pin "TP") (pinfunction "TP_TP") (pintype "input"))
      (node (ref "IC9") (pin "14") (pinfunction "STBN1_14") (pintype "bidirectional"))
      (node (ref "R30") (pin "1") (pinfunction "1_1") (pintype "bidirectional"))
      (node (ref "R45") (pin "2") (pinfunction "2_2") (pintype "bidirectional"))
    )
    (net (code "12") (name "CAN_STB_2") (class "Default")
      (node (ref "C1_STB") (pin "TP") (pinfunction "TP_TP") (pintype "input"))
      (node (ref "IC9") (pin "8") (pinfunction "STBN2_8") (pintype "bidirectional"))
      (node (ref "R31") (pin "1") (pinfunction "1_1") (pintype "bidirectional"))
      (node (ref "R44") (pin "2") (pinfunction "2_2") (pintype "bidirectional"))
    )
    (net (code "13") (name "CODE_A_IN") (class "Default")
      (node (ref "J4") (pin "11") (pinfunction "11_11") (pintype "bidirectional"))
      (node (ref "K1") (pin "4") (pinfunction "COM_1_4") (pintype "bidirectional"))
    )
    (net (code "14") (name "CODE_A_OUT") (class "Default")
      (node (ref "J4") (pin "4") (pinfunction "4_4") (pintype "bidirectional"))
      (node (ref "K1") (pin "5") (pinfunction "NO_1_5") (pintype "bidirectional"))
    )
    (net (code "15") (name "CODE_B_IN") (class "Default")
      (node (ref "J4") (pin "12") (pinfunction "12_12") (pintype "bidirectional"))
      (node (ref "K1") (pin "9") (pinfunction "COM_2_9") (pintype "bidirectional"))
    )
    (net (code "16") (name "CODE_B_OUT") (class "Default")
      (node (ref "J4") (pin "5") (pinfunction "5_5") (pintype "bidirectional"))
      (node (ref "K1") (pin "10") (pinfunction "NC_2_10") (pintype "bidirectional"))
    )
    (net (code "17") (name "GND") (class "Default")
      (node (ref "-") (pin "TP") (pinfunction "TP_TP") (pintype "input"))
      (node (ref "C1") (pin "1") (pinfunction "1_1") (pintype "bidirectional"))
      (node (ref "C10") (pin "1") (pinfunction "1_1") (pintype "bidirectional"))
      (node (ref "C11") (pin "1") (pinfunction "1_1") (pintype "bidirectional"))
      (node (ref "C12") (pin "1") (pinfunction "1_1") (pintype "bidirectional"))
      (node (ref "C13") (pin "1") (pinfunction "1_1") (pintype "bidirectional"))
      (node (ref "C14") (pin "1") (pinfunction "1_1") (pintype "bidirectional"))
      (node (ref "C15") (pin "1") (pinfunction "1_1") (pintype "bidirectional"))
      (node (ref "C16") (pin "1") (pinfunction "1_1") (pintype "bidirectional"))
      (node (ref "C17") (pin "1") (pinfunction "1_1") (pintype "bidirectional"))
      (node (ref "C18") (pin "1") (pinfunction "1_1") (pintype "bidirectional"))
      (node (ref "C19") (pin "1") (pinfunction "1_1") (pintype "bidirectional"))
      (node (ref "C20") (pin "1") (pinfunction "1_1") (pintype "bidirectional"))
      (node (ref "C21") (pin "1") (pinfunction "1_1") (pintype "bidirectional"))
      (node (ref "C22") (pin "1") (pinfunction "1_1") (pintype "bidirectional"))
      (node (ref "C23") (pin "1") (pinfunction "1_1") (pintype "bidirectional"))
      (node (ref "C24") (pin "1") (pinfunction "1_1") (pintype "bidirectional"))
      (node (ref "C25") (pin "1") (pinfunction "1_1") (pintype "bidirectional"))
      (node (ref "C26") (pin "1") (pinfunction "1_1") (pintype "bidirectional"))
      (node (ref "C27") (pin "1") (pinfunction "1_1") (pintype "bidirectional"))
      (node (ref "C28") (pin "1") (pinfunction "1_1") (pintype "bidirectional"))
      (node (ref "C29") (pin "2") (pinfunction "2_2") (pintype "bidirectional"))
      (node (ref "C3") (pin "1") (pinfunction "1_1") (pintype "bidirectional"))
      (node (ref "C30") (pin "2") (pinfunction "2_2") (pintype "bidirectional"))
      (node (ref "C31") (pin "1") (pinfunction "1_1") (pintype "bidirectional"))
      (node (ref "C32") (pin "1") (pinfunction "1_1") (pintype "bidirectional"))
      (node (ref "C33") (pin "1") (pinfunction "1_1") (pintype "bidirectional"))
      (node (ref "C34") (pin "1") (pinfunction "1_1") (pintype "bidirectional"))
      (node (ref "C35") (pin "2") (pinfunction "2_2") (pintype "bidirectional"))
      (node (ref "C36") (pin "2") (pinfunction "2_2") (pintype "bidirectional"))
      (node (ref "C37") (pin "2") (pinfunction "2_2") (pintype "bidirectional"))
      (node (ref "C39") (pin "1") (pinfunction "1_1") (pintype "bidirectional"))
      (node (ref "C4") (pin "1") (pinfunction "1_1") (pintype "bidirectional"))
      (node (ref "C40") (pin "1") (pinfunction "1_1") (pintype "bidirectional"))
      (node (ref "C43") (pin "2") (pinfunction "2_2") (pintype "bidirectional"))
      (node (ref "C44") (pin "2") (pinfunction "2_2") (pintype "bidirectional"))
      (node (ref "C45") (pin "1") (pinfunction "1_1") (pintype "bidirectional"))
      (node (ref "C46") (pin "1") (pinfunction "1_1") (pintype "bidirectional"))
      (node (ref "C47") (pin "1") (pinfunction "1_1") (pintype "bidirectional"))
      (node (ref "C48") (pin "1") (pinfunction "1_1") (pintype "bidirectional"))
      (node (ref "C49") (pin "1") (pinfunction "1_1") (pintype "bidirectional"))
      (node (ref "C5") (pin "1") (pinfunction "1_1") (pintype "bidirectional"))
      (node (ref "C50") (pin "2") (pinfunction "2_2") (pintype "bidirectional"))
      (node (ref "C52") (pin "2") (pinfunction "2_2") (pintype "bidirectional"))
      (node (ref "C53") (pin "2") (pinfunction "2_2") (pintype "bidirectional"))
      (node (ref "C54") (pin "1") (pinfunction "1_1") (pintype "bidirectional"))
      (node (ref "C55") (pin "2") (pinfunction "2_2") (pintype "bidirectional"))
      (node (ref "C56") (pin "2") (pinfunction "2_2") (pintype "bidirectional"))
      (node (ref "C57") (pin "2") (pinfunction "2_2") (pintype "bidirectional"))
      (node (ref "C58") (pin "1") (pinfunction "1_1") (pintype "bidirectional"))
      (node (ref "C6") (pin "1") (pinfunction "1_1") (pintype "bidirectional"))
      (node (ref "C7") (pin "2") (pinfunction "+_2") (pintype "bidirectional"))
      (node (ref "C8") (pin "1") (pinfunction "1_1") (pintype "bidirectional"))
      (node (ref "C9") (pin "1") (pinfunction "1_1") (pintype "bidirectional"))
      (node (ref "D1") (pin "2") (pinfunction "A_2") (pintype "bidirectional"))
      (node (ref "D13") (pin "1") (pinfunction "K_1") (pintype "bidirectional"))
      (node (ref "D14") (pin "1") (pinfunction "K_1") (pintype "bidirectional"))
      (node (ref "D2") (pin "1") (pinfunction "K_1") (pintype "bidirectional"))
      (node (ref "D3") (pin "1") (pinfunction "K_1") (pintype "bidirectional"))
      (node (ref "D4") (pin "1") (pinfunction "K_1") (pintype "bidirectional"))
      (node (ref "D5") (pin "1") (pinfunction "K_1") (pintype "bidirectional"))
      (node (ref "D6") (pin "1") (pinfunction "K_1") (pintype "bidirectional"))
      (node (ref "D7") (pin "1") (pinfunction "K_1") (pintype "bidirectional"))
      (node (ref "D8") (pin "1") (pinfunction "K_1") (pintype "bidirectional"))
      (node (ref "IC1") (pin "18") (pinfunction "GND_1_18") (pintype "bidirectional"))
      (node (ref "IC1") (pin "35") (pinfunction "GND_2_35") (pintype "bidirectional"))
      (node (ref "IC1") (pin "42") (pinfunction "GND_3_42") (pintype "bidirectional"))
      (node (ref "IC1") (pin "5") (pinfunction "GNDANA_5") (pintype "bidirectional"))
      (node (ref "IC10") (pin "10") (pinfunction "VSS_10") (pintype "bidirectional"))
      (node (ref "IC11") (pin "10") (pinfunction "VSS_10") (pintype "bidirectional"))
      (node (ref "IC12") (pin "2") (pinfunction "2_2") (pintype "bidirectional"))
      (node (ref "IC13") (pin "2") (pinfunction "2_2") (pintype "bidirectional"))
      (node (ref "IC14") (pin "1") (pinfunction "CLKIN_1") (pintype "bidirectional"))
      (node (ref "IC14") (pin "11") (pinfunction "FSYNC_11") (pintype "bidirectional"))
      (node (ref "IC14") (pin "18") (pinfunction "GND_18") (pintype "bidirectional"))
      (node (ref "IC2") (pin "1") (pinfunction "GND_1_1") (pintype "bidirectional"))
      (node (ref "IC2") (pin "14") (pinfunction "GND_4_14") (pintype "bidirectional"))
      (node (ref "IC2") (pin "20") (pinfunction "GND_5_20") (pintype "bidirectional"))
      (node (ref "IC2") (pin "21") (pinfunction "GND_6_21") (pintype "bidirectional"))
      (node (ref "IC2") (pin "22") (pinfunction "GND_7_22") (pintype "bidirectional"))
      (node (ref "IC2") (pin "3") (pinfunction "GND_2_3") (pintype "bidirectional"))
      (node (ref "IC2") (pin "30") (pinfunction "GND_8_30") (pintype "bidirectional"))
      (node (ref "IC2") (pin "32") (pinfunction "GND_9_32") (pintype "bidirectional"))
      (node (ref "IC2") (pin "33") (pinfunction "RSVD_3_33") (pintype "bidirectional"))
      (node (ref "IC2") (pin "43") (pinfunction "GND_10_43") (pintype "bidirectional"))
      (node (ref "IC2") (pin "5") (pinfunction "GND_3_5") (pintype "bidirectional"))
      (node (ref "IC2") (pin "50") (pinfunction "GND_11_50") (pintype "bidirectional"))
      (node (ref "IC2") (pin "54") (pinfunction "GND_12_54") (pintype "bidirectional"))
      (node (ref "IC2") (pin "55") (pinfunction "GND_13_55") (pintype "bidirectional"))
      (node (ref "IC2") (pin "57") (pinfunction "GND_14_57") (pintype "bidirectional"))
      (node (ref "IC2") (pin "58") (pinfunction "GND_15_58") (pintype "bidirectional"))
      (node (ref "IC2") (pin "59") (pinfunction "GND_16_59") (pintype "bidirectional"))
      (node (ref "IC2") (pin "60") (pinfunction "GND_17_60") (pintype "bidirectional"))
      (node (ref "IC2") (pin "61") (pinfunction "GND_18_61") (pintype "bidirectional"))
      (node (ref "IC2") (pin "63") (pinfunction "GND_19_63") (pintype "bidirectional"))
      (node (ref "IC2") (pin "64") (pinfunction "GND_20_64") (pintype "bidirectional"))
      (node (ref "IC2") (pin "65") (pinfunction "GND_21_65") (pintype "bidirectional"))
      (node (ref "IC2") (pin "66") (pinfunction "GND_22_66") (pintype "bidirectional"))
      (node (ref "IC2") (pin "67") (pinfunction "GND_23_67") (pintype "bidirectional"))
      (node (ref "IC2") (pin "68") (pinfunction "GND_24_68") (pintype "bidirectional"))
      (node (ref "IC2") (pin "69") (pinfunction "GND_25_69") (pintype "bidirectional"))
      (node (ref "IC2") (pin "70") (pinfunction "GND_26_70") (pintype "bidirectional"))
      (node (ref "IC2") (pin "71") (pinfunction "GND_27_71") (pintype "bidirectional"))
      (node (ref "IC2") (pin "72") (pinfunction "GND_28_72") (pintype "bidirectional"))
      (node (ref "IC2") (pin "73") (pinfunction "GND_29_73") (pintype "bidirectional"))
      (node (ref "IC2") (pin "74") (pinfunction "GND_30_74") (pintype "bidirectional"))
      (node (ref "IC2") (pin "75") (pinfunction "GND_31_75") (pintype "bidirectional"))
      (node (ref "IC2") (pin "76") (pinfunction "GND_32_76") (pintype "bidirectional"))
      (node (ref "IC2") (pin "77") (pinfunction "GND_33_77") (pintype "bidirectional"))
      (node (ref "IC2") (pin "78") (pinfunction "GND_34_78") (pintype "bidirectional"))
      (node (ref "IC2") (pin "79") (pinfunction "GND_35_79") (pintype "bidirectional"))
      (node (ref "IC2") (pin "80") (pinfunction "GND_36_80") (pintype "bidirectional"))
      (node (ref "IC2") (pin "81") (pinfunction "GND_37_81") (pintype "bidirectional"))
      (node (ref "IC2") (pin "82") (pinfunction "GND_38_82") (pintype "bidirectional"))
      (node (ref "IC2") (pin "83") (pinfunction "GND_39_83") (pintype "bidirectional"))
      (node (ref "IC2") (pin "84") (pinfunction "GND_40_84") (pintype "bidirectional"))
      (node (ref "IC2") (pin "85") (pinfunction "GND_41_85") (pintype "bidirectional"))
      (node (ref "IC2") (pin "86") (pinfunction "GND_42_86") (pintype "bidirectional"))
      (node (ref "IC2") (pin "87") (pinfunction "GND_43_87") (pintype "bidirectional"))
      (node (ref "IC2") (pin "88") (pinfunction "GND_44_88") (pintype "bidirectional"))
      (node (ref "IC2") (pin "89") (pinfunction "GND_45_89") (pintype "bidirectional"))
      (node (ref "IC2") (pin "90") (pinfunction "GND_46_90") (pintype "bidirectional"))
      (node (ref "IC2") (pin "91") (pinfunction "GND_47_91") (pintype "bidirectional"))
      (node (ref "IC2") (pin "92") (pinfunction "GND_48_92") (pintype "bidirectional"))
      (node (ref "IC2") (pin "93") (pinfunction "GND_49_93") (pintype "bidirectional"))
      (node (ref "IC2") (pin "94") (pinfunction "GND_50_94") (pintype "bidirectional"))
      (node (ref "IC2") (pin "95") (pinfunction "GND_51_95") (pintype "bidirectional"))
      (node (ref "IC2") (pin "96") (pinfunction "GND_52_96") (pintype "bidirectional"))
      (node (ref "IC3") (pin "2") (pinfunction "GND_2") (pintype "bidirectional"))
      (node (ref "IC4") (pin "7") (pinfunction "GND_7") (pintype "power_in"))
      (node (ref "IC5") (pin "3") (pinfunction "GND_3") (pintype "bidirectional"))
      (node (ref "IC6") (pin "4") (pinfunction "GND_4") (pintype "bidirectional"))
      (node (ref "IC7") (pin "6") (pinfunction "GND_6") (pintype "power_in"))
      (node (ref "IC8") (pin "4") (pinfunction "GND_4") (pintype "bidirectional"))
      (node (ref "IC8") (pin "9") (pinfunction "EP_9") (pintype "bidirectional"))
      (node (ref "IC9") (pin "2") (pinfunction "GNDA_2") (pintype "bidirectional"))
      (node (ref "IC9") (pin "5") (pinfunction "GNDB_5") (pintype "bidirectional"))
      (node (ref "J1") (pin "10") (pinfunction "HD1_10") (pintype "bidirectional"))
      (node (ref "J1") (pin "11") (pinfunction "HD4_11") (pintype "bidirectional"))
      (node (ref "J1") (pin "4") (pinfunction "C5_4") (pintype "bidirectional"))
      (node (ref "J1") (pin "7") (pinfunction "HD3_7") (pintype "bidirectional"))
      (node (ref "J1") (pin "9") (pinfunction "HD2,_DSW1_9") (pintype "bidirectional"))
      (node (ref "J2") (pin "6") (pinfunction "VSS_6") (pintype "bidirectional"))
      (node (ref "J3") (pin "1") (pinfunction "1_1") (pintype "bidirectional"))
      (node (ref "J3") (pin "2") (pinfunction "2_2") (pintype "bidirectional"))
      (node (ref "J3") (pin "3") (pinfunction "3_3") (pintype "bidirectional"))
      (node (ref "J3") (pin "4") (pinfunction "4_4") (pintype "bidirectional"))
      (node (ref "J4") (pin "1") (pinfunction "1_1") (pintype "bidirectional"))
      (node (ref "J4") (pin "6") (pinfunction "6_6") (pintype "bidirectional"))
      (node (ref "J5") (pin "5") (pinfunction "5_5") (pintype "passive"))
      (node (ref "J6") (pin "1") (pinfunction "1_1") (pintype "bidirectional"))
      (node (ref "J6") (pin "2") (pinfunction "2_2") (pintype "bidirectional"))
      (node (ref "J6") (pin "3") (pinfunction "3_3") (pintype "bidirectional"))
      (node (ref "J6") (pin "4") (pinfunction "4_4") (pintype "bidirectional"))
      (node (ref "J7") (pin "3") (pinfunction "3_3") (pintype "bidirectional"))
      (node (ref "J7") (pin "5") (pinfunction "5_5") (pintype "bidirectional"))
      (node (ref "J7") (pin "9") (pinfunction "9_9") (pintype "bidirectional"))
      (node (ref "L4") (pin "1") (pinfunction "1_1") (pintype "bidirectional"))
      (node (ref "LED1") (pin "1") (pinfunction "CATHODE_1") (pintype "bidirectional"))
      (node (ref "Q1") (pin "1") (pinfunction "S1_1") (pintype "bidirectional"))
      (node (ref "Q1") (pin "4") (pinfunction "S2_4") (pintype "bidirectional"))
      (node (ref "Q2") (pin "2") (pinfunction "2_2") (pintype "bidirectional"))
      (node (ref "Q3") (pin "2") (pinfunction "2_2") (pintype "bidirectional"))
      (node (ref "Q4") (pin "1") (pinfunction "S1_1") (pintype "bidirectional"))
      (node (ref "Q4") (pin "4") (pinfunction "S2_4") (pintype "bidirectional"))
      (node (ref "Q5") (pin "3") (pinfunction "S_3") (pintype "power_in"))
      (node (ref "Q6") (pin "3") (pinfunction "S_3") (pintype "power_in"))
      (node (ref "Q8") (pin "2") (pinfunction "E_2") (pintype "bidirectional"))
      (node (ref "R10") (pin "1") (pinfunction "1_1") (pintype "bidirectional"))
      (node (ref "R11") (pin "1") (pinfunction "1_1") (pintype "bidirectional"))
      (node (ref "R12") (pin "1") (pinfunction "1_1") (pintype "bidirectional"))
      (node (ref "R14") (pin "2") (pinfunction "2_2") (pintype "bidirectional"))
      (node (ref "R18") (pin "1") (pinfunction "1_1") (pintype "bidirectional"))
      (node (ref "R19") (pin "1") (pinfunction "1_1") (pintype "bidirectional"))
      (node (ref "R2") (pin "1") (pinfunction "1_1") (pintype "bidirectional"))
      (node (ref "R33") (pin "1") (pinfunction "1_1") (pintype "bidirectional"))
      (node (ref "R34") (pin "2") (pinfunction "2_2") (pintype "bidirectional"))
      (node (ref "R36") (pin "1") (pinfunction "1_1") (pintype "bidirectional"))
      (node (ref "R48") (pin "2") (pinfunction "2_2") (pintype "bidirectional"))
      (node (ref "R49") (pin "2") (pinfunction "2_2") (pintype "bidirectional"))
      (node (ref "R51") (pin "2") (pinfunction "2_2") (pintype "bidirectional"))
      (node (ref "R6") (pin "1") (pinfunction "1_1") (pintype "bidirectional"))
      (node (ref "R7") (pin "1") (pinfunction "1_1") (pintype "bidirectional"))
      (node (ref "S1") (pin "1") (pinfunction "1_1") (pintype "bidirectional"))
      (node (ref "S1") (pin "3") (pinfunction "CHASSIS_PCB_PAD_1_3") (pintype "bidirectional"))
      (node (ref "S1") (pin "4") (pinfunction "CHASSIS_PCB_PAD_2_4") (pintype "bidirectional"))
      (node (ref "U$1") (pin "10_GND") (pinfunction "10_GND_10_GND") (pintype "power_in"))
      (node (ref "U$1") (pin "12_GND") (pinfunction "12_GND_12_GND") (pintype "power_in"))
      (node (ref "U$1") (pin "1_GND") (pinfunction "1_GND_1_GND") (pintype "power_in"))
      (node (ref "U1") (pin "1") (pinfunction "DIR2_1") (pintype "bidirectional"))
      (node (ref "U1") (pin "2") (pinfunction "~{OE2}_2") (pintype "bidirectional"))
      (node (ref "U1") (pin "3") (pinfunction "GND_3") (pintype "power_in"))
    )
    (net (code "18") (name "GPS_ANT") (class "Default")
      (node (ref "J3") (pin "5") (pinfunction "5_5") (pintype "bidirectional"))
      (node (ref "L3") (pin "2") (pinfunction "2_2") (pintype "bidirectional"))
      (node (ref "U$1") (pin "11_RF_IN") (pinfunction "11_RF_IN_11_RF_IN") (pintype "bidirectional"))
    )
    (net (code "19") (name "GPS_BCKP") (class "Default")
      (node (ref "R5") (pin "1") (pinfunction "1_1") (pintype "bidirectional"))
      (node (ref "U$1") (pin "6_V_BCKP") (pinfunction "6_V_BCKP_6_V_BCKP") (pintype "bidirectional"))
    )
    (net (code "20") (name "GRST") (class "Default")
      (node (ref "Q2") (pin "3") (pinfunction "3_3") (pintype "bidirectional"))
      (node (ref "U$1") (pin "9_RESET_N") (pinfunction "9_V_RESET_N_9_RESET_N") (pintype "power_in"))
    )
    (net (code "21") (name "G_SCL") (class "Default")
      (node (ref "R38") (pin "2") (pinfunction "2_2") (pintype "passive"))
      (node (ref "U$1") (pin "17_SCL") (pinfunction "17_SCL_17_SCL") (pintype "bidirectional"))
    )
    (net (code "22") (name "G_SDA") (class "Default")
      (node (ref "R37") (pin "2") (pinfunction "2_2") (pintype "passive"))
      (node (ref "U$1") (pin "16_SDA") (pinfunction "16_SDA_16_SDA") (pintype "bidirectional"))
    )
    (net (code "23") (name "LOCK_OUT") (class "Default")
      (node (ref "J4") (pin "14") (pinfunction "14_14") (pintype "bidirectional"))
      (node (ref "R20") (pin "2") (pinfunction "2_2") (pintype "bidirectional"))
    )
    (net (code "24") (name "MCTS") (class "Default")
      (node (ref "IC2") (pin "11") (pinfunction "CTS_11") (pintype "bidirectional"))
      (node (ref "MCTS") (pin "TP") (pinfunction "TP_TP") (pintype "input"))
    )
    (net (code "25") (name "MDCD") (class "Default")
      (node (ref "IC2") (pin "8") (pinfunction "DCD_8") (pintype "bidirectional"))
      (node (ref "MDCD") (pin "TP") (pinfunction "TP_TP") (pintype "input"))
    )
    (net (code "26") (name "MDTR") (class "Default")
      (node (ref "IC2") (pin "9") (pinfunction "DTR_9") (pintype "bidirectional"))
      (node (ref "R14") (pin "1") (pinfunction "1_1") (pintype "bidirectional"))
    )
    (net (code "27") (name "MRI") (class "Default")
      (node (ref "IC2") (pin "7") (pinfunction "RI_7") (pintype "bidirectional"))
    )
    (net (code "28") (name "MRST") (class "Default")
      (node (ref "IC2") (pin "18") (pinfunction "RESET_N_18") (pintype "bidirectional"))
      (node (ref "MRST") (pin "TP") (pinfunction "TP_TP") (pintype "input"))
      (node (ref "Q4") (pin "3") (pinfunction "D2_3") (pintype "bidirectional"))
    )
    (net (code "29") (name "MRTS") (class "Default")
      (node (ref "IC2") (pin "10") (pinfunction "RTS_10") (pintype "bidirectional"))
      (node (ref "MRTS") (pin "TP") (pinfunction "TP_TP") (pintype "input"))
      (node (ref "R34") (pin "1") (pinfunction "1_1") (pintype "bidirectional"))
    )
    (net (code "30") (name "MRX") (class "Default")
      (node (ref "IC2") (pin "13") (pinfunction "RXD_13") (pintype "bidirectional"))
      (node (ref "TP_MRX") (pin "TP") (pinfunction "TP_TP") (pintype "input"))
      (node (ref "U1") (pin "4") (pinfunction "B2_4") (pintype "bidirectional"))
    )
    (net (code "31") (name "MTX") (class "Default")
      (node (ref "IC2") (pin "12") (pinfunction "TXD_12") (pintype "bidirectional"))
      (node (ref "TP_MTX") (pin "TP") (pinfunction "TP_TP") (pintype "input"))
      (node (ref "U1") (pin "5") (pinfunction "B1_5") (pintype "bidirectional"))
    )
    (net (code "32") (name "M_ANT_OUT") (class "Default")
      (node (ref "C42") (pin "2") (pinfunction "2_2") (pintype "bidirectional"))
      (node (ref "J6") (pin "5") (pinfunction "5_5") (pintype "bidirectional"))
    )
    (net (code "33") (name "M_SCL") (class "Default")
      (node (ref "IC2") (pin "27") (pinfunction "SCL_27") (pintype "bidirectional"))
      (node (ref "R38") (pin "1") (pinfunction "1_1") (pintype "passive"))
    )
    (net (code "34") (name "M_SDA") (class "Default")
      (node (ref "IC2") (pin "26") (pinfunction "SDA_26") (pintype "bidirectional"))
      (node (ref "R37") (pin "1") (pinfunction "1_1") (pintype "passive"))
    )
    (net (code "35") (name "M_USB_N") (class "Default")
      (node (ref "IC2") (pin "28") (pinfunction "USB_D-_28") (pintype "bidirectional"))
      (node (ref "MUSBN") (pin "TP") (pinfunction "TP_TP") (pintype "input"))
    )
    (net (code "36") (name "M_USB_P") (class "Default")
      (node (ref "IC2") (pin "29") (pinfunction "USB_D+_29") (pintype "bidirectional"))
      (node (ref "MUSBP") (pin "TP") (pinfunction "TP_TP") (pintype "input"))
    )
    (net (code "37") (name "M_VUSB") (class "Default")
      (node (ref "IC2") (pin "17") (pinfunction "VUSB_DET_17") (pintype "bidirectional"))
      (node (ref "MVUSB") (pin "TP") (pinfunction "TP_TP") (pintype "input"))
    )
    (net (code "38") (name "NET_STAT") (class "Default")
      (node (ref "IC2") (pin "16") (pinfunction "GPIO1_16") (pintype "bidirectional"))
      (node (ref "R50") (pin "1") (pinfunction "1_1") (pintype "bidirectional"))
    )
    (net (code "39") (name "Net-(C4-Pad2)") (class "Default")
      (node (ref "C4") (pin "2") (pinfunction "2_2") (pintype "bidirectional"))
      (node (ref "R3") (pin "1") (pinfunction "1_1") (pintype "bidirectional"))
    )
    (net (code "40") (name "Net-(C7--)") (class "Default")
      (node (ref "C7") (pin "1") (pinfunction "-_1") (pintype "bidirectional"))
      (node (ref "D9") (pin "1") (pinfunction "K_1") (pintype "bidirectional"))
      (node (ref "R5") (pin "2") (pinfunction "2_2") (pintype "bidirectional"))
    )
    (net (code "41") (name "Net-(C40-Pad2)") (class "Default")
      (node (ref "C40") (pin "2") (pinfunction "2_2") (pintype "bidirectional"))
      (node (ref "L3") (pin "1") (pinfunction "1_1") (pintype "bidirectional"))
      (node (ref "R13") (pin "1") (pinfunction "1_1") (pintype "bidirectional"))
    )
    (net (code "42") (name "Net-(C41-Pad2)") (class "Default")
      (node (ref "C41") (pin "2") (pinfunction "2_2") (pintype "bidirectional"))
      (node (ref "C42") (pin "1") (pinfunction "1_1") (pintype "bidirectional"))
      (node (ref "L4") (pin "2") (pinfunction "2_2") (pintype "bidirectional"))
    )
    (net (code "43") (name "Net-(C43-Pad1)") (class "Default")
      (node (ref "C43") (pin "1") (pinfunction "1_1") (pintype "bidirectional"))
      (node (ref "D12") (pin "1") (pinfunction "1_1") (pintype "passive"))
      (node (ref "J5") (pin "10") (pinfunction "SH_10") (pintype "passive"))
      (node (ref "J5") (pin "11") (pinfunction "SH_11") (pintype "passive"))
      (node (ref "J5") (pin "6") (pinfunction "SH_6") (pintype "passive"))
      (node (ref "J5") (pin "7") (pinfunction "SH_7") (pintype "passive"))
      (node (ref "J5") (pin "8") (pinfunction "SH_8") (pintype "passive"))
      (node (ref "J5") (pin "9") (pinfunction "SH_9") (pintype "passive"))
      (node (ref "R33") (pin "2") (pinfunction "2_2") (pintype "bidirectional"))
    )
    (net (code "44") (name "Net-(D1-K)") (class "Default")
      (node (ref "C2") (pin "1") (pinfunction "1_1") (pintype "bidirectional"))
      (node (ref "D1") (pin "1") (pinfunction "K_1") (pintype "bidirectional"))
      (node (ref "IC4") (pin "8") (pinfunction "PH_8") (pintype "bidirectional"))
      (node (ref "L1") (pin "1") (pinfunction "1_1") (pintype "bidirectional"))
    )
    (net (code "45") (name "Net-(D9-A)") (class "Default")
      (node (ref "D9") (pin "2") (pinfunction "A_2") (pintype "bidirectional"))
      (node (ref "R4") (pin "1") (pinfunction "1_1") (pintype "bidirectional"))
    )
    (net (code "46") (name "Net-(D10-A)") (class "Default")
      (node (ref "D10") (pin "2") (pinfunction "A_2") (pintype "bidirectional"))
      (node (ref "K1") (pin "12") (pinfunction "SET_COIL_-_12") (pintype "bidirectional"))
      (node (ref "Q1") (pin "6") (pinfunction "D1_6") (pintype "bidirectional"))
    )
    (net (code "47") (name "Net-(D11-A)") (class "Default")
      (node (ref "D11") (pin "2") (pinfunction "A_2") (pintype "bidirectional"))
      (node (ref "K1") (pin "7") (pinfunction "RESET_COIL_-_7") (pintype "bidirectional"))
      (node (ref "Q1") (pin "3") (pinfunction "D2_3") (pintype "bidirectional"))
    )
    (net (code "48") (name "Net-(IC1-VDDANA)") (class "Default")
      (node (ref "C20") (pin "2") (pinfunction "2_2") (pintype "bidirectional"))
      (node (ref "C21") (pin "2") (pinfunction "2_2") (pintype "bidirectional"))
      (node (ref "FB1") (pin "2") (pinfunction "2_2") (pintype "bidirectional"))
      (node (ref "IC1") (pin "6") (pinfunction "VDDANA_6") (pintype "bidirectional"))
    )
    (net (code "49") (name "Net-(IC1-VDDCORE)") (class "Default")
      (node (ref "C29") (pin "1") (pinfunction "1_1") (pintype "bidirectional"))
      (node (ref "IC1") (pin "43") (pinfunction "VDDCORE_43") (pintype "bidirectional"))
    )
    (net (code "50") (name "Net-(IC2-ANT)") (class "Default")
      (node (ref "C41") (pin "1") (pinfunction "1_1") (pintype "bidirectional"))
      (node (ref "IC2") (pin "56") (pinfunction "ANT_56") (pintype "bidirectional"))
    )
    (net (code "51") (name "Net-(IC4-BOOT)") (class "Default")
      (node (ref "C2") (pin "2") (pinfunction "2_2") (pintype "bidirectional"))
      (node (ref "IC4") (pin "1") (pinfunction "BOOT_1") (pintype "bidirectional"))
    )
    (net (code "52") (name "Net-(IC4-COMP)") (class "Default")
      (node (ref "C3") (pin "2") (pinfunction "2_2") (pintype "bidirectional"))
      (node (ref "IC4") (pin "6") (pinfunction "COMP_6") (pintype "output"))
      (node (ref "R3") (pin "2") (pinfunction "2_2") (pintype "bidirectional"))
    )
    (net (code "53") (name "Net-(IC4-EN)") (class "Default")
      (node (ref "IC4") (pin "3") (pinfunction "EN_3") (pintype "bidirectional"))
      (node (ref "R7") (pin "2") (pinfunction "2_2") (pintype "bidirectional"))
      (node (ref "R8") (pin "1") (pinfunction "1_1") (pintype "bidirectional"))
    )
    (net (code "54") (name "Net-(IC4-SS)") (class "Default")
      (node (ref "C5") (pin "2") (pinfunction "2_2") (pintype "bidirectional"))
      (node (ref "IC4") (pin "4") (pinfunction "SS_4") (pintype "output"))
    )
    (net (code "55") (name "Net-(IC4-VSENSE)") (class "Default")
      (node (ref "IC4") (pin "5") (pinfunction "VSENSE_5") (pintype "bidirectional"))
      (node (ref "R1") (pin "1") (pinfunction "1_1") (pintype "bidirectional"))
      (node (ref "R2") (pin "2") (pinfunction "2_2") (pintype "bidirectional"))
    )
    (net (code "56") (name "Net-(IC5-BST)") (class "Default")
      (node (ref "C38") (pin "2") (pinfunction "2_2") (pintype "bidirectional"))
      (node (ref "IC5") (pin "4") (pinfunction "BST_4") (pintype "bidirectional"))
    )
    (net (code "57") (name "Net-(IC5-FB)") (class "Default")
      (node (ref "IC5") (pin "6") (pinfunction "FB_6") (pintype "bidirectional"))
      (node (ref "R10") (pin "2") (pinfunction "2_2") (pintype "bidirectional"))
      (node (ref "R9") (pin "1") (pinfunction "1_1") (pintype "bidirectional"))
    )
    (net (code "58") (name "Net-(IC5-SW)") (class "Default")
      (node (ref "C38") (pin "1") (pinfunction "1_1") (pintype "bidirectional"))
      (node (ref "IC5") (pin "2") (pinfunction "SW_2") (pintype "bidirectional"))
      (node (ref "L2") (pin "1") (pinfunction "1_1") (pintype "bidirectional"))
    )
    (net (code "59") (name "Net-(IC10-OSC1)") (class "Default")
      (node (ref "IC10") (pin "9") (pinfunction "OSC1_9") (pintype "bidirectional"))
      (node (ref "IC12") (pin "1") (pinfunction "1_1") (pintype "bidirectional"))
    )
    (net (code "60") (name "Net-(IC10-OSC2)") (class "Default")
      (node (ref "IC10") (pin "8") (pinfunction "OSC2_8") (pintype "bidirectional"))
      (node (ref "IC12") (pin "3") (pinfunction "3_3") (pintype "bidirectional"))
    )
    (net (code "61") (name "Net-(IC10-~{RESET})") (class "Default")
      (node (ref "IC10") (pin "19") (pinfunction "~{RESET}_19") (pintype "bidirectional"))
      (node (ref "R27") (pin "1") (pinfunction "1_1") (pintype "bidirectional"))
    )
    (net (code "62") (name "Net-(IC10-~{RX0BF})") (class "Default")
      (node (ref "IC10") (pin "12") (pinfunction "~{RX0BF}_12") (pintype "bidirectional"))
      (node (ref "R45") (pin "1") (pinfunction "1_1") (pintype "bidirectional"))
    )
    (net (code "63") (name "Net-(IC11-OSC1)") (class "Default")
      (node (ref "IC11") (pin "9") (pinfunction "OSC1_9") (pintype "bidirectional"))
      (node (ref "IC13") (pin "1") (pinfunction "1_1") (pintype "bidirectional"))
    )
    (net (code "64") (name "Net-(IC11-OSC2)") (class "Default")
      (node (ref "IC11") (pin "8") (pinfunction "OSC2_8") (pintype "bidirectional"))
      (node (ref "IC13") (pin "3") (pinfunction "3_3") (pintype "bidirectional"))
    )
    (net (code "65") (name "Net-(IC11-~{RESET})") (class "Default")
      (node (ref "IC11") (pin "19") (pinfunction "~{RESET}_19") (pintype "bidirectional"))
      (node (ref "R25") (pin "1") (pinfunction "1_1") (pintype "bidirectional"))
    )
    (net (code "66") (name "Net-(IC11-~{RX0BF})") (class "Default")
      (node (ref "IC11") (pin "12") (pinfunction "~{RX0BF}_12") (pintype "bidirectional"))
      (node (ref "R44") (pin "1") (pinfunction "1_1") (pintype "bidirectional"))
    )
    (net (code "67") (name "Net-(IC14-AD0)") (class "Default")
      (node (ref "IC14") (pin "9") (pinfunction "AD0_9") (pintype "bidirectional"))
      (node (ref "R48") (pin "1") (pinfunction "1_1") (pintype "bidirectional"))
    )
    (net (code "68") (name "Net-(IC14-CPOUT)") (class "Default")
      (node (ref "C57") (pin "1") (pinfunction "1_1") (pintype "bidirectional"))
      (node (ref "IC14") (pin "20") (pinfunction "CPOUT_20") (pintype "bidirectional"))
    )
    (net (code "69") (name "Net-(IC14-REGOUT)") (class "Default")
      (node (ref "C55") (pin "1") (pinfunction "1_1") (pintype "bidirectional"))
      (node (ref "IC14") (pin "10") (pinfunction "REGOUT_10") (pintype "bidirectional"))
    )
    (net (code "70") (name "Net-(J7-Pad10)") (class "Default")
      (node (ref "J7") (pin "10") (pinfunction "10_10") (pintype "bidirectional"))
      (node (ref "R39") (pin "1") (pinfunction "1_1") (pintype "bidirectional"))
    )
    (net (code "71") (name "Net-(LED1-ANODE)") (class "Default")
      (node (ref "LED1") (pin "2") (pinfunction "ANODE_2") (pintype "bidirectional"))
      (node (ref "R41") (pin "1") (pinfunction "1_1") (pintype "bidirectional"))
    )
    (net (code "72") (name "Net-(LED3-A)") (class "Default")
      (node (ref "LED3") (pin "2") (pinfunction "A_2") (pintype "bidirectional"))
      (node (ref "R15") (pin "1") (pinfunction "1_1") (pintype "bidirectional"))
    )
    (net (code "73") (name "Net-(LED3-K)") (class "Default")
      (node (ref "LED3") (pin "1") (pinfunction "K_1") (pintype "bidirectional"))
      (node (ref "Q8") (pin "3") (pinfunction "C_3") (pintype "bidirectional"))
    )
    (net (code "74") (name "Net-(LED4-A)") (class "Default")
      (node (ref "LED4") (pin "2") (pinfunction "A_2") (pintype "bidirectional"))
      (node (ref "R32") (pin "1") (pinfunction "1_1") (pintype "bidirectional"))
    )
    (net (code "75") (name "Net-(LED4-K)") (class "Default")
      (node (ref "LED4") (pin "1") (pinfunction "K_1") (pintype "bidirectional"))
      (node (ref "U$1") (pin "4_TIMEPULSE") (pinfunction "4_TIMEPULSE_4_TIMEPULSE") (pintype "bidirectional"))
    )
    (net (code "76") (name "Net-(Q5-D_1)") (class "Default")
      (node (ref "Q5") (pin "2") (pinfunction "D_1_2") (pintype "power_in"))
      (node (ref "Q5") (pin "4") (pinfunction "D_2_4") (pintype "power_in"))
      (node (ref "R20") (pin "1") (pinfunction "1_1") (pintype "bidirectional"))
    )
    (net (code "77") (name "Net-(Q6-D_1)") (class "Default")
      (node (ref "Q6") (pin "2") (pinfunction "D_1_2") (pintype "power_in"))
      (node (ref "Q6") (pin "4") (pinfunction "D_2_4") (pintype "power_in"))
      (node (ref "R21") (pin "1") (pinfunction "1_1") (pintype "bidirectional"))
    )
    (net (code "78") (name "Net-(Q7-D)") (class "Default")
      (node (ref "F2") (pin "1") (pinfunction "1_1") (pintype "bidirectional"))
      (node (ref "Q7") (pin "3") (pinfunction "D_3") (pintype "bidirectional"))
    )
    (net (code "79") (name "Net-(Q7-G)") (class "Default")
      (node (ref "Q7") (pin "1") (pinfunction "G_1") (pintype "bidirectional"))
      (node (ref "R49") (pin "1") (pinfunction "1_1") (pintype "bidirectional"))
      (node (ref "Z1") (pin "1") (pinfunction "A_1") (pintype "bidirectional"))
    )
    (net (code "80") (name "Net-(Q8-B)") (class "Default")
      (node (ref "Q8") (pin "1") (pinfunction "B_1") (pintype "bidirectional"))
      (node (ref "R50") (pin "2") (pinfunction "2_2") (pintype "bidirectional"))
      (node (ref "R51") (pin "1") (pinfunction "1_1") (pintype "bidirectional"))
    )
    (net (code "81") (name "Net-(R13-Pad2)") (class "Default")
      (node (ref "R13") (pin "2") (pinfunction "2_2") (pintype "bidirectional"))
      (node (ref "U$1") (pin "14_VCC_RF") (pinfunction "14_VCC_RF_14_VCC_RF") (pintype "bidirectional"))
    )
    (net (code "82") (name "PA00_XIN32") (class "Default")
      (node (ref "C16") (pin "2") (pinfunction "2_2") (pintype "bidirectional"))
      (node (ref "IC1") (pin "1") (pinfunction "PA00_1") (pintype "bidirectional"))
      (node (ref "Y1") (pin "2") (pinfunction "2_2") (pintype "bidirectional"))
    )
    (net (code "83") (name "PA01_XOUT32") (class "Default")
      (node (ref "C17") (pin "2") (pinfunction "2_2") (pintype "bidirectional"))
      (node (ref "IC1") (pin "2") (pinfunction "PA01_2") (pintype "bidirectional"))
      (node (ref "Y1") (pin "1") (pinfunction "1_1") (pintype "bidirectional"))
    )
    (net (code "84") (name "PA02_C1_SS") (class "Default")
      (node (ref "IC1") (pin "3") (pinfunction "PA02_3") (pintype "bidirectional"))
      (node (ref "IC11") (pin "18") (pinfunction "~{CS}_18") (pintype "bidirectional"))
      (node (ref "R24") (pin "1") (pinfunction "1_1") (pintype "bidirectional"))
    )
    (net (code "85") (name "PA03_VREFA") (class "Default")
      (node (ref "IC1") (pin "4") (pinfunction "PA03_4") (pintype "bidirectional"))
    )
    (net (code "86") (name "PA04_BT_RST") (class "Default")
      (node (ref "BT_RST") (pin "TP") (pinfunction "TP_TP") (pintype "input"))
      (node (ref "IC1") (pin "9") (pinfunction "PA04_9") (pintype "bidirectional"))
      (node (ref "IC7") (pin "11") (pinfunction "BT_RESET_11") (pintype "input"))
    )
    (net (code "87") (name "PA05_AIN5_LOCK") (class "Default")
      (node (ref "IC1") (pin "10") (pinfunction "PA05_10") (pintype "bidirectional"))
      (node (ref "Q5") (pin "1") (pinfunction "IN_1") (pintype "input"))
    )
    (net (code "88") (name "PA06_AIN6_UNLOCK") (class "Default")
      (node (ref "IC1") (pin "11") (pinfunction "PA06_11") (pintype "bidirectional"))
      (node (ref "Q6") (pin "1") (pinfunction "IN_1") (pintype "input"))
    )
    (net (code "89") (name "PA07_C1_INT") (class "Default")
      (node (ref "IC1") (pin "12") (pinfunction "PA07_12") (pintype "bidirectional"))
      (node (ref "IC11") (pin "13") (pinfunction "~{INT}_13") (pintype "bidirectional"))
      (node (ref "R29") (pin "1") (pinfunction "1_1") (pintype "bidirectional"))
    )
    (net (code "90") (name "PA08_S0_I2C_SDA") (class "Default")
      (node (ref "IC1") (pin "13") (pinfunction "PA08_13") (pintype "bidirectional"))
      (node (ref "IC14") (pin "24") (pinfunction "SDA_24") (pintype "bidirectional"))
      (node (ref "IC6") (pin "5") (pinfunction "SDA_5") (pintype "bidirectional"))
      (node (ref "R43") (pin "1") (pinfunction "1_1") (pintype "bidirectional"))
      (node (ref "R47") (pin "1") (pinfunction "1_1") (pintype "bidirectional"))
      (node (ref "TP_SDA") (pin "TP") (pinfunction "TP_TP") (pintype "input"))
    )
    (net (code "91") (name "PA09_S0_I2C_SCL") (class "Default")
      (node (ref "IC1") (pin "14") (pinfunction "PA09_14") (pintype "bidirectional"))
      (node (ref "IC14") (pin "23") (pinfunction "SCL_23") (pintype "bidirectional"))
      (node (ref "IC6") (pin "6") (pinfunction "SCL_6") (pintype "bidirectional"))
      (node (ref "R42") (pin "1") (pinfunction "1_1") (pintype "bidirectional"))
      (node (ref "R46") (pin "1") (pinfunction "1_1") (pintype "bidirectional"))
      (node (ref "TP_SCL") (pin "TP") (pinfunction "TP_TP") (pintype "input"))
    )
    (net (code "92") (name "PA10_TCC0-W2_VIN") (class "Default")
      (node (ref "IC1") (pin "15") (pinfunction "PA10_15") (pintype "bidirectional"))
      (node (ref "R35") (pin "1") (pinfunction "1_1") (pintype "bidirectional"))
      (node (ref "R36") (pin "2") (pinfunction "2_2") (pintype "bidirectional"))
    )
    (net (code "93") (name "PA11_C0_SS") (class "Default")
      (node (ref "IC1") (pin "16") (pinfunction "PA11_16") (pintype "bidirectional"))
      (node (ref "IC10") (pin "18") (pinfunction "~{CS}_18") (pintype "bidirectional"))
      (node (ref "R26") (pin "1") (pinfunction "1_1") (pintype "bidirectional"))
    )
    (net (code "94") (name "PA12_S2_TX") (class "Default")
      (node (ref "IC1") (pin "21") (pinfunction "PA12_21") (pintype "bidirectional"))
      (node (ref "U1") (pin "8") (pinfunction "A1_8") (pintype "bidirectional"))
    )
    (net (code "95") (name "PA13_S2_RX") (class "Default")
      (node (ref "IC1") (pin "22") (pinfunction "PA13_22") (pintype "bidirectional"))
      (node (ref "U1") (pin "9") (pinfunction "A2_9") (pintype "bidirectional"))
    )
    (net (code "96") (name "PA14_IMM_OFF") (class "Default")
      (node (ref "IC1") (pin "23") (pinfunction "PA14_23") (pintype "bidirectional"))
      (node (ref "Q1") (pin "5") (pinfunction "G2_5") (pintype "input"))
      (node (ref "R12") (pin "2") (pinfunction "2_2") (pintype "bidirectional"))
    )
    (net (code "97") (name "PA15_IMM_ON") (class "Default")
      (node (ref "IC1") (pin "24") (pinfunction "PA15_24") (pintype "bidirectional"))
      (node (ref "Q1") (pin "2") (pinfunction "G1_2") (pintype "input"))
      (node (ref "R11") (pin "2") (pinfunction "2_2") (pintype "bidirectional"))
    )
    (net (code "98") (name "PA16_S1_MOSI") (class "Default")
      (node (ref "IC1") (pin "25") (pinfunction "PA16_25") (pintype "bidirectional"))
      (node (ref "IC10") (pin "16") (pinfunction "SI_16") (pintype "bidirectional"))
      (node (ref "IC11") (pin "16") (pinfunction "SI_16") (pintype "bidirectional"))
      (node (ref "IC8") (pin "5") (pinfunction "DI_(IO0)_5") (pintype "bidirectional"))
      (node (ref "J2") (pin "3") (pinfunction "CMD_3") (pintype "bidirectional"))
      (node (ref "SPI1_MOSI") (pin "TP") (pinfunction "TP_TP") (pintype "input"))
    )
    (net (code "99") (name "PA17_S1_SCK") (class "Default")
      (node (ref "IC1") (pin "26") (pinfunction "PA17_26") (pintype "bidirectional"))
      (node (ref "IC10") (pin "14") (pinfunction "SCK_14") (pintype "bidirectional"))
      (node (ref "IC11") (pin "14") (pinfunction "SCK_14") (pintype "bidirectional"))
      (node (ref "IC8") (pin "6") (pinfunction "CLK_6") (pintype "bidirectional"))
      (node (ref "J2") (pin "5") (pinfunction "CLK_5") (pintype "bidirectional"))
      (node (ref "SPI1_SCK") (pin "TP") (pinfunction "TP_TP") (pintype "input"))
    )
    (net (code "100") (name "PA18_OTG") (class "Default")
      (node (ref "IC1") (pin "27") (pinfunction "PA18_27") (pintype "bidirectional"))
      (node (ref "J5") (pin "4") (pinfunction "4_4") (pintype "passive"))
      (node (ref "USBO") (pin "TP") (pinfunction "TP_TP") (pintype "input"))
    )
    (net (code "101") (name "PA19_S1_MISO") (class "Default")
      (node (ref "IC1") (pin "28") (pinfunction "PA19_28") (pintype "bidirectional"))
      (node (ref "IC10") (pin "17") (pinfunction "SO_17") (pintype "bidirectional"))
      (node (ref "IC11") (pin "17") (pinfunction "SO_17") (pintype "bidirectional"))
      (node (ref "IC8") (pin "2") (pinfunction "DO_(IO1)_2") (pintype "bidirectional"))
      (node (ref "J2") (pin "7") (pinfunction "DAT0_7") (pintype "bidirectional"))
      (node (ref "SPI1_MISO") (pin "TP") (pinfunction "TP_TP") (pintype "input"))
    )
    (net (code "102") (name "PA20_S2_MISO") (class "Default")
      (node (ref "IC1") (pin "29") (pinfunction "PA20_29") (pintype "bidirectional"))
      (node (ref "IC7") (pin "8") (pinfunction "SPI_MISO_8") (pintype "output"))
      (node (ref "SPI2_MISO") (pin "TP") (pinfunction "TP_TP") (pintype "input"))
    )
    (net (code "103") (name "PA21_C0_INT") (class "Default")
      (node (ref "IC1") (pin "30") (pinfunction "PA21_30") (pintype "bidirectional"))
      (node (ref "IC10") (pin "13") (pinfunction "~{INT}_13") (pintype "bidirectional"))
      (node (ref "R28") (pin "1") (pinfunction "1_1") (pintype "bidirectional"))
    )
    (net (code "104") (name "PA22_S2_MOSI") (class "Default")
      (node (ref "IC1") (pin "31") (pinfunction "PA22_31") (pintype "bidirectional"))
      (node (ref "IC7") (pin "9") (pinfunction "SPI_MOSI_9") (pintype "input"))
      (node (ref "SPI2_MOSI") (pin "TP") (pinfunction "TP_TP") (pintype "input"))
    )
    (net (code "105") (name "PA23_S2_SCK") (class "Default")
      (node (ref "IC1") (pin "32") (pinfunction "PA23_32") (pintype "bidirectional"))
      (node (ref "IC7") (pin "7") (pinfunction "SPI_CLK_7") (pintype "input"))
      (node (ref "SPI2_SCK") (pin "TP") (pinfunction "TP_TP") (pintype "input"))
    )
    (net (code "106") (name "PA24_USB_N") (class "Default")
      (node (ref "D12") (pin "3") (pinfunction "3_3") (pintype "passive"))
      (node (ref "IC1") (pin "33") (pinfunction "PA24_33") (pintype "bidirectional"))
      (node (ref "J5") (pin "2") (pinfunction "2_2") (pintype "passive"))
      (node (ref "USBN") (pin "TP") (pinfunction "TP_TP") (pintype "input"))
    )
    (net (code "107") (name "PA25_USB_P") (class "Default")
      (node (ref "D12") (pin "2") (pinfunction "2_2") (pintype "passive"))
      (node (ref "IC1") (pin "34") (pinfunction "PA25_34") (pintype "bidirectional"))
      (node (ref "J5") (pin "3") (pinfunction "3_3") (pintype "passive"))
      (node (ref "USBP") (pin "TP") (pinfunction "TP_TP") (pintype "input"))
    )
    (net (code "108") (name "PA27_GRST") (class "Default")
      (node (ref "IC1") (pin "39") (pinfunction "PA27_39") (pintype "bidirectional"))
      (node (ref "Q2") (pin "1") (pinfunction "1_1") (pintype "bidirectional"))
      (node (ref "R6") (pin "2") (pinfunction "2_2") (pintype "bidirectional"))
    )
    (net (code "109") (name "PA28_M_PWRON") (class "Default")
      (node (ref "IC1") (pin "41") (pinfunction "PA28_41") (pintype "bidirectional"))
      (node (ref "Q4") (pin "2") (pinfunction "G1_2") (pintype "input"))
      (node (ref "R18") (pin "2") (pinfunction "2_2") (pintype "bidirectional"))
    )
    (net (code "110") (name "PA30_SWCLK") (class "Default")
      (node (ref "IC1") (pin "45") (pinfunction "PA30_45") (pintype "bidirectional"))
      (node (ref "J7") (pin "4") (pinfunction "4_4") (pintype "bidirectional"))
    )
    (net (code "111") (name "PA31_SWDIO") (class "Default")
      (node (ref "IC1") (pin "46") (pinfunction "PA31_46") (pintype "bidirectional"))
      (node (ref "J7") (pin "2") (pinfunction "2_2") (pintype "bidirectional"))
    )
    (net (code "112") (name "PB02_BT_SS") (class "Default")
      (node (ref "BT_SS") (pin "TP") (pinfunction "TP_TP") (pintype "input"))
      (node (ref "IC1") (pin "47") (pinfunction "PB02_47") (pintype "bidirectional"))
      (node (ref "IC7") (pin "10") (pinfunction "SPI_CS_10") (pintype "input"))
    )
    (net (code "113") (name "PB03_BT_IRQ") (class "Default")
      (node (ref "BT_IRQ") (pin "TP") (pinfunction "TP_TP") (pintype "input"))
      (node (ref "IC1") (pin "48") (pinfunction "PB03_48") (pintype "bidirectional"))
      (node (ref "IC7") (pin "4") (pinfunction "SPI_IRQ_4") (pintype "output"))
    )
    (net (code "114") (name "PB08_M_RST") (class "Default")
      (node (ref "IC1") (pin "7") (pinfunction "PB08_7") (pintype "bidirectional"))
      (node (ref "Q4") (pin "5") (pinfunction "G2_5") (pintype "input"))
      (node (ref "R19") (pin "2") (pinfunction "2_2") (pintype "bidirectional"))
    )
    (net (code "115") (name "PB09") (class "Default")
      (node (ref "IC1") (pin "8") (pinfunction "PB09_8") (pintype "bidirectional"))
      (node (ref "R41") (pin "2") (pinfunction "2_2") (pintype "bidirectional"))
    )
    (net (code "116") (name "PB10_SD_SS") (class "Default")
      (node (ref "IC1") (pin "19") (pinfunction "PB10_19") (pintype "bidirectional"))
      (node (ref "J2") (pin "2") (pinfunction "CD/DAT3_2") (pintype "bidirectional"))
      (node (ref "R23") (pin "1") (pinfunction "1_1") (pintype "bidirectional"))
      (node (ref "SD_SS") (pin "TP") (pinfunction "TP_TP") (pintype "input"))
    )
    (net (code "117") (name "PB11_FL_SS") (class "Default")
      (node (ref "FL_SS") (pin "TP") (pinfunction "TP_TP") (pintype "input"))
      (node (ref "IC1") (pin "20") (pinfunction "PB11_20") (pintype "bidirectional"))
      (node (ref "IC8") (pin "1") (pinfunction "~{CS}_1") (pintype "bidirectional"))
      (node (ref "R22") (pin "1") (pinfunction "1_1") (pintype "bidirectional"))
    )
    (net (code "118") (name "PB22_S5_TX") (class "Default")
      (node (ref "FB2") (pin "2") (pinfunction "2_2") (pintype "bidirectional"))
      (node (ref "GRX") (pin "TP") (pinfunction "TP_TP") (pintype "input"))
      (node (ref "IC1") (pin "37") (pinfunction "PB22_37") (pintype "bidirectional"))
    )
    (net (code "119") (name "PB23_S5_RX") (class "Default")
      (node (ref "FB3") (pin "2") (pinfunction "2_2") (pintype "bidirectional"))
      (node (ref "GTX") (pin "TP") (pinfunction "TP_TP") (pintype "input"))
      (node (ref "IC1") (pin "38") (pinfunction "PB23_38") (pintype "bidirectional"))
    )
    (net (code "120") (name "PWR_ON") (class "Default")
      (node (ref "IC2") (pin "15") (pinfunction "PWR_ON_15") (pintype "bidirectional"))
      (node (ref "MPWR_ON") (pin "TP") (pinfunction "TP_TP") (pintype "input"))
      (node (ref "Q4") (pin "6") (pinfunction "D1_6") (pintype "bidirectional"))
    )
    (net (code "121") (name "RESETN") (class "Default")
      (node (ref "C51") (pin "1") (pinfunction "1_1") (pintype "bidirectional"))
      (node (ref "IC1") (pin "40") (pinfunction "~{RESET}_40") (pintype "bidirectional"))
      (node (ref "R39") (pin "2") (pinfunction "2_2") (pintype "bidirectional"))
      (node (ref "R40") (pin "1") (pinfunction "1_1") (pintype "bidirectional"))
      (node (ref "S1") (pin "2") (pinfunction "2_2") (pintype "bidirectional"))
    )
    (net (code "122") (name "RXCAN0") (class "Default")
      (node (ref "C0_RX") (pin "TP") (pinfunction "TP_TP") (pintype "input"))
      (node (ref "IC10") (pin "2") (pinfunction "RXCAN_2") (pintype "bidirectional"))
      (node (ref "IC9") (pin "4") (pinfunction "RXD1_4") (pintype "bidirectional"))
    )
    (net (code "123") (name "RXCAN1") (class "Default")
      (node (ref "C1_RX") (pin "TP") (pinfunction "TP_TP") (pintype "input"))
      (node (ref "IC11") (pin "2") (pinfunction "RXCAN_2") (pintype "bidirectional"))
      (node (ref "IC9") (pin "7") (pinfunction "RXD2_7") (pintype "bidirectional"))
    )
    (net (code "124") (name "SCLK") (class "Default")
      (node (ref "C48") (pin "2") (pinfunction "2_2") (pintype "bidirectional"))
      (node (ref "D2") (pin "2") (pinfunction "A_2") (pintype "bidirectional"))
      (node (ref "IC2") (pin "38") (pinfunction "SIM_CLK_38") (pintype "bidirectional"))
      (node (ref "J1") (pin "3") (pinfunction "C3_3") (pintype "bidirectional"))
      (node (ref "TP_SCLK") (pin "TP") (pinfunction "TP_TP") (pintype "input"))
    )
    (net (code "125") (name "SIM_DET") (class "Default")
      (node (ref "IC2") (pin "42") (pinfunction "GPIO5_42") (pintype "bidirectional"))
      (node (ref "Q3") (pin "3") (pinfunction "3_3") (pintype "bidirectional"))
      (node (ref "R17") (pin "1") (pinfunction "1_1") (pintype "bidirectional"))
    )
    (net (code "126") (name "SIO") (class "Default")
      (node (ref "C47") (pin "2") (pinfunction "2_2") (pintype "bidirectional"))
      (node (ref "D3") (pin "2") (pinfunction "A_2") (pintype "bidirectional"))
      (node (ref "IC2") (pin "39") (pinfunction "SIM_IO_39") (pintype "bidirectional"))
      (node (ref "J1") (pin "6") (pinfunction "C7_6") (pintype "bidirectional"))
      (node (ref "TP_SIO") (pin "TP") (pinfunction "TP_TP") (pintype "input"))
    )
    (net (code "127") (name "SRST") (class "Default")
      (node (ref "C46") (pin "2") (pinfunction "2_2") (pintype "bidirectional"))
      (node (ref "D4") (pin "2") (pinfunction "A_2") (pintype "bidirectional"))
      (node (ref "IC2") (pin "40") (pinfunction "SIM_RST_40") (pintype "bidirectional"))
      (node (ref "J1") (pin "2") (pinfunction "C2_2") (pintype "bidirectional"))
      (node (ref "TP_SRST") (pin "TP") (pinfunction "TP_TP") (pintype "input"))
    )
    (net (code "128") (name "SSW") (class "Default")
      (node (ref "D14") (pin "2") (pinfunction "A_2") (pintype "bidirectional"))
      (node (ref "J1") (pin "8") (pinfunction "DSW2_8") (pintype "bidirectional"))
      (node (ref "Q3") (pin "1") (pinfunction "1_1") (pintype "bidirectional"))
      (node (ref "R16") (pin "1") (pinfunction "1_1") (pintype "bidirectional"))
    )
    (net (code "129") (name "SVCC") (class "Default")
      (node (ref "C27") (pin "2") (pinfunction "2_2") (pintype "bidirectional"))
      (node (ref "C49") (pin "2") (pinfunction "2_2") (pintype "bidirectional"))
      (node (ref "D13") (pin "2") (pinfunction "A_2") (pintype "bidirectional"))
      (node (ref "IC2") (pin "41") (pinfunction "VSIM_41") (pintype "bidirectional"))
      (node (ref "J1") (pin "1") (pinfunction "C1_1") (pintype "bidirectional"))
      (node (ref "TP_SVCC") (pin "TP") (pinfunction "TP_TP") (pintype "input"))
    )
    (net (code "130") (name "TXCAN0") (class "Default")
      (node (ref "C0_TX") (pin "TP") (pinfunction "TP_TP") (pintype "input"))
      (node (ref "IC10") (pin "1") (pinfunction "TXCAN_1") (pintype "bidirectional"))
      (node (ref "IC9") (pin "1") (pinfunction "TXD1_1") (pintype "bidirectional"))
    )
    (net (code "131") (name "TXCAN1") (class "Default")
      (node (ref "C1_TX") (pin "TP") (pinfunction "TP_TP") (pintype "input"))
      (node (ref "IC11") (pin "1") (pinfunction "TXCAN_1") (pintype "bidirectional"))
      (node (ref "IC9") (pin "6") (pinfunction "TXD2_6") (pintype "bidirectional"))
    )
    (net (code "132") (name "UB_GPS_RX") (class "Default")
      (node (ref "FB2") (pin "1") (pinfunction "1_1") (pintype "bidirectional"))
      (node (ref "U$1") (pin "3_RXD") (pinfunction "3_RXD_3_RXD") (pintype "bidirectional"))
    )
    (net (code "133") (name "UB_GPS_TX") (class "Default")
      (node (ref "FB3") (pin "1") (pinfunction "1_1") (pintype "bidirectional"))
      (node (ref "U$1") (pin "2_TXD") (pinfunction "2_TXD_2_TXD") (pintype "bidirectional"))
    )
    (net (code "134") (name "UNLOCK_OUT") (class "Default")
      (node (ref "J4") (pin "7") (pinfunction "7_7") (pintype "bidirectional"))
      (node (ref "R21") (pin "2") (pinfunction "2_2") (pintype "bidirectional"))
    )
    (net (code "135") (name "VIN") (class "Default")
      (node (ref "C11") (pin "2") (pinfunction "2_2") (pintype "bidirectional"))
      (node (ref "C35") (pin "1") (pinfunction "1_1") (pintype "bidirectional"))
      (node (ref "C6") (pin "2") (pinfunction "2_2") (pintype "bidirectional"))
      (node (ref "IC9") (pin "3") (pinfunction "VCC_3") (pintype "bidirectional"))
      (node (ref "L1") (pin "2") (pinfunction "2_2") (pintype "bidirectional"))
      (node (ref "R1") (pin "2") (pinfunction "2_2") (pintype "bidirectional"))
      (node (ref "TP5V") (pin "TP") (pinfunction "TP_TP") (pintype "input"))
    )
    (net (code "136") (name "V_USB") (class "Default")
      (node (ref "D12") (pin "4") (pinfunction "4_4") (pintype "passive"))
      (node (ref "J5") (pin "1") (pinfunction "1_1") (pintype "passive"))
      (node (ref "VUSB") (pin "TP") (pinfunction "TP_TP") (pintype "input"))
    )
    (net (code "137") (name "unconnected-(IC2-ANT_DET-Pad62)") (class "Default")
      (node (ref "IC2") (pin "62") (pinfunction "ANT_DET_62") (pintype "bidirectional"))
    )
    (net (code "138") (name "unconnected-(IC2-GPIO2-Pad23)") (class "Default")
      (node (ref "IC2") (pin "23") (pinfunction "GPIO2_23") (pintype "bidirectional"))
    )
    (net (code "139") (name "unconnected-(IC2-GPIO3-Pad24)") (class "Default")
      (node (ref "IC2") (pin "24") (pinfunction "GPIO3_24") (pintype "bidirectional"))
    )
    (net (code "140") (name "unconnected-(IC2-GPIO4-Pad25)") (class "Default")
      (node (ref "IC2") (pin "25") (pinfunction "GPIO4_25") (pintype "bidirectional"))
    )
    (net (code "141") (name "unconnected-(IC2-GPIO6-Pad19)") (class "Default")
      (node (ref "IC2") (pin "19") (pinfunction "GPIO6_19") (pintype "bidirectional"))
    )
    (net (code "142") (name "unconnected-(IC2-I2S_CLK_{slash}_SPI_CLK-Pad36)") (class "Default")
      (node (ref "IC2") (pin "36") (pinfunction "I2S_CLK_/_SPI_CLK_36") (pintype "bidirectional"))
    )
    (net (code "143") (name "unconnected-(IC2-I2S_RXD_{slash}_SPI_MISO-Pad37)") (class "Default")
      (node (ref "IC2") (pin "37") (pinfunction "I2S_RXD_/_SPI_MISO_37") (pintype "bidirectional"))
    )
    (net (code "144") (name "unconnected-(IC2-I2S_TXD_{slash}_SPI_CS-Pad35)") (class "Default")
      (node (ref "IC2") (pin "35") (pinfunction "I2S_TXD_/_SPI_CS_35") (pintype "bidirectional"))
    )
    (net (code "145") (name "unconnected-(IC2-I2S_WA_{slash}_SPI_MOSI-Pad34)") (class "Default")
      (node (ref "IC2") (pin "34") (pinfunction "I2S_WA_/_SPI_MOSI_34") (pintype "bidirectional"))
    )
    (net (code "146") (name "unconnected-(IC2-RSR-Pad6)") (class "Default")
      (node (ref "IC2") (pin "6") (pinfunction "RSR_6") (pintype "bidirectional"))
    )
    (net (code "147") (name "unconnected-(IC2-RSVD_1-Pad2)") (class "Default")
      (node (ref "IC2") (pin "2") (pinfunction "RSVD_1_2") (pintype "bidirectional"))
    )
    (net (code "148") (name "unconnected-(IC2-RSVD_2-Pad31)") (class "Default")
      (node (ref "IC2") (pin "31") (pinfunction "RSVD_2_31") (pintype "bidirectional"))
    )
    (net (code "149") (name "unconnected-(IC2-SDIO_CLK-Pad45)") (class "Default")
      (node (ref "IC2") (pin "45") (pinfunction "SDIO_CLK_45") (pintype "bidirectional"))
    )
    (net (code "150") (name "unconnected-(IC2-SDIO_CMD-Pad46)") (class "Default")
      (node (ref "IC2") (pin "46") (pinfunction "SDIO_CMD_46") (pintype "bidirectional"))
    )
    (net (code "151") (name "unconnected-(IC2-SDIO_D0-Pad47)") (class "Default")
      (node (ref "IC2") (pin "47") (pinfunction "SDIO_D0_47") (pintype "bidirectional"))
    )
    (net (code "152") (name "unconnected-(IC2-SDIO_D1-Pad49)") (class "Default")
      (node (ref "IC2") (pin "49") (pinfunction "SDIO_D1_49") (pintype "bidirectional"))
    )
    (net (code "153") (name "unconnected-(IC2-SDIO_D2-Pad44)") (class "Default")
      (node (ref "IC2") (pin "44") (pinfunction "SDIO_D2_44") (pintype "bidirectional"))
    )
    (net (code "154") (name "unconnected-(IC2-SDIO_D3-Pad48)") (class "Default")
      (node (ref "IC2") (pin "48") (pinfunction "SDIO_D3_48") (pintype "bidirectional"))
    )
    (net (code "155") (name "unconnected-(IC3-ADJ{slash}NC-Pad4)") (class "Default")
      (node (ref "IC3") (pin "4") (pinfunction "ADJ/NC_4") (pintype "bidirectional"))
    )
    (net (code "156") (name "unconnected-(IC6-EP-Pad9)") (class "Default")
      (node (ref "IC6") (pin "9") (pinfunction "EP_9") (pintype "bidirectional"))
    )
    (net (code "157") (name "unconnected-(IC6-NC_1-Pad1)") (class "Default")
      (node (ref "IC6") (pin "1") (pinfunction "NC_1_1") (pintype "bidirectional"))
    )
    (net (code "158") (name "unconnected-(IC6-NC_2-Pad2)") (class "Default")
      (node (ref "IC6") (pin "2") (pinfunction "NC_2_2") (pintype "bidirectional"))
    )
    (net (code "159") (name "unconnected-(IC6-NC_3-Pad3)") (class "Default")
      (node (ref "IC6") (pin "3") (pinfunction "NC_3_3") (pintype "bidirectional"))
    )
    (net (code "160") (name "unconnected-(IC6-NC_4-Pad7)") (class "Default")
      (node (ref "IC6") (pin "7") (pinfunction "NC_4_7") (pintype "bidirectional"))
    )
    (net (code "161") (name "unconnected-(IC7-ANATEST0-Pad3)") (class "Default")
      (node (ref "IC7") (pin "3") (pinfunction "ANATEST0_3") (pintype "input"))
    )
    (net (code "162") (name "unconnected-(IC7-EXT_LPCLK-Pad1)") (class "Default")
      (node (ref "IC7") (pin "1") (pinfunction "EXT_LPCLK_1") (pintype "input"))
    )
    (net (code "163") (name "unconnected-(IC7-GPIO2-Pad2)") (class "Default")
      (node (ref "IC7") (pin "2") (pinfunction "GPIO2_2") (pintype "bidirectional"))
    )
    (net (code "164") (name "unconnected-(IC9-EP-Pad15)") (class "Default")
      (node (ref "IC9") (pin "15") (pinfunction "EP_15") (pintype "bidirectional"))
    )
    (net (code "165") (name "unconnected-(IC10-CLKOUT{slash}SOF-Pad3)") (class "Default")
      (node (ref "IC10") (pin "3") (pinfunction "CLKOUT/SOF_3") (pintype "bidirectional"))
    )
    (net (code "166") (name "unconnected-(IC10-NC_1-Pad6)") (class "Default")
      (node (ref "IC10") (pin "6") (pinfunction "NC_1_6") (pintype "bidirectional"))
    )
    (net (code "167") (name "unconnected-(IC10-NC_2-Pad15)") (class "Default")
      (node (ref "IC10") (pin "15") (pinfunction "NC_2_15") (pintype "bidirectional"))
    )
    (net (code "168") (name "unconnected-(IC10-~{RX1BF}-Pad11)") (class "Default")
      (node (ref "IC10") (pin "11") (pinfunction "~{RX1BF}_11") (pintype "bidirectional"))
    )
    (net (code "169") (name "unconnected-(IC10-~{TX0RTS}-Pad4)") (class "Default")
      (node (ref "IC10") (pin "4") (pinfunction "~{TX0RTS}_4") (pintype "bidirectional"))
    )
    (net (code "170") (name "unconnected-(IC10-~{TX1RTS}-Pad5)") (class "Default")
      (node (ref "IC10") (pin "5") (pinfunction "~{TX1RTS}_5") (pintype "bidirectional"))
    )
    (net (code "171") (name "unconnected-(IC10-~{TX2RTS}-Pad7)") (class "Default")
      (node (ref "IC10") (pin "7") (pinfunction "~{TX2RTS}_7") (pintype "bidirectional"))
    )
    (net (code "172") (name "unconnected-(IC11-CLKOUT{slash}SOF-Pad3)") (class "Default")
      (node (ref "IC11") (pin "3") (pinfunction "CLKOUT/SOF_3") (pintype "bidirectional"))
    )
    (net (code "173") (name "unconnected-(IC11-NC_1-Pad6)") (class "Default")
      (node (ref "IC11") (pin "6") (pinfunction "NC_1_6") (pintype "bidirectional"))
    )
    (net (code "174") (name "unconnected-(IC11-NC_2-Pad15)") (class "Default")
      (node (ref "IC11") (pin "15") (pinfunction "NC_2_15") (pintype "bidirectional"))
    )
    (net (code "175") (name "unconnected-(IC11-~{RX1BF}-Pad11)") (class "Default")
      (node (ref "IC11") (pin "11") (pinfunction "~{RX1BF}_11") (pintype "bidirectional"))
    )
    (net (code "176") (name "unconnected-(IC11-~{TX0RTS}-Pad4)") (class "Default")
      (node (ref "IC11") (pin "4") (pinfunction "~{TX0RTS}_4") (pintype "bidirectional"))
    )
    (net (code "177") (name "unconnected-(IC11-~{TX1RTS}-Pad5)") (class "Default")
      (node (ref "IC11") (pin "5") (pinfunction "~{TX1RTS}_5") (pintype "bidirectional"))
    )
    (net (code "178") (name "unconnected-(IC11-~{TX2RTS}-Pad7)") (class "Default")
      (node (ref "IC11") (pin "7") (pinfunction "~{TX2RTS}_7") (pintype "bidirectional"))
    )
    (net (code "179") (name "unconnected-(IC14-AUX_CL-Pad7)") (class "Default")
      (node (ref "IC14") (pin "7") (pinfunction "AUX_CL_7") (pintype "bidirectional"))
    )
    (net (code "180") (name "unconnected-(IC14-AUX_DA-Pad6)") (class "Default")
      (node (ref "IC14") (pin "6") (pinfunction "AUX_DA_6") (pintype "bidirectional"))
    )
    (net (code "181") (name "unconnected-(IC14-INT-Pad12)") (class "Default")
      (node (ref "IC14") (pin "12") (pinfunction "INT_12") (pintype "bidirectional"))
    )
    (net (code "182") (name "unconnected-(IC14-NC_1-Pad2)") (class "Default")
      (node (ref "IC14") (pin "2") (pinfunction "NC_1_2") (pintype "bidirectional"))
    )
    (net (code "183") (name "unconnected-(IC14-NC_2-Pad3)") (class "Default")
      (node (ref "IC14") (pin "3") (pinfunction "NC_2_3") (pintype "bidirectional"))
    )
    (net (code "184") (name "unconnected-(IC14-NC_3-Pad4)") (class "Default")
      (node (ref "IC14") (pin "4") (pinfunction "NC_3_4") (pintype "bidirectional"))
    )
    (net (code "185") (name "unconnected-(IC14-NC_4-Pad5)") (class "Default")
      (node (ref "IC14") (pin "5") (pinfunction "NC_4_5") (pintype "bidirectional"))
    )
    (net (code "186") (name "unconnected-(IC14-NC_5-Pad14)") (class "Default")
      (node (ref "IC14") (pin "14") (pinfunction "NC_5_14") (pintype "bidirectional"))
    )
    (net (code "187") (name "unconnected-(IC14-NC_6-Pad15)") (class "Default")
      (node (ref "IC14") (pin "15") (pinfunction "NC_6_15") (pintype "bidirectional"))
    )
    (net (code "188") (name "unconnected-(IC14-NC_7-Pad16)") (class "Default")
      (node (ref "IC14") (pin "16") (pinfunction "NC_7_16") (pintype "bidirectional"))
    )
    (net (code "189") (name "unconnected-(IC14-NC_8-Pad17)") (class "Default")
      (node (ref "IC14") (pin "17") (pinfunction "NC_8_17") (pintype "bidirectional"))
    )
    (net (code "190") (name "unconnected-(IC14-RESV_1-Pad19)") (class "Default")
      (node (ref "IC14") (pin "19") (pinfunction "RESV_1_19") (pintype "bidirectional"))
    )
    (net (code "191") (name "unconnected-(IC14-RESV_2-Pad21)") (class "Default")
      (node (ref "IC14") (pin "21") (pinfunction "RESV_2_21") (pintype "bidirectional"))
    )
    (net (code "192") (name "unconnected-(IC14-RESV_3-Pad22)") (class "Default")
      (node (ref "IC14") (pin "22") (pinfunction "RESV_3_22") (pintype "bidirectional"))
    )
    (net (code "193") (name "unconnected-(IC14-THERMAL_PAD-Pad25)") (class "Default")
      (node (ref "IC14") (pin "25") (pinfunction "THERMAL_PAD_25") (pintype "bidirectional"))
    )
    (net (code "194") (name "unconnected-(J1-C6-Pad5)") (class "Default")
      (node (ref "J1") (pin "5") (pinfunction "C6_5") (pintype "bidirectional"))
    )
    (net (code "195") (name "unconnected-(J2-DAT1-Pad8)") (class "Default")
      (node (ref "J2") (pin "8") (pinfunction "DAT1_8") (pintype "bidirectional"))
    )
    (net (code "196") (name "unconnected-(J2-DAT2-Pad1)") (class "Default")
      (node (ref "J2") (pin "1") (pinfunction "DAT2_1") (pintype "bidirectional"))
    )
    (net (code "197") (name "unconnected-(J7-Pad6)") (class "Default")
      (node (ref "J7") (pin "6") (pinfunction "6_6") (pintype "bidirectional"))
    )
    (net (code "198") (name "unconnected-(J7-Pad7)") (class "Default")
      (node (ref "J7") (pin "7") (pinfunction "7_7") (pintype "bidirectional"))
    )
    (net (code "199") (name "unconnected-(J7-Pad8)") (class "Default")
      (node (ref "J7") (pin "8") (pinfunction "8_8") (pintype "bidirectional"))
    )
    (net (code "200") (name "unconnected-(K1-NC_1-Pad3)") (class "Default")
      (node (ref "K1") (pin "3") (pinfunction "NC_1_3") (pintype "bidirectional"))
    )
    (net (code "201") (name "unconnected-(K1-NO_2-Pad8)") (class "Default")
      (node (ref "K1") (pin "8") (pinfunction "NO_2_8") (pintype "bidirectional"))
    )
    (net (code "202") (name "unconnected-(U$1-13_LNA_EN{slash}RES-Pad13_LNA_EN)") (class "Default")
      (node (ref "U$1") (pin "13_LNA_EN") (pinfunction "13_LNA_EN/RES_13_LNA_EN") (pintype "bidirectional"))
    )
    (net (code "203") (name "unconnected-(U$1-15_RES{slash}V_ANT-Pad15_V_ANT{slash}RESERVED)") (class "Default")
      (node (ref "U$1") (pin "15_V_ANT/RESERVED") (pinfunction "15_RES/V_ANT_15_V_ANT/RESERVED") (pintype "bidirectional"))
    )
    (net (code "204") (name "unconnected-(U$1-Pad5_EXTINT)") (class "Default")
      (node (ref "U$1") (pin "5_EXTINT") (pinfunction "5_EXTINT_5_EXTINT") (pintype "bidirectional"))
    )
    (net (code "205") (name "unconnected-(U$1-Pad18_SAFEBOOT_N)") (class "Default")
      (node (ref "U$1") (pin "18_SAFEBOOT_N") (pinfunction "18_SAFEBOOT_N_18_SAFEBOOT_N") (pintype "bidirectional"))
    )
    (net (code "206") (name "unconnected-(Z1-NC-Pad2)") (class "Default")
      (node (ref "Z1") (pin "2") (pinfunction "NC_2") (pintype "no_connect"))
    )
  )
)
